# mainboard_split_IO_FPGA_8x2-1a.net
KiCad netlist of a schematic drawn in EAGLE
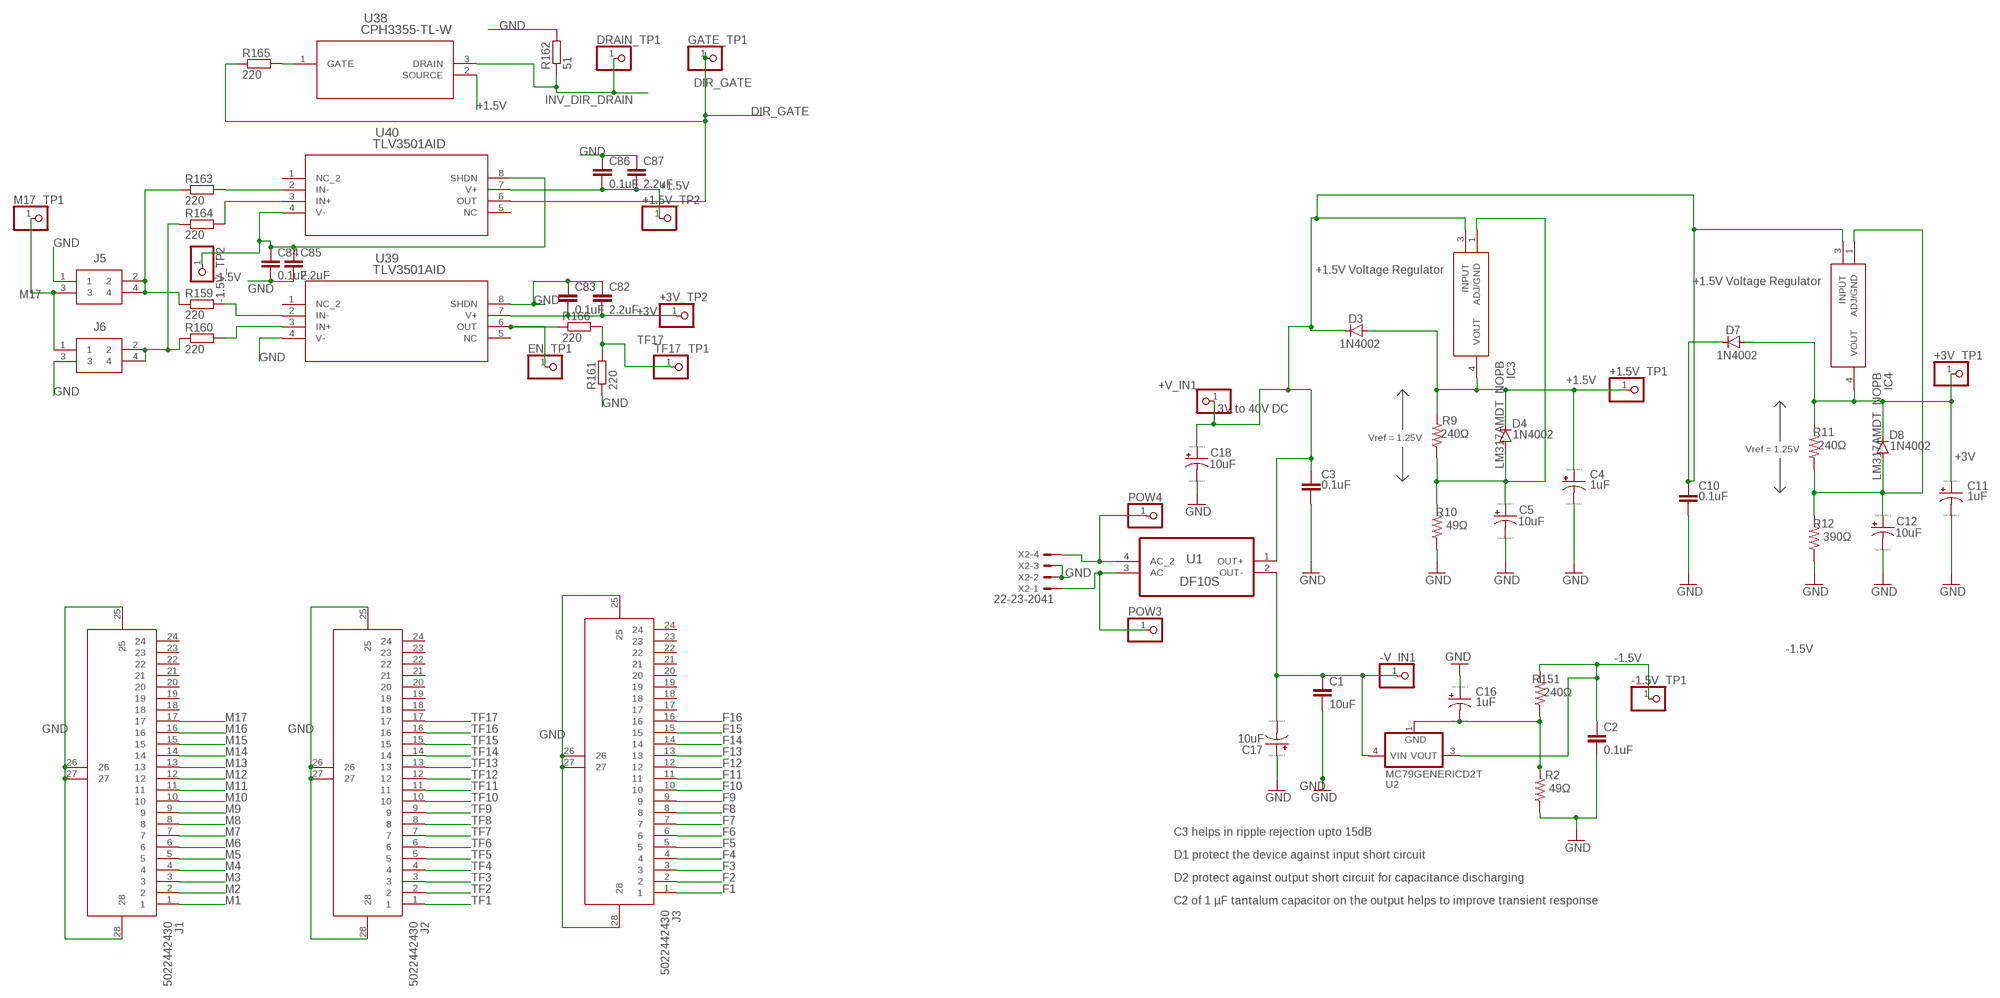
[diagram p0: schematic, sheet 1]
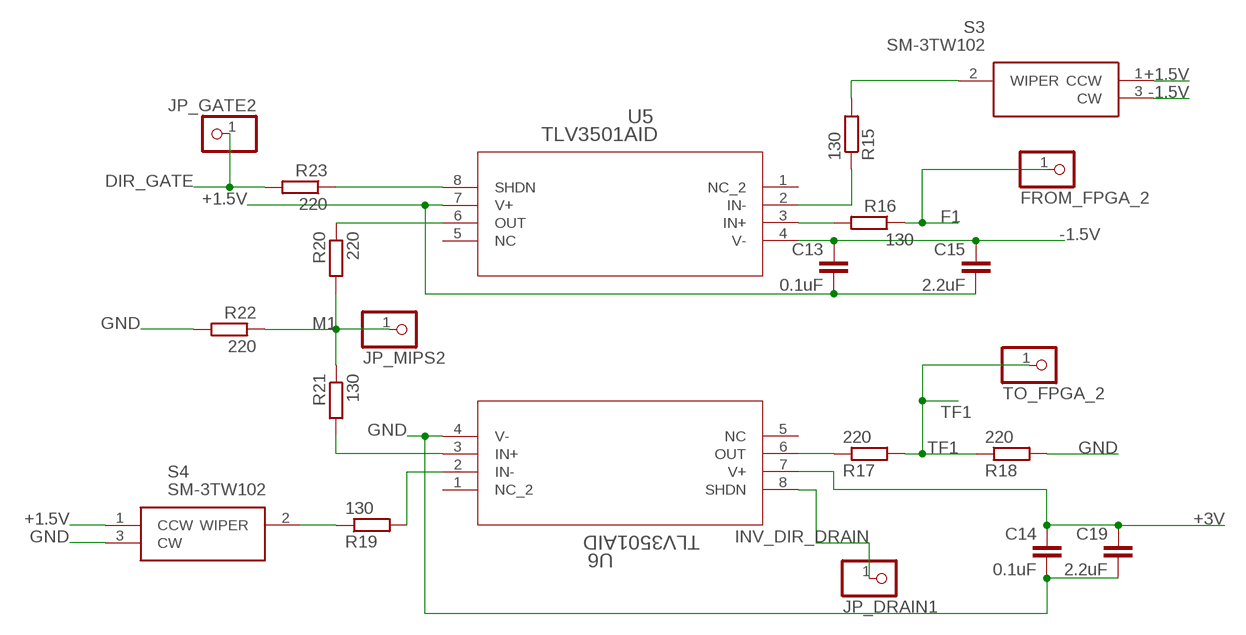
[diagram p1: schematic, sheet 2]
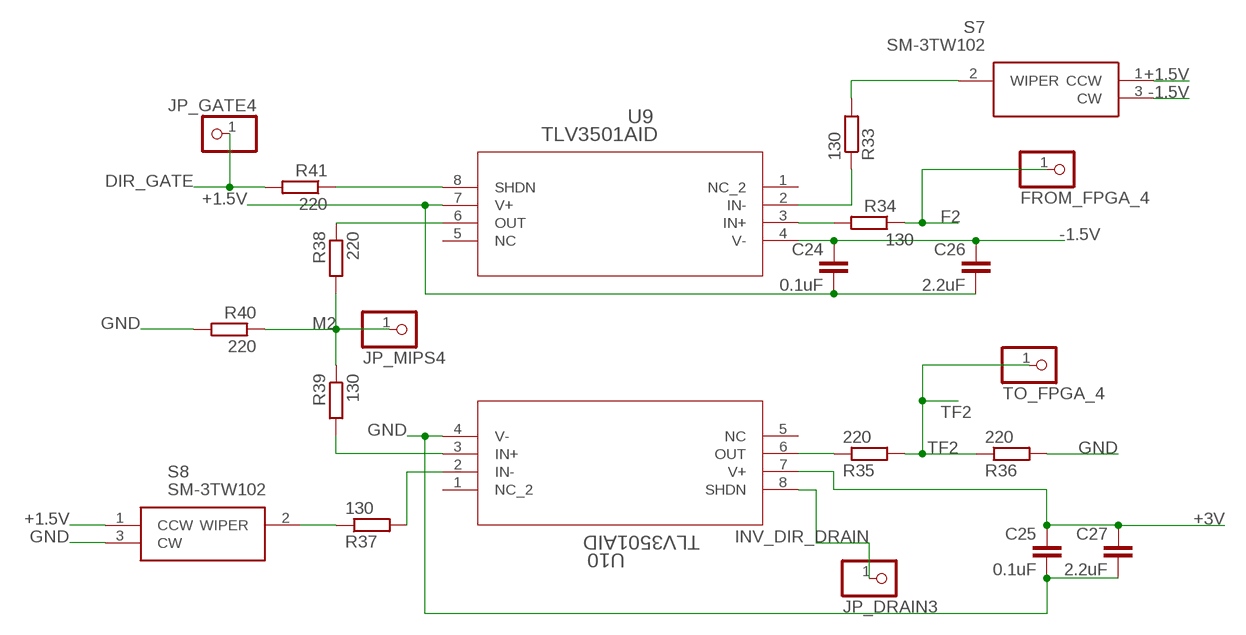
[diagram p2: schematic, sheet 3]
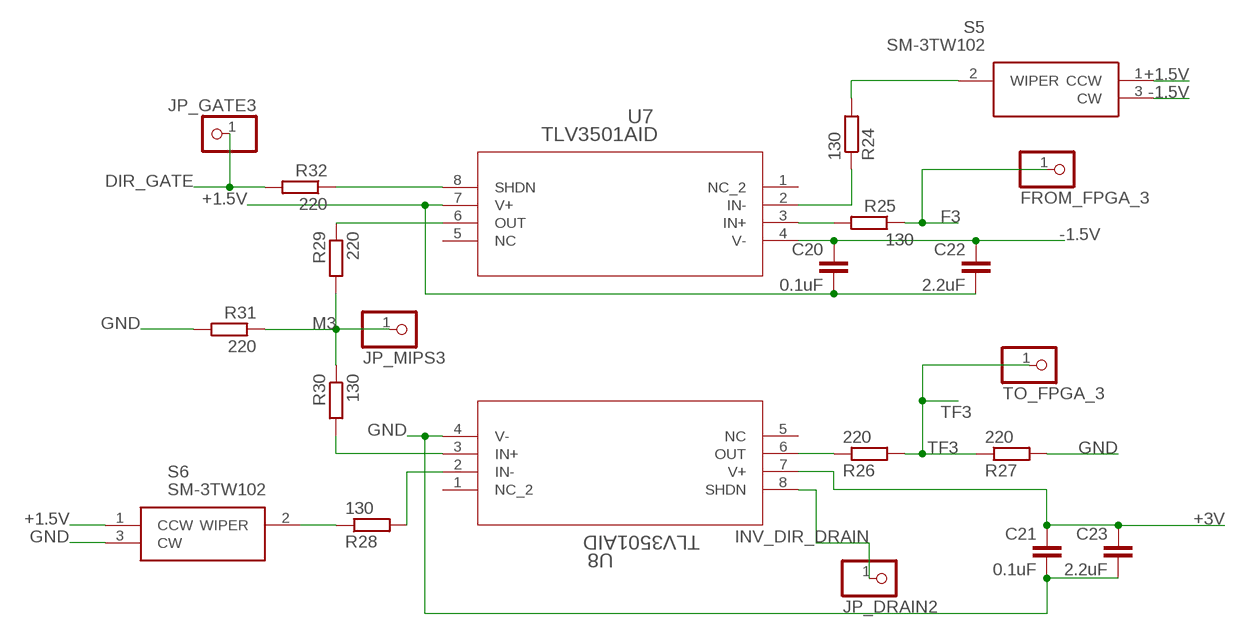
[diagram p3: schematic, sheet 4]
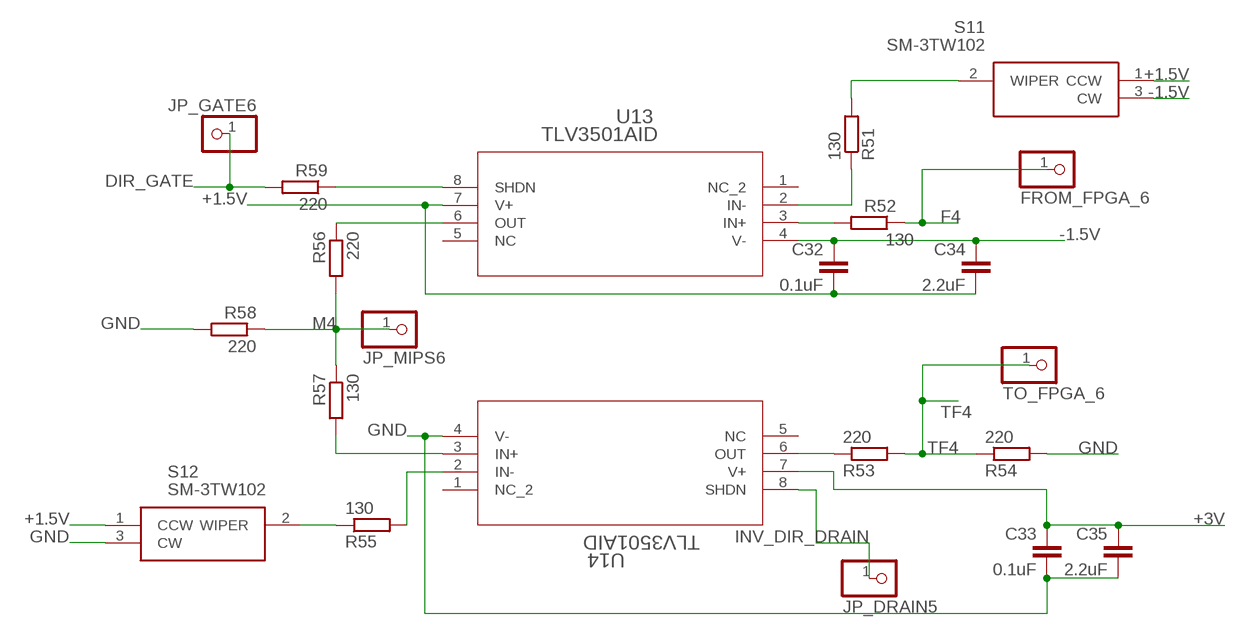
[diagram p4: schematic, sheet 5]
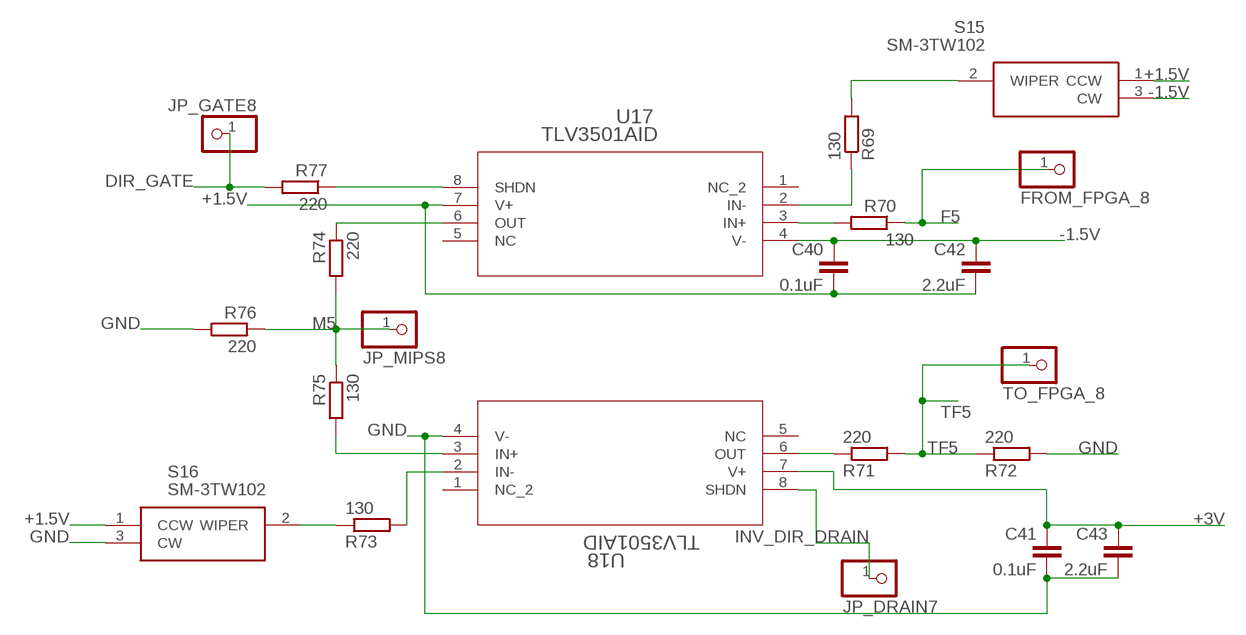
[diagram p5: schematic, sheet 6]
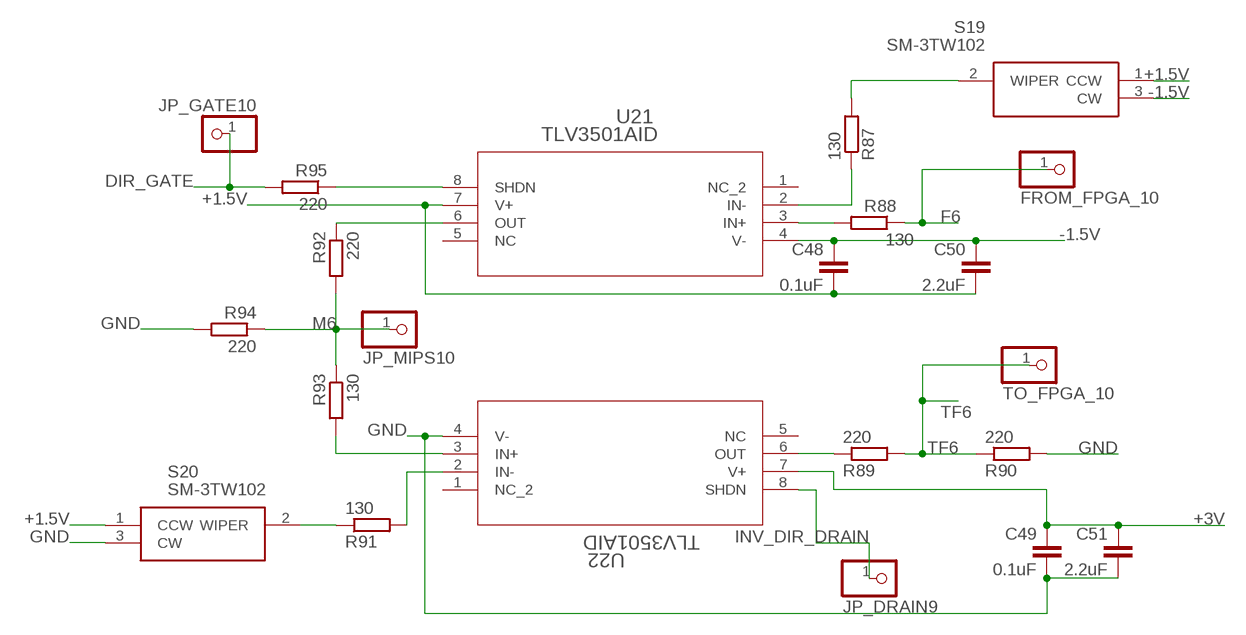
[diagram p6: schematic, sheet 7]
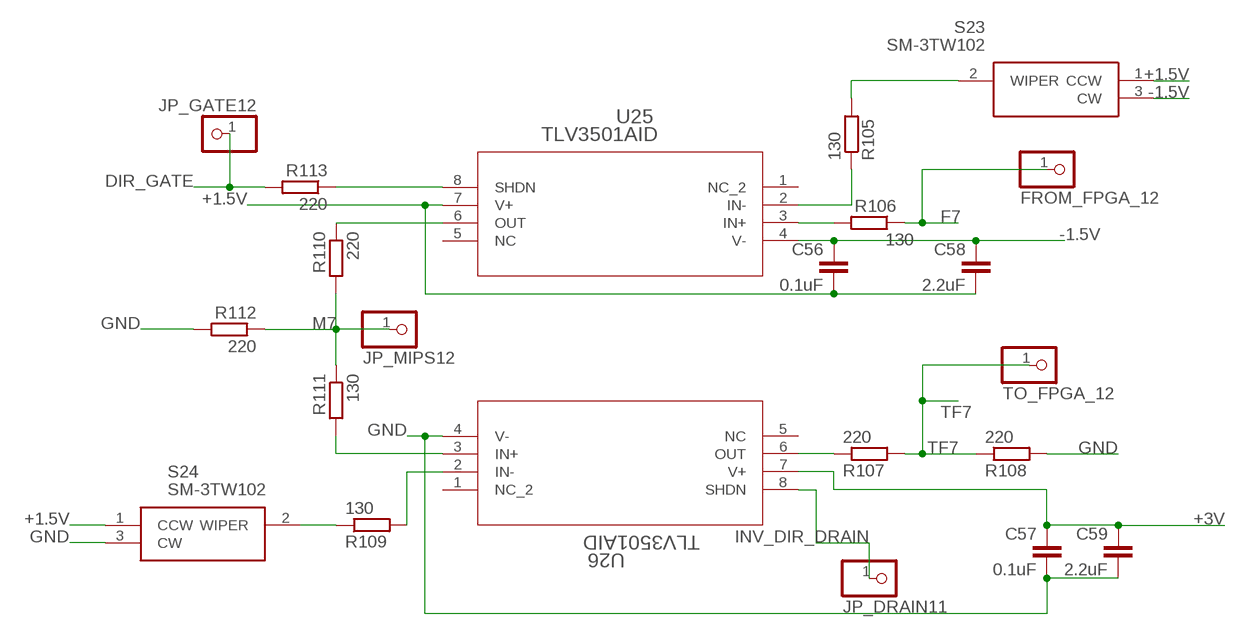
[diagram p7: schematic, sheet 8]
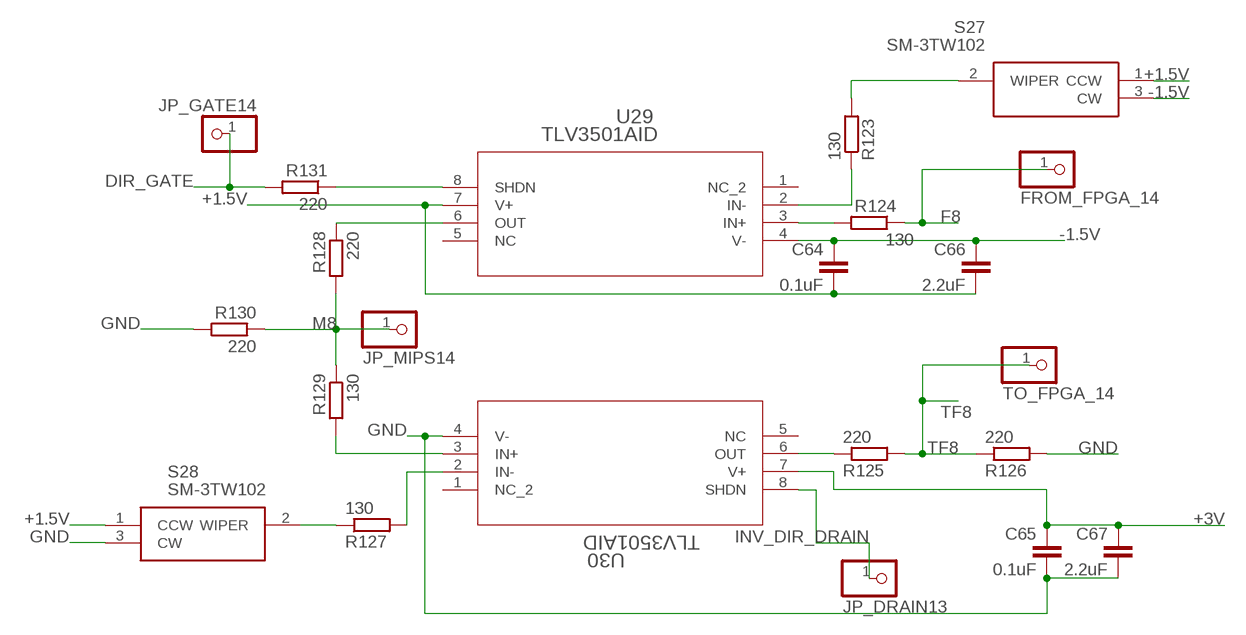
[diagram p8: schematic, sheet 9]
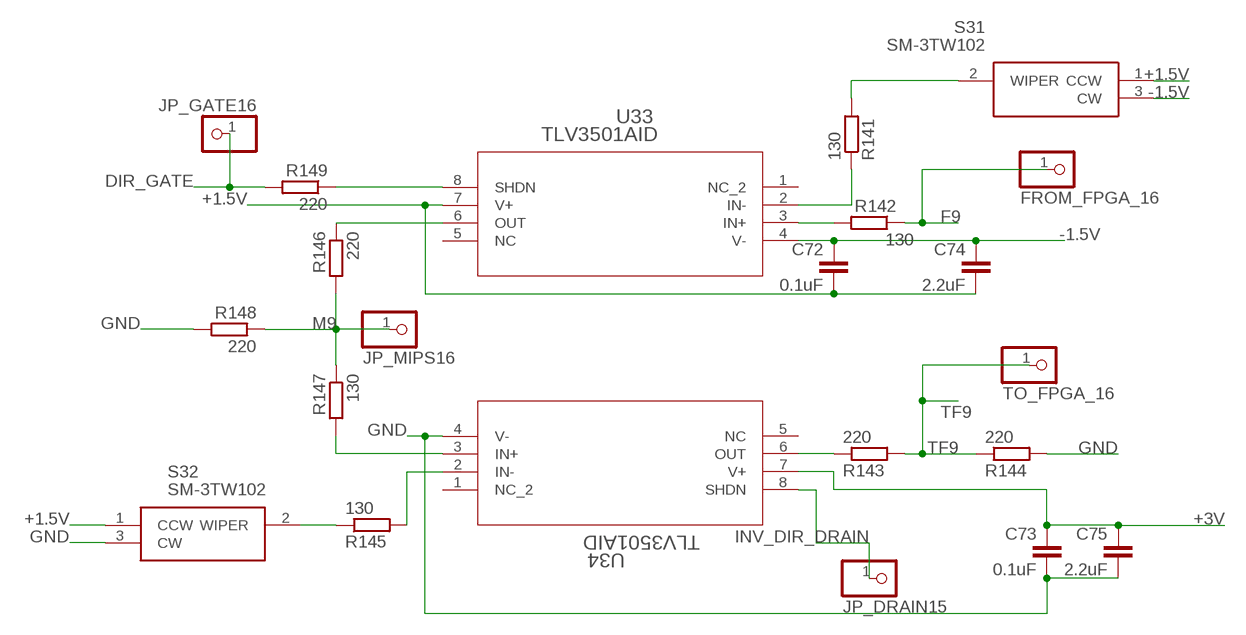
[diagram p9: schematic, sheet 10]
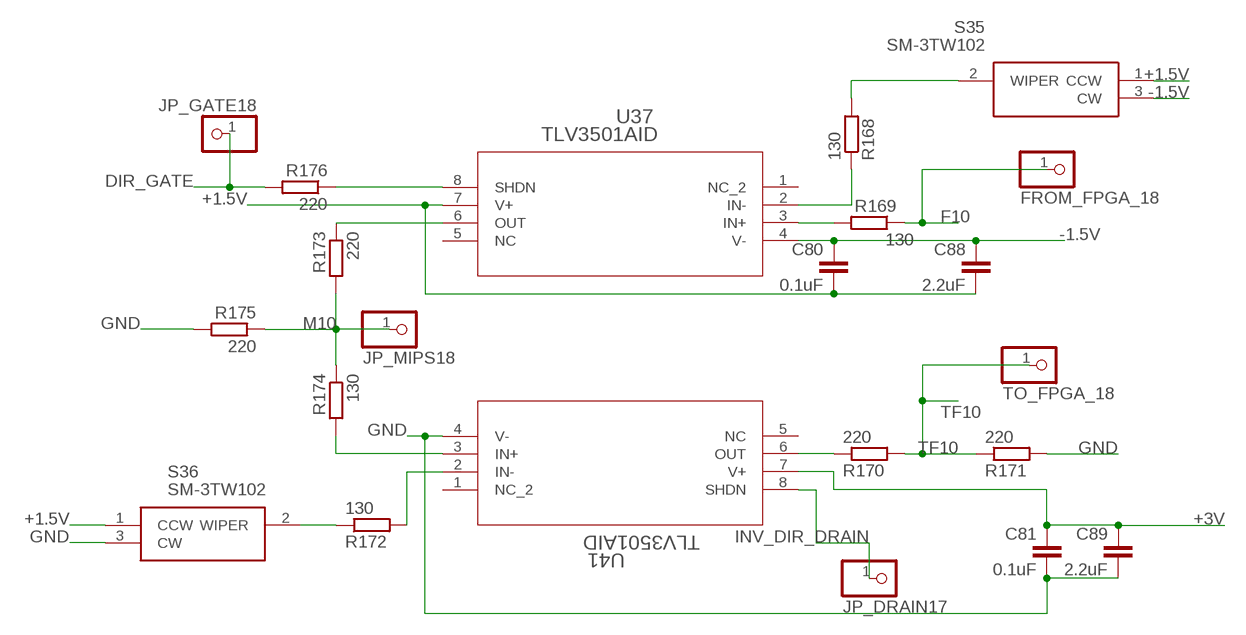
[diagram p10: schematic, sheet 11]
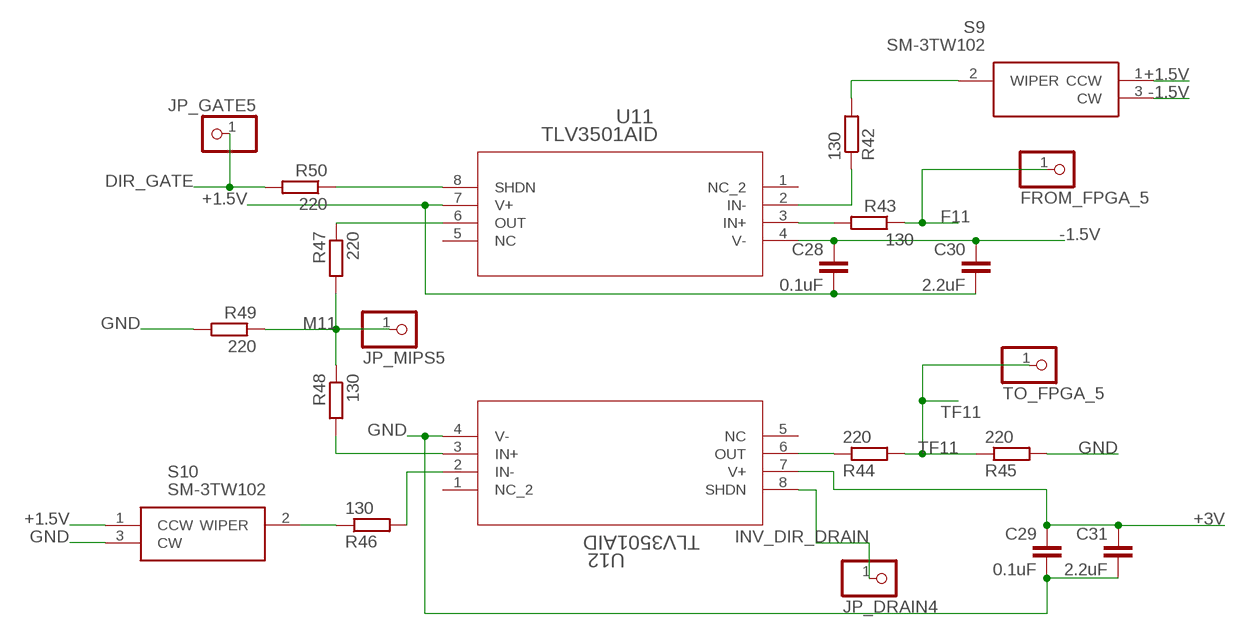
[diagram p11: schematic, sheet 12]
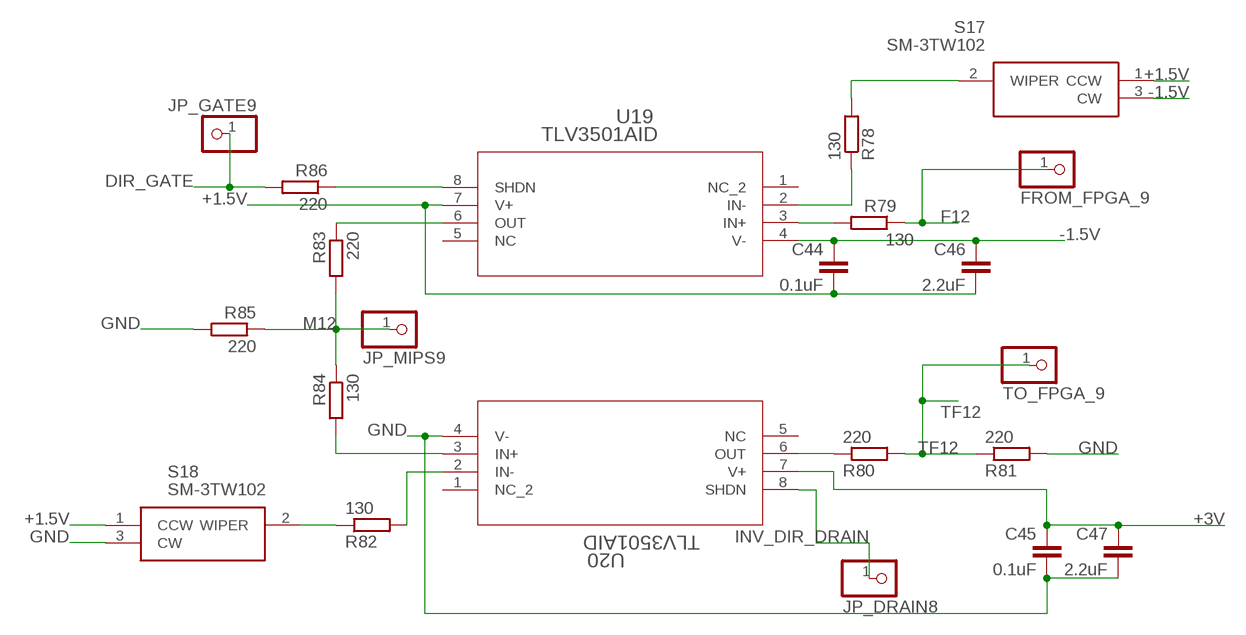
[diagram p12: schematic, sheet 13]
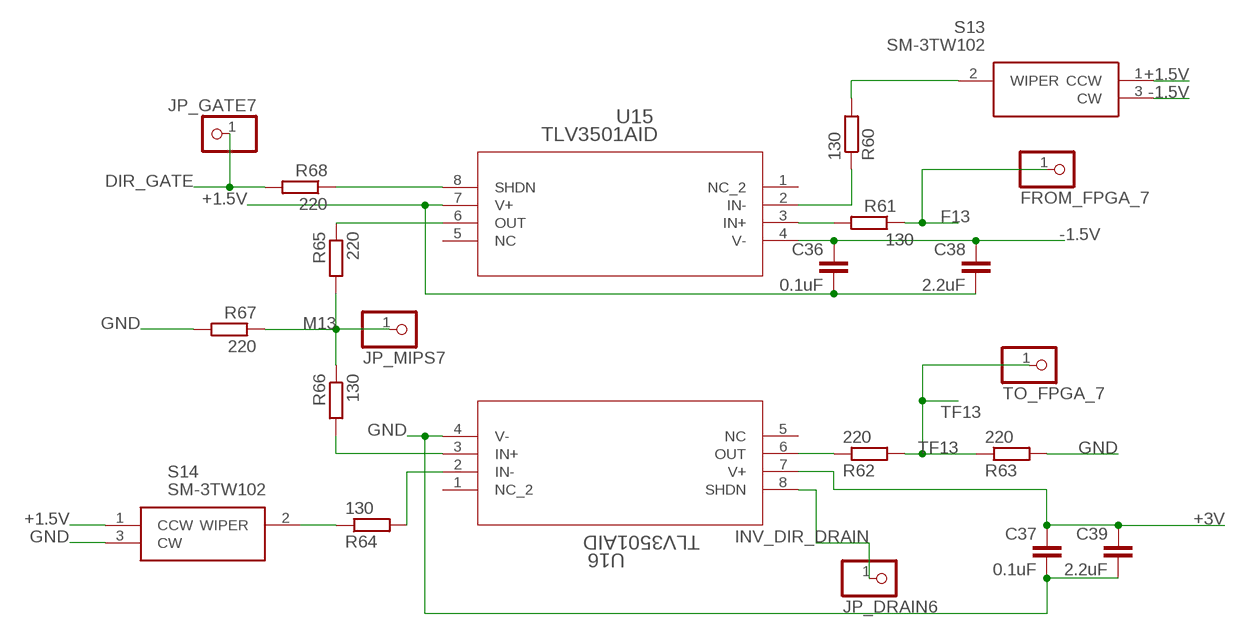
[diagram p13: schematic, sheet 14]
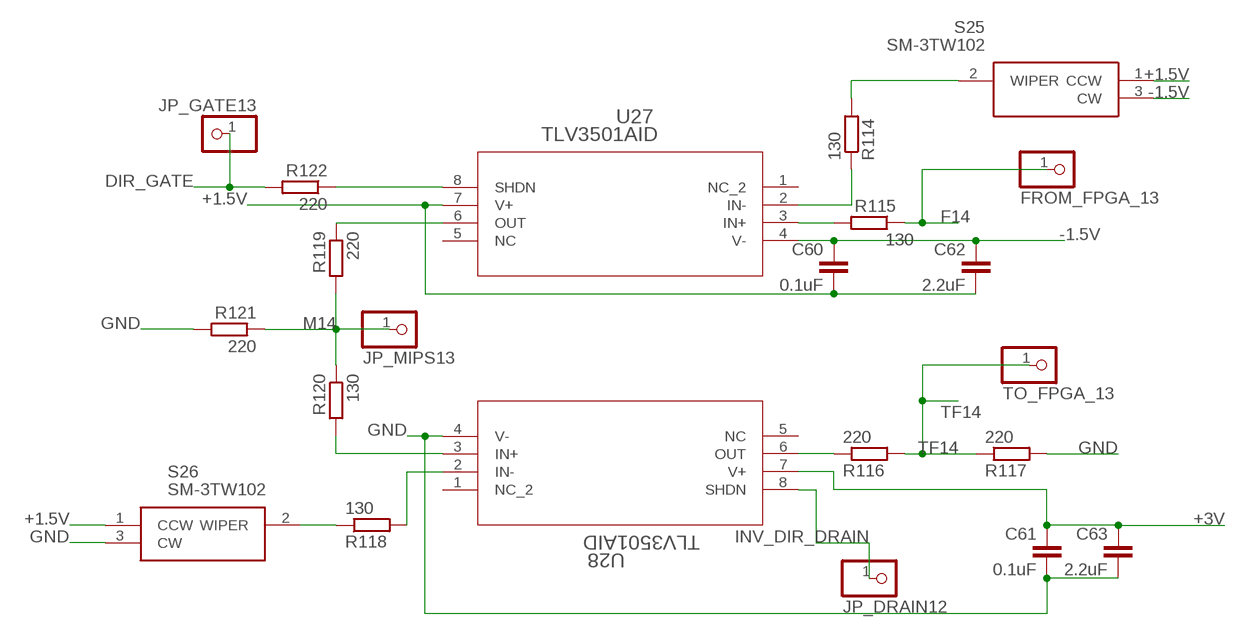
[diagram p14: schematic, sheet 15]
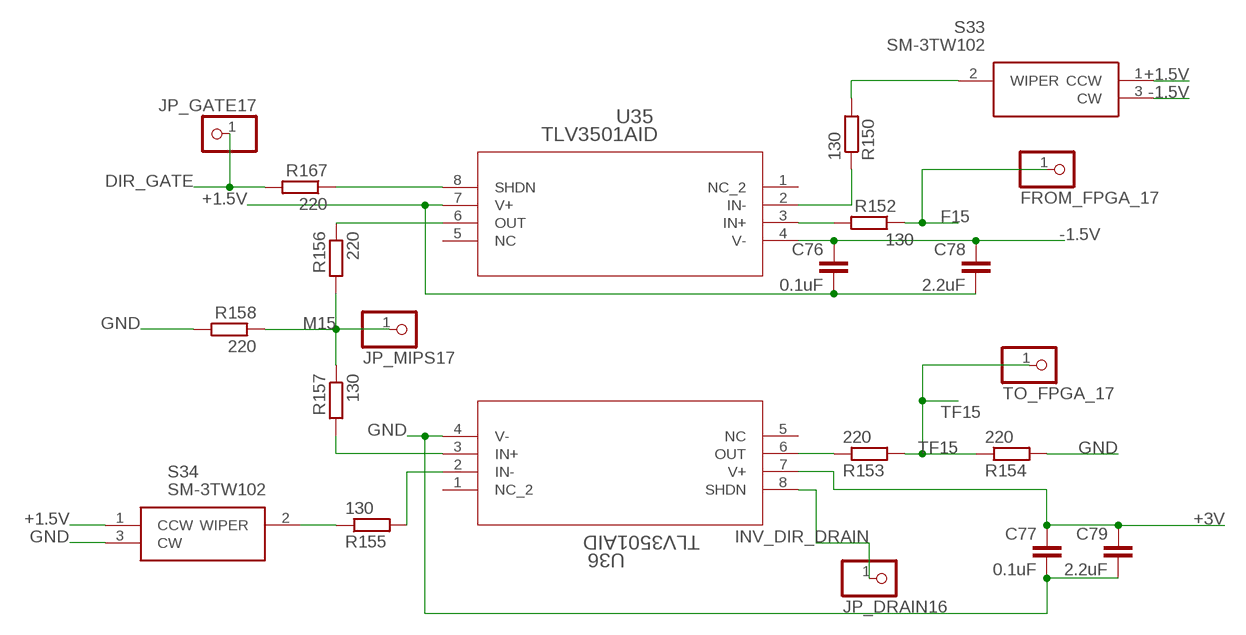
[diagram p15: schematic, sheet 16]
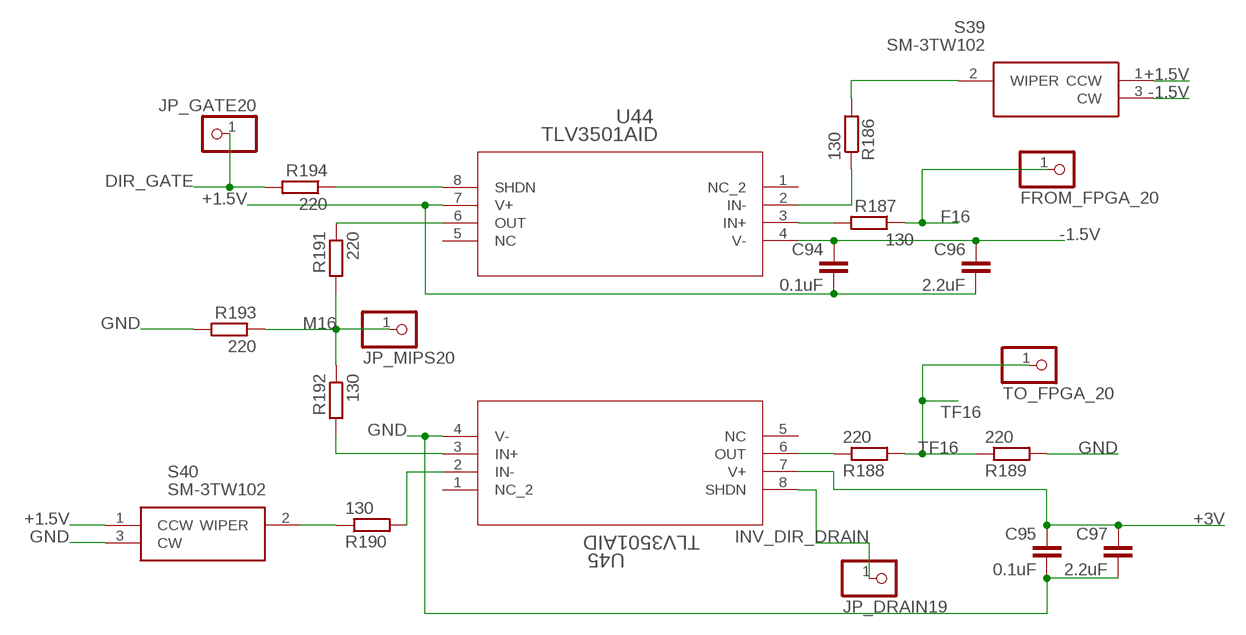
[diagram p16: schematic, sheet 17]

(export (version "E")
  (design (tool "Eeschema 10.0.6"))
  (components
    (comp (ref "C13")
      (value "0.1uF")
      (footprint "eagle-import:C0805")
      (libsource (lib "eagle-import") (part "C-EUC0805"))
    )
    (comp (ref "C14")
      (value "0.1uF")
      (footprint "eagle-import:C0805")
      (libsource (lib "eagle-import") (part "C-EUC0805"))
    )
    (comp (ref "C15")
      (value "2.2uF")
      (footprint "eagle-import:C0805")
      (libsource (lib "eagle-import") (part "C-EUC0805"))
    )
    (comp (ref "C19")
      (value "2.2uF")
      (footprint "eagle-import:C0805")
      (libsource (lib "eagle-import") (part "C-EUC0805"))
    )
    (comp (ref "FROM_FPGA_2")
      (value "PINHD-1X1")
      (footprint "eagle-import:1X01")
      (libsource (lib "eagle-import") (part "PINHD-1X1"))
    )
    (comp (ref "JP_DRAIN1")
      (value "PINHD-1X1")
      (footprint "eagle-import:1X01")
      (libsource (lib "eagle-import") (part "PINHD-1X1"))
    )
    (comp (ref "JP_GATE2")
      (value "PINHD-1X1")
      (footprint "eagle-import:1X01")
      (libsource (lib "eagle-import") (part "PINHD-1X1"))
    )
    (comp (ref "JP_MIPS2")
      (value "PINHD-1X1")
      (footprint "eagle-import:1X01")
      (libsource (lib "eagle-import") (part "PINHD-1X1"))
    )
    (comp (ref "R15")
      (value "130")
      (footprint "eagle-import:R0805")
      (libsource (lib "eagle-import") (part "R-EU_R0805"))
    )
    (comp (ref "R16")
      (value "130")
      (footprint "eagle-import:R0603")
      (libsource (lib "eagle-import") (part "R-EU_R0603"))
    )
    (comp (ref "R17")
      (value "220")
      (footprint "eagle-import:R0805")
      (libsource (lib "eagle-import") (part "R-EU_R0805"))
    )
    (comp (ref "R18")
      (value "220")
      (footprint "eagle-import:R0805")
      (libsource (lib "eagle-import") (part "R-EU_R0805"))
    )
    (comp (ref "R19")
      (value "130")
      (footprint "eagle-import:R0805")
      (libsource (lib "eagle-import") (part "R-EU_R0805"))
    )
    (comp (ref "R20")
      (value "220")
      (footprint "eagle-import:R0805")
      (libsource (lib "eagle-import") (part "R-EU_R0805"))
    )
    (comp (ref "R21")
      (value "130")
      (footprint "eagle-import:R0805")
      (libsource (lib "eagle-import") (part "R-EU_R0805"))
    )
    (comp (ref "R22")
      (value "220")
      (footprint "eagle-import:R0805")
      (libsource (lib "eagle-import") (part "R-EU_R0805"))
    )
    (comp (ref "R23")
      (value "220")
      (footprint "eagle-import:R0805")
      (libsource (lib "eagle-import") (part "R-EU_R0805"))
    )
    (comp (ref "S3")
      (value "SM-3TW102")
      (footprint "eagle-import:SM3TW102")
      (fields (field (name "MOUSER_PART_NUMBER") "229-SM-3TW102"))
      (libsource (lib "eagle-import") (part "SM-3TW102"))
    )
    (comp (ref "S4")
      (value "SM-3TW102")
      (footprint "eagle-import:SM3TW102")
      (fields (field (name "MOUSER_PART_NUMBER") "229-SM-3TW102"))
      (libsource (lib "eagle-import") (part "SM-3TW102"))
    )
    (comp (ref "TO_FPGA_2")
      (value "PINHD-1X1")
      (footprint "eagle-import:1X01")
      (libsource (lib "eagle-import") (part "PINHD-1X1"))
    )
    (comp (ref "U5")
      (value "TLV3501AID")
      (footprint "eagle-import:D8")
      (fields (field (name "COPYRIGHT") "Copyright (C) 2022 Ultra Librarian. All rights reserved."))
      (libsource (lib "eagle-import") (part "TLV3501AID"))
    )
    (comp (ref "U6")
      (value "TLV3501AID")
      (footprint "eagle-import:D8")
      (fields (field (name "COPYRIGHT") "Copyright (C) 2022 Ultra Librarian. All rights reserved."))
      (libsource (lib "eagle-import") (part "TLV3501AID"))
    )
    (comp (ref "C80")
      (value "0.1uF")
      (footprint "eagle-import:C0805")
      (libsource (lib "eagle-import") (part "C-EUC0805"))
    )
    (comp (ref "C81")
      (value "0.1uF")
      (footprint "eagle-import:C0805")
      (libsource (lib "eagle-import") (part "C-EUC0805"))
    )
    (comp (ref "C88")
      (value "2.2uF")
      (footprint "eagle-import:C0805")
      (libsource (lib "eagle-import") (part "C-EUC0805"))
    )
    (comp (ref "C89")
      (value "2.2uF")
      (footprint "eagle-import:C0805")
      (libsource (lib "eagle-import") (part "C-EUC0805"))
    )
    (comp (ref "FROM_FPGA_18")
      (value "PINHD-1X1")
      (footprint "eagle-import:1X01")
      (libsource (lib "eagle-import") (part "PINHD-1X1"))
    )
    (comp (ref "JP_DRAIN17")
      (value "PINHD-1X1")
      (footprint "eagle-import:1X01")
      (libsource (lib "eagle-import") (part "PINHD-1X1"))
    )
    (comp (ref "JP_GATE18")
      (value "PINHD-1X1")
      (footprint "eagle-import:1X01")
      (libsource (lib "eagle-import") (part "PINHD-1X1"))
    )
    (comp (ref "JP_MIPS18")
      (value "PINHD-1X1")
      (footprint "eagle-import:1X01")
      (libsource (lib "eagle-import") (part "PINHD-1X1"))
    )
    (comp (ref "R168")
      (value "130")
      (footprint "eagle-import:R0805")
      (libsource (lib "eagle-import") (part "R-EU_R0805"))
    )
    (comp (ref "R169")
      (value "130")
      (footprint "eagle-import:R0603")
      (libsource (lib "eagle-import") (part "R-EU_R0603"))
    )
    (comp (ref "R170")
      (value "220")
      (footprint "eagle-import:R0805")
      (libsource (lib "eagle-import") (part "R-EU_R0805"))
    )
    (comp (ref "R171")
      (value "220")
      (footprint "eagle-import:R0805")
      (libsource (lib "eagle-import") (part "R-EU_R0805"))
    )
    (comp (ref "R172")
      (value "130")
      (footprint "eagle-import:R0805")
      (libsource (lib "eagle-import") (part "R-EU_R0805"))
    )
    (comp (ref "R173")
      (value "220")
      (footprint "eagle-import:R0805")
      (libsource (lib "eagle-import") (part "R-EU_R0805"))
    )
    (comp (ref "R174")
      (value "130")
      (footprint "eagle-import:R0805")
      (libsource (lib "eagle-import") (part "R-EU_R0805"))
    )
    (comp (ref "R175")
      (value "220")
      (footprint "eagle-import:R0805")
      (libsource (lib "eagle-import") (part "R-EU_R0805"))
    )
    (comp (ref "R176")
      (value "220")
      (footprint "eagle-import:R0805")
      (libsource (lib "eagle-import") (part "R-EU_R0805"))
    )
    (comp (ref "S35")
      (value "SM-3TW102")
      (footprint "eagle-import:SM3TW102")
      (fields (field (name "MOUSER_PART_NUMBER") "229-SM-3TW102"))
      (libsource (lib "eagle-import") (part "SM-3TW102"))
    )
    (comp (ref "S36")
      (value "SM-3TW102")
      (footprint "eagle-import:SM3TW102")
      (fields (field (name "MOUSER_PART_NUMBER") "229-SM-3TW102"))
      (libsource (lib "eagle-import") (part "SM-3TW102"))
    )
    (comp (ref "TO_FPGA_18")
      (value "PINHD-1X1")
      (footprint "eagle-import:1X01")
      (libsource (lib "eagle-import") (part "PINHD-1X1"))
    )
    (comp (ref "U37")
      (value "TLV3501AID")
      (footprint "eagle-import:D8")
      (fields (field (name "COPYRIGHT") "Copyright (C) 2022 Ultra Librarian. All rights reserved."))
      (libsource (lib "eagle-import") (part "TLV3501AID"))
    )
    (comp (ref "U41")
      (value "TLV3501AID")
      (footprint "eagle-import:D8")
      (fields (field (name "COPYRIGHT") "Copyright (C) 2022 Ultra Librarian. All rights reserved."))
      (libsource (lib "eagle-import") (part "TLV3501AID"))
    )
    (comp (ref "C28")
      (value "0.1uF")
      (footprint "eagle-import:C0805")
      (libsource (lib "eagle-import") (part "C-EUC0805"))
    )
    (comp (ref "C29")
      (value "0.1uF")
      (footprint "eagle-import:C0805")
      (libsource (lib "eagle-import") (part "C-EUC0805"))
    )
    (comp (ref "C30")
      (value "2.2uF")
      (footprint "eagle-import:C0805")
      (libsource (lib "eagle-import") (part "C-EUC0805"))
    )
    (comp (ref "C31")
      (value "2.2uF")
      (footprint "eagle-import:C0805")
      (libsource (lib "eagle-import") (part "C-EUC0805"))
    )
    (comp (ref "FROM_FPGA_5")
      (value "PINHD-1X1")
      (footprint "eagle-import:1X01")
      (libsource (lib "eagle-import") (part "PINHD-1X1"))
    )
    (comp (ref "JP_DRAIN4")
      (value "PINHD-1X1")
      (footprint "eagle-import:1X01")
      (libsource (lib "eagle-import") (part "PINHD-1X1"))
    )
    (comp (ref "JP_GATE5")
      (value "PINHD-1X1")
      (footprint "eagle-import:1X01")
      (libsource (lib "eagle-import") (part "PINHD-1X1"))
    )
    (comp (ref "JP_MIPS5")
      (value "PINHD-1X1")
      (footprint "eagle-import:1X01")
      (libsource (lib "eagle-import") (part "PINHD-1X1"))
    )
    (comp (ref "R42")
      (value "130")
      (footprint "eagle-import:R0805")
      (libsource (lib "eagle-import") (part "R-EU_R0805"))
    )
    (comp (ref "R43")
      (value "130")
      (footprint "eagle-import:R0603")
      (libsource (lib "eagle-import") (part "R-EU_R0603"))
    )
    (comp (ref "R44")
      (value "220")
      (footprint "eagle-import:R0805")
      (libsource (lib "eagle-import") (part "R-EU_R0805"))
    )
    (comp (ref "R45")
      (value "220")
      (footprint "eagle-import:R0805")
      (libsource (lib "eagle-import") (part "R-EU_R0805"))
    )
    (comp (ref "R46")
      (value "130")
      (footprint "eagle-import:R0805")
      (libsource (lib "eagle-import") (part "R-EU_R0805"))
    )
    (comp (ref "R47")
      (value "220")
      (footprint "eagle-import:R0805")
      (libsource (lib "eagle-import") (part "R-EU_R0805"))
    )
    (comp (ref "R48")
      (value "130")
      (footprint "eagle-import:R0805")
      (libsource (lib "eagle-import") (part "R-EU_R0805"))
    )
    (comp (ref "R49")
      (value "220")
      (footprint "eagle-import:R0805")
      (libsource (lib "eagle-import") (part "R-EU_R0805"))
    )
    (comp (ref "R50")
      (value "220")
      (footprint "eagle-import:R0805")
      (libsource (lib "eagle-import") (part "R-EU_R0805"))
    )
    (comp (ref "S9")
      (value "SM-3TW102")
      (footprint "eagle-import:SM3TW102")
      (fields (field (name "MOUSER_PART_NUMBER") "229-SM-3TW102"))
      (libsource (lib "eagle-import") (part "SM-3TW102"))
    )
    (comp (ref "S10")
      (value "SM-3TW102")
      (footprint "eagle-import:SM3TW102")
      (fields (field (name "MOUSER_PART_NUMBER") "229-SM-3TW102"))
      (libsource (lib "eagle-import") (part "SM-3TW102"))
    )
    (comp (ref "TO_FPGA_5")
      (value "PINHD-1X1")
      (footprint "eagle-import:1X01")
      (libsource (lib "eagle-import") (part "PINHD-1X1"))
    )
    (comp (ref "U11")
      (value "TLV3501AID")
      (footprint "eagle-import:D8")
      (fields (field (name "COPYRIGHT") "Copyright (C) 2022 Ultra Librarian. All rights reserved."))
      (libsource (lib "eagle-import") (part "TLV3501AID"))
    )
    (comp (ref "U12")
      (value "TLV3501AID")
      (footprint "eagle-import:D8")
      (fields (field (name "COPYRIGHT") "Copyright (C) 2022 Ultra Librarian. All rights reserved."))
      (libsource (lib "eagle-import") (part "TLV3501AID"))
    )
    (comp (ref "C20")
      (value "0.1uF")
      (footprint "eagle-import:C0805")
      (libsource (lib "eagle-import") (part "C-EUC0805"))
    )
    (comp (ref "C21")
      (value "0.1uF")
      (footprint "eagle-import:C0805")
      (libsource (lib "eagle-import") (part "C-EUC0805"))
    )
    (comp (ref "C22")
      (value "2.2uF")
      (footprint "eagle-import:C0805")
      (libsource (lib "eagle-import") (part "C-EUC0805"))
    )
    (comp (ref "C23")
      (value "2.2uF")
      (footprint "eagle-import:C0805")
      (libsource (lib "eagle-import") (part "C-EUC0805"))
    )
    (comp (ref "FROM_FPGA_3")
      (value "PINHD-1X1")
      (footprint "eagle-import:1X01")
      (libsource (lib "eagle-import") (part "PINHD-1X1"))
    )
    (comp (ref "JP_DRAIN2")
      (value "PINHD-1X1")
      (footprint "eagle-import:1X01")
      (libsource (lib "eagle-import") (part "PINHD-1X1"))
    )
    (comp (ref "JP_GATE3")
      (value "PINHD-1X1")
      (footprint "eagle-import:1X01")
      (libsource (lib "eagle-import") (part "PINHD-1X1"))
    )
    (comp (ref "JP_MIPS3")
      (value "PINHD-1X1")
      (footprint "eagle-import:1X01")
      (libsource (lib "eagle-import") (part "PINHD-1X1"))
    )
    (comp (ref "R24")
      (value "130")
      (footprint "eagle-import:R0805")
      (libsource (lib "eagle-import") (part "R-EU_R0805"))
    )
    (comp (ref "R25")
      (value "130")
      (footprint "eagle-import:R0603")
      (libsource (lib "eagle-import") (part "R-EU_R0603"))
    )
    (comp (ref "R26")
      (value "220")
      (footprint "eagle-import:R0805")
      (libsource (lib "eagle-import") (part "R-EU_R0805"))
    )
    (comp (ref "R27")
      (value "220")
      (footprint "eagle-import:R0805")
      (libsource (lib "eagle-import") (part "R-EU_R0805"))
    )
    (comp (ref "R28")
      (value "130")
      (footprint "eagle-import:R0805")
      (libsource (lib "eagle-import") (part "R-EU_R0805"))
    )
    (comp (ref "R29")
      (value "220")
      (footprint "eagle-import:R0805")
      (libsource (lib "eagle-import") (part "R-EU_R0805"))
    )
    (comp (ref "R30")
      (value "130")
      (footprint "eagle-import:R0805")
      (libsource (lib "eagle-import") (part "R-EU_R0805"))
    )
    (comp (ref "R31")
      (value "220")
      (footprint "eagle-import:R0805")
      (libsource (lib "eagle-import") (part "R-EU_R0805"))
    )
    (comp (ref "R32")
      (value "220")
      (footprint "eagle-import:R0805")
      (libsource (lib "eagle-import") (part "R-EU_R0805"))
    )
    (comp (ref "S5")
      (value "SM-3TW102")
      (footprint "eagle-import:SM3TW102")
      (fields (field (name "MOUSER_PART_NUMBER") "229-SM-3TW102"))
      (libsource (lib "eagle-import") (part "SM-3TW102"))
    )
    (comp (ref "S6")
      (value "SM-3TW102")
      (footprint "eagle-import:SM3TW102")
      (fields (field (name "MOUSER_PART_NUMBER") "229-SM-3TW102"))
      (libsource (lib "eagle-import") (part "SM-3TW102"))
    )
    (comp (ref "TO_FPGA_3")
      (value "PINHD-1X1")
      (footprint "eagle-import:1X01")
      (libsource (lib "eagle-import") (part "PINHD-1X1"))
    )
    (comp (ref "U7")
      (value "TLV3501AID")
      (footprint "eagle-import:D8")
      (fields (field (name "COPYRIGHT") "Copyright (C) 2022 Ultra Librarian. All rights reserved."))
      (libsource (lib "eagle-import") (part "TLV3501AID"))
    )
    (comp (ref "U8")
      (value "TLV3501AID")
      (footprint "eagle-import:D8")
      (fields (field (name "COPYRIGHT") "Copyright (C) 2022 Ultra Librarian. All rights reserved."))
      (libsource (lib "eagle-import") (part "TLV3501AID"))
    )
    (comp (ref "+1.5V_TP1")
      (value "PINHD-1X1")
      (footprint "eagle-import:1X01")
      (libsource (lib "eagle-import") (part "PINHD-1X1"))
    )
    (comp (ref "+1.5V_TP2")
      (value "PINHD-1X1")
      (footprint "eagle-import:1X01")
      (libsource (lib "eagle-import") (part "PINHD-1X1"))
    )
    (comp (ref "+3V_TP1")
      (value "PINHD-1X1")
      (footprint "eagle-import:1X01")
      (libsource (lib "eagle-import") (part "PINHD-1X1"))
    )
    (comp (ref "+3V_TP2")
      (value "PINHD-1X1")
      (footprint "eagle-import:1X01")
      (libsource (lib "eagle-import") (part "PINHD-1X1"))
    )
    (comp (ref "+V_IN1")
      (value "PINHD-1X1")
      (footprint "eagle-import:1X01")
      (libsource (lib "eagle-import") (part "PINHD-1X1"))
    )
    (comp (ref "-1.5V_TP1")
      (value "PINHD-1X1")
      (footprint "eagle-import:1X01")
      (libsource (lib "eagle-import") (part "PINHD-1X1"))
    )
    (comp (ref "-1.5V_TP2")
      (value "PINHD-1X1")
      (footprint "eagle-import:1X01")
      (libsource (lib "eagle-import") (part "PINHD-1X1"))
    )
    (comp (ref "-V_IN1")
      (value "PINHD-1X1")
      (footprint "eagle-import:1X01")
      (libsource (lib "eagle-import") (part "PINHD-1X1"))
    )
    (comp (ref "C1")
      (value "10uF")
      (footprint "eagle-import:C0805")
      (libsource (lib "eagle-import") (part "C-EUC0805"))
    )
    (comp (ref "C2")
      (value "0.1uF")
      (footprint "eagle-import:C0805")
      (libsource (lib "eagle-import") (part "C-EUC0805"))
    )
    (comp (ref "C3")
      (value "0.1uF")
      (footprint "eagle-import:C075-052X106")
      (libsource (lib "eagle-import") (part "C-EU075-052X106"))
    )
    (comp (ref "C4")
      (value "1uF")
      (footprint "eagle-import:085CS_1AR")
      (libsource (lib "eagle-import") (part "CPOL-US085CS-1AR"))
    )
    (comp (ref "C5")
      (value "10uF")
      (footprint "eagle-import:085CS_1AR")
      (libsource (lib "eagle-import") (part "CPOL-US085CS-1AR"))
    )
    (comp (ref "C10")
      (value "0.1uF")
      (footprint "eagle-import:C075-052X106")
      (libsource (lib "eagle-import") (part "C-EU075-052X106"))
    )
    (comp (ref "C11")
      (value "1uF")
      (footprint "eagle-import:085CS_1AR")
      (libsource (lib "eagle-import") (part "CPOL-US085CS-1AR"))
    )
    (comp (ref "C12")
      (value "10uF")
      (footprint "eagle-import:085CS_1AR")
      (libsource (lib "eagle-import") (part "CPOL-US085CS-1AR"))
    )
    (comp (ref "C16")
      (value "1uF")
      (footprint "eagle-import:085CS_1AR")
      (libsource (lib "eagle-import") (part "CPOL-US085CS-1AR"))
    )
    (comp (ref "C17")
      (value "10uF")
      (footprint "eagle-import:085CS_1AR")
      (libsource (lib "eagle-import") (part "CPOL-US085CS-1AR"))
    )
    (comp (ref "C18")
      (value "10uF")
      (footprint "eagle-import:085CS_1AR")
      (libsource (lib "eagle-import") (part "CPOL-US085CS-1AR"))
    )
    (comp (ref "C82")
      (value "2.2uF")
      (footprint "eagle-import:C0805")
      (libsource (lib "eagle-import") (part "C-EUC0805"))
    )
    (comp (ref "C83")
      (value "0.1uF")
      (footprint "eagle-import:C0805")
      (libsource (lib "eagle-import") (part "C-EUC0805"))
    )
    (comp (ref "C84")
      (value "0.1uF")
      (footprint "eagle-import:C0805")
      (libsource (lib "eagle-import") (part "C-EUC0805"))
    )
    (comp (ref "C85")
      (value "2.2uF")
      (footprint "eagle-import:C0805")
      (libsource (lib "eagle-import") (part "C-EUC0805"))
    )
    (comp (ref "C86")
      (value "0.1uF")
      (footprint "eagle-import:C0805")
      (libsource (lib "eagle-import") (part "C-EUC0805"))
    )
    (comp (ref "C87")
      (value "2.2uF")
      (footprint "eagle-import:C0805")
      (libsource (lib "eagle-import") (part "C-EUC0805"))
    )
    (comp (ref "D3")
      (value "1N4002")
      (footprint "eagle-import:DO41-10")
      (libsource (lib "eagle-import") (part "1N4004"))
    )
    (comp (ref "D4")
      (value "1N4002")
      (footprint "eagle-import:DO41-10")
      (libsource (lib "eagle-import") (part "1N4004"))
    )
    (comp (ref "D7")
      (value "1N4002")
      (footprint "eagle-import:DO41-10")
      (libsource (lib "eagle-import") (part "1N4004"))
    )
    (comp (ref "D8")
      (value "1N4002")
      (footprint "eagle-import:DO41-10")
      (libsource (lib "eagle-import") (part "1N4004"))
    )
    (comp (ref "DRAIN_TP1")
      (value "PINHD-1X1")
      (footprint "eagle-import:1X01")
      (libsource (lib "eagle-import") (part "PINHD-1X1"))
    )
    (comp (ref "EN_TP1")
      (value "PINHD-1X1")
      (footprint "eagle-import:1X01")
      (libsource (lib "eagle-import") (part "PINHD-1X1"))
    )
    (comp (ref "GATE_TP1")
      (value "PINHD-1X1")
      (footprint "eagle-import:1X01")
      (libsource (lib "eagle-import") (part "PINHD-1X1"))
    )
    (comp (ref "IC3")
      (value "LM317AMDT_NOPB")
      (footprint "eagle-import:TO228P991X238-3N")
      (fields
        (field (name "MANUFACTURER_PART_NUMBER") "LM317AMDT/NOPB")
        (field (name "MOUSER_PART_NUMBER") "926-LM317AMDT/NOPB")
      )
      (libsource (lib "eagle-import") (part "LM317AMDT_NOPB"))
    )
    (comp (ref "IC4")
      (value "LM317AMDT_NOPB")
      (footprint "eagle-import:TO228P991X238-3N")
      (fields
        (field (name "MANUFACTURER_PART_NUMBER") "LM317AMDT/NOPB")
        (field (name "MOUSER_PART_NUMBER") "926-LM317AMDT/NOPB")
      )
      (libsource (lib "eagle-import") (part "LM317AMDT_NOPB"))
    )
    (comp (ref "J1")
      (value "5022442430")
      (footprint "eagle-import:5022442430")
      (libsource (lib "eagle-import") (part "5022442430"))
    )
    (comp (ref "J2")
      (value "5022442430")
      (footprint "eagle-import:5022442430")
      (libsource (lib "eagle-import") (part "5022442430"))
    )
    (comp (ref "J3")
      (value "5022442430")
      (footprint "eagle-import:5022442430")
      (libsource (lib "eagle-import") (part "5022442430"))
    )
    (comp (ref "J5")
      (value "70287-1098")
      (footprint "eagle-import:HDRV4W64P254_2X2_521X508X851P")
      (fields (field (name "MOUSER_PART_NUMBER") "538-70287-1098"))
      (libsource (lib "eagle-import") (part "70287-1098"))
    )
    (comp (ref "J6")
      (value "70287-1098")
      (footprint "eagle-import:HDRV4W64P254_2X2_521X508X851P")
      (fields (field (name "MOUSER_PART_NUMBER") "538-70287-1098"))
      (libsource (lib "eagle-import") (part "70287-1098"))
    )
    (comp (ref "M17_TP1")
      (value "PINHD-1X1")
      (footprint "eagle-import:1X01")
      (libsource (lib "eagle-import") (part "PINHD-1X1"))
    )
    (comp (ref "POW3")
      (value "PINHD-1X1")
      (footprint "eagle-import:1X01")
      (libsource (lib "eagle-import") (part "PINHD-1X1"))
    )
    (comp (ref "POW4")
      (value "PINHD-1X1")
      (footprint "eagle-import:1X01")
      (libsource (lib "eagle-import") (part "PINHD-1X1"))
    )
    (comp (ref "R2")
      (value "49Ω")
      (footprint "eagle-import:M0805")
      (libsource (lib "eagle-import") (part "R-US_M0805"))
    )
    (comp (ref "R9")
      (value "240Ω")
      (footprint "eagle-import:M0805")
      (libsource (lib "eagle-import") (part "R-US_M0805"))
    )
    (comp (ref "R10")
      (value "49Ω")
      (footprint "eagle-import:M0805")
      (libsource (lib "eagle-import") (part "R-US_M0805"))
    )
    (comp (ref "R11")
      (value "240Ω")
      (footprint "eagle-import:M0805")
      (libsource (lib "eagle-import") (part "R-US_M0805"))
    )
    (comp (ref "R12")
      (value "390Ω")
      (footprint "eagle-import:M0805")
      (libsource (lib "eagle-import") (part "R-US_M0805"))
    )
    (comp (ref "R151")
      (value "240Ω")
      (footprint "eagle-import:M0805")
      (libsource (lib "eagle-import") (part "R-US_M0805"))
    )
    (comp (ref "R159")
      (value "220")
      (footprint "eagle-import:R0603")
      (libsource (lib "eagle-import") (part "R-EU_R0603"))
    )
    (comp (ref "R160")
      (value "220")
      (footprint "eagle-import:R0603")
      (libsource (lib "eagle-import") (part "R-EU_R0603"))
    )
    (comp (ref "R161")
      (value "220")
      (footprint "eagle-import:R0603")
      (libsource (lib "eagle-import") (part "R-EU_R0603"))
    )
    (comp (ref "R162")
      (value "51")
      (footprint "eagle-import:R0805")
      (libsource (lib "eagle-import") (part "R-EU_R0805"))
    )
    (comp (ref "R163")
      (value "220")
      (footprint "eagle-import:R0603")
      (libsource (lib "eagle-import") (part "R-EU_R0603"))
    )
    (comp (ref "R164")
      (value "220")
      (footprint "eagle-import:R0603")
      (libsource (lib "eagle-import") (part "R-EU_R0603"))
    )
    (comp (ref "R165")
      (value "220")
      (footprint "eagle-import:R0603")
      (libsource (lib "eagle-import") (part "R-EU_R0603"))
    )
    (comp (ref "R166")
      (value "220")
      (footprint "eagle-import:R0603")
      (libsource (lib "eagle-import") (part "R-EU_R0603"))
    )
    (comp (ref "TF17_TP1")
      (value "PINHD-1X1")
      (footprint "eagle-import:1X01")
      (libsource (lib "eagle-import") (part "PINHD-1X1"))
    )
    (comp (ref "U1")
      (value "DF10S")
      (footprint "eagle-import:SOT508P985X260-4N")
      (fields (field (name "DIGI-KEY_PART_NUMBER") "DF10STR-ND") (field (name "MF") "ON"))
      (libsource (lib "eagle-import") (part "DF10S"))
    )
    (comp (ref "U2")
      (value "MC79GENERICD2T")
      (footprint "eagle-import:D2PAK-3")
      (libsource (lib "eagle-import") (part "MC79D2TGENERIC"))
    )
    (comp (ref "U38")
      (value "CPH3355-TL-W")
      (footprint "eagle-import:CPH3_2P9X1P6_ONS")
      (fields (field (name "COPYRIGHT") "Copyright (C) 2022 Ultra Librarian. All rights reserved."))
      (libsource (lib "eagle-import") (part "CPH3355-TL-W"))
    )
    (comp (ref "U39")
      (value "TLV3501AID")
      (footprint "eagle-import:D8")
      (fields (field (name "COPYRIGHT") "Copyright (C) 2022 Ultra Librarian. All rights reserved."))
      (libsource (lib "eagle-import") (part "TLV3501AID"))
    )
    (comp (ref "U40")
      (value "TLV3501AID")
      (footprint "eagle-import:D8")
      (fields (field (name "COPYRIGHT") "Copyright (C) 2022 Ultra Librarian. All rights reserved."))
      (libsource (lib "eagle-import") (part "TLV3501AID"))
    )
    (comp (ref "X2")
      (value "22-23-2041")
      (footprint "eagle-import:22-23-2041")
      (fields (field (name "MF") "MOLEX"))
      (libsource (lib "eagle-import") (part "22-23-2041"))
    )
    (comp (ref "C60")
      (value "0.1uF")
      (footprint "eagle-import:C0805")
      (libsource (lib "eagle-import") (part "C-EUC0805"))
    )
    (comp (ref "C61")
      (value "0.1uF")
      (footprint "eagle-import:C0805")
      (libsource (lib "eagle-import") (part "C-EUC0805"))
    )
    (comp (ref "C62")
      (value "2.2uF")
      (footprint "eagle-import:C0805")
      (libsource (lib "eagle-import") (part "C-EUC0805"))
    )
    (comp (ref "C63")
      (value "2.2uF")
      (footprint "eagle-import:C0805")
      (libsource (lib "eagle-import") (part "C-EUC0805"))
    )
    (comp (ref "FROM_FPGA_13")
      (value "PINHD-1X1")
      (footprint "eagle-import:1X01")
      (libsource (lib "eagle-import") (part "PINHD-1X1"))
    )
    (comp (ref "JP_DRAIN12")
      (value "PINHD-1X1")
      (footprint "eagle-import:1X01")
      (libsource (lib "eagle-import") (part "PINHD-1X1"))
    )
    (comp (ref "JP_GATE13")
      (value "PINHD-1X1")
      (footprint "eagle-import:1X01")
      (libsource (lib "eagle-import") (part "PINHD-1X1"))
    )
    (comp (ref "JP_MIPS13")
      (value "PINHD-1X1")
      (footprint "eagle-import:1X01")
      (libsource (lib "eagle-import") (part "PINHD-1X1"))
    )
    (comp (ref "R114")
      (value "130")
      (footprint "eagle-import:R0805")
      (libsource (lib "eagle-import") (part "R-EU_R0805"))
    )
    (comp (ref "R115")
      (value "130")
      (footprint "eagle-import:R0603")
      (libsource (lib "eagle-import") (part "R-EU_R0603"))
    )
    (comp (ref "R116")
      (value "220")
      (footprint "eagle-import:R0805")
      (libsource (lib "eagle-import") (part "R-EU_R0805"))
    )
    (comp (ref "R117")
      (value "220")
      (footprint "eagle-import:R0805")
      (libsource (lib "eagle-import") (part "R-EU_R0805"))
    )
    (comp (ref "R118")
      (value "130")
      (footprint "eagle-import:R0805")
      (libsource (lib "eagle-import") (part "R-EU_R0805"))
    )
    (comp (ref "R119")
      (value "220")
      (footprint "eagle-import:R0805")
      (libsource (lib "eagle-import") (part "R-EU_R0805"))
    )
    (comp (ref "R120")
      (value "130")
      (footprint "eagle-import:R0805")
      (libsource (lib "eagle-import") (part "R-EU_R0805"))
    )
    (comp (ref "R121")
      (value "220")
      (footprint "eagle-import:R0805")
      (libsource (lib "eagle-import") (part "R-EU_R0805"))
    )
    (comp (ref "R122")
      (value "220")
      (footprint "eagle-import:R0805")
      (libsource (lib "eagle-import") (part "R-EU_R0805"))
    )
    (comp (ref "S25")
      (value "SM-3TW102")
      (footprint "eagle-import:SM3TW102")
      (fields (field (name "MOUSER_PART_NUMBER") "229-SM-3TW102"))
      (libsource (lib "eagle-import") (part "SM-3TW102"))
    )
    (comp (ref "S26")
      (value "SM-3TW102")
      (footprint "eagle-import:SM3TW102")
      (fields (field (name "MOUSER_PART_NUMBER") "229-SM-3TW102"))
      (libsource (lib "eagle-import") (part "SM-3TW102"))
    )
    (comp (ref "TO_FPGA_13")
      (value "PINHD-1X1")
      (footprint "eagle-import:1X01")
      (libsource (lib "eagle-import") (part "PINHD-1X1"))
    )
    (comp (ref "U27")
      (value "TLV3501AID")
      (footprint "eagle-import:D8")
      (fields (field (name "COPYRIGHT") "Copyright (C) 2022 Ultra Librarian. All rights reserved."))
      (libsource (lib "eagle-import") (part "TLV3501AID"))
    )
    (comp (ref "U28")
      (value "TLV3501AID")
      (footprint "eagle-import:D8")
      (fields (field (name "COPYRIGHT") "Copyright (C) 2022 Ultra Librarian. All rights reserved."))
      (libsource (lib "eagle-import") (part "TLV3501AID"))
    )
    (comp (ref "C76")
      (value "0.1uF")
      (footprint "eagle-import:C0805")
      (libsource (lib "eagle-import") (part "C-EUC0805"))
    )
    (comp (ref "C77")
      (value "0.1uF")
      (footprint "eagle-import:C0805")
      (libsource (lib "eagle-import") (part "C-EUC0805"))
    )
    (comp (ref "C78")
      (value "2.2uF")
      (footprint "eagle-import:C0805")
      (libsource (lib "eagle-import") (part "C-EUC0805"))
    )
    (comp (ref "C79")
      (value "2.2uF")
      (footprint "eagle-import:C0805")
      (libsource (lib "eagle-import") (part "C-EUC0805"))
    )
    (comp (ref "FROM_FPGA_17")
      (value "PINHD-1X1")
      (footprint "eagle-import:1X01")
      (libsource (lib "eagle-import") (part "PINHD-1X1"))
    )
    (comp (ref "JP_DRAIN16")
      (value "PINHD-1X1")
      (footprint "eagle-import:1X01")
      (libsource (lib "eagle-import") (part "PINHD-1X1"))
    )
    (comp (ref "JP_GATE17")
      (value "PINHD-1X1")
      (footprint "eagle-import:1X01")
      (libsource (lib "eagle-import") (part "PINHD-1X1"))
    )
    (comp (ref "JP_MIPS17")
      (value "PINHD-1X1")
      (footprint "eagle-import:1X01")
      (libsource (lib "eagle-import") (part "PINHD-1X1"))
    )
    (comp (ref "R150")
      (value "130")
      (footprint "eagle-import:R0805")
      (libsource (lib "eagle-import") (part "R-EU_R0805"))
    )
    (comp (ref "R152")
      (value "130")
      (footprint "eagle-import:R0603")
      (libsource (lib "eagle-import") (part "R-EU_R0603"))
    )
    (comp (ref "R153")
      (value "220")
      (footprint "eagle-import:R0805")
      (libsource (lib "eagle-import") (part "R-EU_R0805"))
    )
    (comp (ref "R154")
      (value "220")
      (footprint "eagle-import:R0805")
      (libsource (lib "eagle-import") (part "R-EU_R0805"))
    )
    (comp (ref "R155")
      (value "130")
      (footprint "eagle-import:R0805")
      (libsource (lib "eagle-import") (part "R-EU_R0805"))
    )
    (comp (ref "R156")
      (value "220")
      (footprint "eagle-import:R0805")
      (libsource (lib "eagle-import") (part "R-EU_R0805"))
    )
    (comp (ref "R157")
      (value "130")
      (footprint "eagle-import:R0805")
      (libsource (lib "eagle-import") (part "R-EU_R0805"))
    )
    (comp (ref "R158")
      (value "220")
      (footprint "eagle-import:R0805")
      (libsource (lib "eagle-import") (part "R-EU_R0805"))
    )
    (comp (ref "R167")
      (value "220")
      (footprint "eagle-import:R0805")
      (libsource (lib "eagle-import") (part "R-EU_R0805"))
    )
    (comp (ref "S33")
      (value "SM-3TW102")
      (footprint "eagle-import:SM3TW102")
      (fields (field (name "MOUSER_PART_NUMBER") "229-SM-3TW102"))
      (libsource (lib "eagle-import") (part "SM-3TW102"))
    )
    (comp (ref "S34")
      (value "SM-3TW102")
      (footprint "eagle-import:SM3TW102")
      (fields (field (name "MOUSER_PART_NUMBER") "229-SM-3TW102"))
      (libsource (lib "eagle-import") (part "SM-3TW102"))
    )
    (comp (ref "TO_FPGA_17")
      (value "PINHD-1X1")
      (footprint "eagle-import:1X01")
      (libsource (lib "eagle-import") (part "PINHD-1X1"))
    )
    (comp (ref "U35")
      (value "TLV3501AID")
      (footprint "eagle-import:D8")
      (fields (field (name "COPYRIGHT") "Copyright (C) 2022 Ultra Librarian. All rights reserved."))
      (libsource (lib "eagle-import") (part "TLV3501AID"))
    )
    (comp (ref "U36")
      (value "TLV3501AID")
      (footprint "eagle-import:D8")
      (fields (field (name "COPYRIGHT") "Copyright (C) 2022 Ultra Librarian. All rights reserved."))
      (libsource (lib "eagle-import") (part "TLV3501AID"))
    )
    (comp (ref "C72")
      (value "0.1uF")
      (footprint "eagle-import:C0805")
      (libsource (lib "eagle-import") (part "C-EUC0805"))
    )
    (comp (ref "C73")
      (value "0.1uF")
      (footprint "eagle-import:C0805")
      (libsource (lib "eagle-import") (part "C-EUC0805"))
    )
    (comp (ref "C74")
      (value "2.2uF")
      (footprint "eagle-import:C0805")
      (libsource (lib "eagle-import") (part "C-EUC0805"))
    )
    (comp (ref "C75")
      (value "2.2uF")
      (footprint "eagle-import:C0805")
      (libsource (lib "eagle-import") (part "C-EUC0805"))
    )
    (comp (ref "FROM_FPGA_16")
      (value "PINHD-1X1")
      (footprint "eagle-import:1X01")
      (libsource (lib "eagle-import") (part "PINHD-1X1"))
    )
    (comp (ref "JP_DRAIN15")
      (value "PINHD-1X1")
      (footprint "eagle-import:1X01")
      (libsource (lib "eagle-import") (part "PINHD-1X1"))
    )
    (comp (ref "JP_GATE16")
      (value "PINHD-1X1")
      (footprint "eagle-import:1X01")
      (libsource (lib "eagle-import") (part "PINHD-1X1"))
    )
    (comp (ref "JP_MIPS16")
      (value "PINHD-1X1")
      (footprint "eagle-import:1X01")
      (libsource (lib "eagle-import") (part "PINHD-1X1"))
    )
    (comp (ref "R141")
      (value "130")
      (footprint "eagle-import:R0805")
      (libsource (lib "eagle-import") (part "R-EU_R0805"))
    )
    (comp (ref "R142")
      (value "130")
      (footprint "eagle-import:R0603")
      (libsource (lib "eagle-import") (part "R-EU_R0603"))
    )
    (comp (ref "R143")
      (value "220")
      (footprint "eagle-import:R0805")
      (libsource (lib "eagle-import") (part "R-EU_R0805"))
    )
    (comp (ref "R144")
      (value "220")
      (footprint "eagle-import:R0805")
      (libsource (lib "eagle-import") (part "R-EU_R0805"))
    )
    (comp (ref "R145")
      (value "130")
      (footprint "eagle-import:R0805")
      (libsource (lib "eagle-import") (part "R-EU_R0805"))
    )
    (comp (ref "R146")
      (value "220")
      (footprint "eagle-import:R0805")
      (libsource (lib "eagle-import") (part "R-EU_R0805"))
    )
    (comp (ref "R147")
      (value "130")
      (footprint "eagle-import:R0805")
      (libsource (lib "eagle-import") (part "R-EU_R0805"))
    )
    (comp (ref "R148")
      (value "220")
      (footprint "eagle-import:R0805")
      (libsource (lib "eagle-import") (part "R-EU_R0805"))
    )
    (comp (ref "R149")
      (value "220")
      (footprint "eagle-import:R0805")
      (libsource (lib "eagle-import") (part "R-EU_R0805"))
    )
    (comp (ref "S31")
      (value "SM-3TW102")
      (footprint "eagle-import:SM3TW102")
      (fields (field (name "MOUSER_PART_NUMBER") "229-SM-3TW102"))
      (libsource (lib "eagle-import") (part "SM-3TW102"))
    )
    (comp (ref "S32")
      (value "SM-3TW102")
      (footprint "eagle-import:SM3TW102")
      (fields (field (name "MOUSER_PART_NUMBER") "229-SM-3TW102"))
      (libsource (lib "eagle-import") (part "SM-3TW102"))
    )
    (comp (ref "TO_FPGA_16")
      (value "PINHD-1X1")
      (footprint "eagle-import:1X01")
      (libsource (lib "eagle-import") (part "PINHD-1X1"))
    )
    (comp (ref "U33")
      (value "TLV3501AID")
      (footprint "eagle-import:D8")
      (fields (field (name "COPYRIGHT") "Copyright (C) 2022 Ultra Librarian. All rights reserved."))
      (libsource (lib "eagle-import") (part "TLV3501AID"))
    )
    (comp (ref "U34")
      (value "TLV3501AID")
      (footprint "eagle-import:D8")
      (fields (field (name "COPYRIGHT") "Copyright (C) 2022 Ultra Librarian. All rights reserved."))
      (libsource (lib "eagle-import") (part "TLV3501AID"))
    )
    (comp (ref "C64")
      (value "0.1uF")
      (footprint "eagle-import:C0805")
      (libsource (lib "eagle-import") (part "C-EUC0805"))
    )
    (comp (ref "C65")
      (value "0.1uF")
      (footprint "eagle-import:C0805")
      (libsource (lib "eagle-import") (part "C-EUC0805"))
    )
    (comp (ref "C66")
      (value "2.2uF")
      (footprint "eagle-import:C0805")
      (libsource (lib "eagle-import") (part "C-EUC0805"))
    )
    (comp (ref "C67")
      (value "2.2uF")
      (footprint "eagle-import:C0805")
      (libsource (lib "eagle-import") (part "C-EUC0805"))
    )
    (comp (ref "FROM_FPGA_14")
      (value "PINHD-1X1")
      (footprint "eagle-import:1X01")
      (libsource (lib "eagle-import") (part "PINHD-1X1"))
    )
    (comp (ref "JP_DRAIN13")
      (value "PINHD-1X1")
      (footprint "eagle-import:1X01")
      (libsource (lib "eagle-import") (part "PINHD-1X1"))
    )
    (comp (ref "JP_GATE14")
      (value "PINHD-1X1")
      (footprint "eagle-import:1X01")
      (libsource (lib "eagle-import") (part "PINHD-1X1"))
    )
    (comp (ref "JP_MIPS14")
      (value "PINHD-1X1")
      (footprint "eagle-import:1X01")
      (libsource (lib "eagle-import") (part "PINHD-1X1"))
    )
    (comp (ref "R123")
      (value "130")
      (footprint "eagle-import:R0805")
      (libsource (lib "eagle-import") (part "R-EU_R0805"))
    )
    (comp (ref "R124")
      (value "130")
      (footprint "eagle-import:R0603")
      (libsource (lib "eagle-import") (part "R-EU_R0603"))
    )
    (comp (ref "R125")
      (value "220")
      (footprint "eagle-import:R0805")
      (libsource (lib "eagle-import") (part "R-EU_R0805"))
    )
    (comp (ref "R126")
      (value "220")
      (footprint "eagle-import:R0805")
      (libsource (lib "eagle-import") (part "R-EU_R0805"))
    )
    (comp (ref "R127")
      (value "130")
      (footprint "eagle-import:R0805")
      (libsource (lib "eagle-import") (part "R-EU_R0805"))
    )
    (comp (ref "R128")
      (value "220")
      (footprint "eagle-import:R0805")
      (libsource (lib "eagle-import") (part "R-EU_R0805"))
    )
    (comp (ref "R129")
      (value "130")
      (footprint "eagle-import:R0805")
      (libsource (lib "eagle-import") (part "R-EU_R0805"))
    )
    (comp (ref "R130")
      (value "220")
      (footprint "eagle-import:R0805")
      (libsource (lib "eagle-import") (part "R-EU_R0805"))
    )
    (comp (ref "R131")
      (value "220")
      (footprint "eagle-import:R0805")
      (libsource (lib "eagle-import") (part "R-EU_R0805"))
    )
    (comp (ref "S27")
      (value "SM-3TW102")
      (footprint "eagle-import:SM3TW102")
      (fields (field (name "MOUSER_PART_NUMBER") "229-SM-3TW102"))
      (libsource (lib "eagle-import") (part "SM-3TW102"))
    )
    (comp (ref "S28")
      (value "SM-3TW102")
      (footprint "eagle-import:SM3TW102")
      (fields (field (name "MOUSER_PART_NUMBER") "229-SM-3TW102"))
      (libsource (lib "eagle-import") (part "SM-3TW102"))
    )
    (comp (ref "TO_FPGA_14")
      (value "PINHD-1X1")
      (footprint "eagle-import:1X01")
      (libsource (lib "eagle-import") (part "PINHD-1X1"))
    )
    (comp (ref "U29")
      (value "TLV3501AID")
      (footprint "eagle-import:D8")
      (fields (field (name "COPYRIGHT") "Copyright (C) 2022 Ultra Librarian. All rights reserved."))
      (libsource (lib "eagle-import") (part "TLV3501AID"))
    )
    (comp (ref "U30")
      (value "TLV3501AID")
      (footprint "eagle-import:D8")
      (fields (field (name "COPYRIGHT") "Copyright (C) 2022 Ultra Librarian. All rights reserved."))
      (libsource (lib "eagle-import") (part "TLV3501AID"))
    )
    (comp (ref "C94")
      (value "0.1uF")
      (footprint "eagle-import:C0805")
      (libsource (lib "eagle-import") (part "C-EUC0805"))
    )
    (comp (ref "C95")
      (value "0.1uF")
      (footprint "eagle-import:C0805")
      (libsource (lib "eagle-import") (part "C-EUC0805"))
    )
    (comp (ref "C96")
      (value "2.2uF")
      (footprint "eagle-import:C0805")
      (libsource (lib "eagle-import") (part "C-EUC0805"))
    )
    (comp (ref "C97")
      (value "2.2uF")
      (footprint "eagle-import:C0805")
      (libsource (lib "eagle-import") (part "C-EUC0805"))
    )
    (comp (ref "FROM_FPGA_20")
      (value "PINHD-1X1")
      (footprint "eagle-import:1X01")
      (libsource (lib "eagle-import") (part "PINHD-1X1"))
    )
    (comp (ref "JP_DRAIN19")
      (value "PINHD-1X1")
      (footprint "eagle-import:1X01")
      (libsource (lib "eagle-import") (part "PINHD-1X1"))
    )
    (comp (ref "JP_GATE20")
      (value "PINHD-1X1")
      (footprint "eagle-import:1X01")
      (libsource (lib "eagle-import") (part "PINHD-1X1"))
    )
    (comp (ref "JP_MIPS20")
      (value "PINHD-1X1")
      (footprint "eagle-import:1X01")
      (libsource (lib "eagle-import") (part "PINHD-1X1"))
    )
    (comp (ref "R186")
      (value "130")
      (footprint "eagle-import:R0805")
      (libsource (lib "eagle-import") (part "R-EU_R0805"))
    )
    (comp (ref "R187")
      (value "130")
      (footprint "eagle-import:R0603")
      (libsource (lib "eagle-import") (part "R-EU_R0603"))
    )
    (comp (ref "R188")
      (value "220")
      (footprint "eagle-import:R0805")
      (libsource (lib "eagle-import") (part "R-EU_R0805"))
    )
    (comp (ref "R189")
      (value "220")
      (footprint "eagle-import:R0805")
      (libsource (lib "eagle-import") (part "R-EU_R0805"))
    )
    (comp (ref "R190")
      (value "130")
      (footprint "eagle-import:R0805")
      (libsource (lib "eagle-import") (part "R-EU_R0805"))
    )
    (comp (ref "R191")
      (value "220")
      (footprint "eagle-import:R0805")
      (libsource (lib "eagle-import") (part "R-EU_R0805"))
    )
    (comp (ref "R192")
      (value "130")
      (footprint "eagle-import:R0805")
      (libsource (lib "eagle-import") (part "R-EU_R0805"))
    )
    (comp (ref "R193")
      (value "220")
      (footprint "eagle-import:R0805")
      (libsource (lib "eagle-import") (part "R-EU_R0805"))
    )
    (comp (ref "R194")
      (value "220")
      (footprint "eagle-import:R0805")
      (libsource (lib "eagle-import") (part "R-EU_R0805"))
    )
    (comp (ref "S39")
      (value "SM-3TW102")
      (footprint "eagle-import:SM3TW102")
      (fields (field (name "MOUSER_PART_NUMBER") "229-SM-3TW102"))
      (libsource (lib "eagle-import") (part "SM-3TW102"))
    )
    (comp (ref "S40")
      (value "SM-3TW102")
      (footprint "eagle-import:SM3TW102")
      (fields (field (name "MOUSER_PART_NUMBER") "229-SM-3TW102"))
      (libsource (lib "eagle-import") (part "SM-3TW102"))
    )
    (comp (ref "TO_FPGA_20")
      (value "PINHD-1X1")
      (footprint "eagle-import:1X01")
      (libsource (lib "eagle-import") (part "PINHD-1X1"))
    )
    (comp (ref "U44")
      (value "TLV3501AID")
      (footprint "eagle-import:D8")
      (fields (field (name "COPYRIGHT") "Copyright (C) 2022 Ultra Librarian. All rights reserved."))
      (libsource (lib "eagle-import") (part "TLV3501AID"))
    )
    (comp (ref "U45")
      (value "TLV3501AID")
      (footprint "eagle-import:D8")
      (fields (field (name "COPYRIGHT") "Copyright (C) 2022 Ultra Librarian. All rights reserved."))
      (libsource (lib "eagle-import") (part "TLV3501AID"))
    )
    (comp (ref "C44")
      (value "0.1uF")
      (footprint "eagle-import:C0805")
      (libsource (lib "eagle-import") (part "C-EUC0805"))
    )
    (comp (ref "C45")
      (value "0.1uF")
      (footprint "eagle-import:C0805")
      (libsource (lib "eagle-import") (part "C-EUC0805"))
    )
    (comp (ref "C46")
      (value "2.2uF")
      (footprint "eagle-import:C0805")
      (libsource (lib "eagle-import") (part "C-EUC0805"))
    )
    (comp (ref "C47")
      (value "2.2uF")
      (footprint "eagle-import:C0805")
      (libsource (lib "eagle-import") (part "C-EUC0805"))
    )
    (comp (ref "FROM_FPGA_9")
      (value "PINHD-1X1")
      (footprint "eagle-import:1X01")
      (libsource (lib "eagle-import") (part "PINHD-1X1"))
    )
    (comp (ref "JP_DRAIN8")
      (value "PINHD-1X1")
      (footprint "eagle-import:1X01")
      (libsource (lib "eagle-import") (part "PINHD-1X1"))
    )
    (comp (ref "JP_GATE9")
      (value "PINHD-1X1")
      (footprint "eagle-import:1X01")
      (libsource (lib "eagle-import") (part "PINHD-1X1"))
    )
    (comp (ref "JP_MIPS9")
      (value "PINHD-1X1")
      (footprint "eagle-import:1X01")
      (libsource (lib "eagle-import") (part "PINHD-1X1"))
    )
    (comp (ref "R78")
      (value "130")
      (footprint "eagle-import:R0805")
      (libsource (lib "eagle-import") (part "R-EU_R0805"))
    )
    (comp (ref "R79")
      (value "130")
      (footprint "eagle-import:R0603")
      (libsource (lib "eagle-import") (part "R-EU_R0603"))
    )
    (comp (ref "R80")
      (value "220")
      (footprint "eagle-import:R0805")
      (libsource (lib "eagle-import") (part "R-EU_R0805"))
    )
    (comp (ref "R81")
      (value "220")
      (footprint "eagle-import:R0805")
      (libsource (lib "eagle-import") (part "R-EU_R0805"))
    )
    (comp (ref "R82")
      (value "130")
      (footprint "eagle-import:R0805")
      (libsource (lib "eagle-import") (part "R-EU_R0805"))
    )
    (comp (ref "R83")
      (value "220")
      (footprint "eagle-import:R0805")
      (libsource (lib "eagle-import") (part "R-EU_R0805"))
    )
    (comp (ref "R84")
      (value "130")
      (footprint "eagle-import:R0805")
      (libsource (lib "eagle-import") (part "R-EU_R0805"))
    )
    (comp (ref "R85")
      (value "220")
      (footprint "eagle-import:R0805")
      (libsource (lib "eagle-import") (part "R-EU_R0805"))
    )
    (comp (ref "R86")
      (value "220")
      (footprint "eagle-import:R0805")
      (libsource (lib "eagle-import") (part "R-EU_R0805"))
    )
    (comp (ref "S17")
      (value "SM-3TW102")
      (footprint "eagle-import:SM3TW102")
      (fields (field (name "MOUSER_PART_NUMBER") "229-SM-3TW102"))
      (libsource (lib "eagle-import") (part "SM-3TW102"))
    )
    (comp (ref "S18")
      (value "SM-3TW102")
      (footprint "eagle-import:SM3TW102")
      (fields (field (name "MOUSER_PART_NUMBER") "229-SM-3TW102"))
      (libsource (lib "eagle-import") (part "SM-3TW102"))
    )
    (comp (ref "TO_FPGA_9")
      (value "PINHD-1X1")
      (footprint "eagle-import:1X01")
      (libsource (lib "eagle-import") (part "PINHD-1X1"))
    )
    (comp (ref "U19")
      (value "TLV3501AID")
      (footprint "eagle-import:D8")
      (fields (field (name "COPYRIGHT") "Copyright (C) 2022 Ultra Librarian. All rights reserved."))
      (libsource (lib "eagle-import") (part "TLV3501AID"))
    )
    (comp (ref "U20")
      (value "TLV3501AID")
      (footprint "eagle-import:D8")
      (fields (field (name "COPYRIGHT") "Copyright (C) 2022 Ultra Librarian. All rights reserved."))
      (libsource (lib "eagle-import") (part "TLV3501AID"))
    )
    (comp (ref "C32")
      (value "0.1uF")
      (footprint "eagle-import:C0805")
      (libsource (lib "eagle-import") (part "C-EUC0805"))
    )
    (comp (ref "C33")
      (value "0.1uF")
      (footprint "eagle-import:C0805")
      (libsource (lib "eagle-import") (part "C-EUC0805"))
    )
    (comp (ref "C34")
      (value "2.2uF")
      (footprint "eagle-import:C0805")
      (libsource (lib "eagle-import") (part "C-EUC0805"))
    )
    (comp (ref "C35")
      (value "2.2uF")
      (footprint "eagle-import:C0805")
      (libsource (lib "eagle-import") (part "C-EUC0805"))
    )
    (comp (ref "FROM_FPGA_6")
      (value "PINHD-1X1")
      (footprint "eagle-import:1X01")
      (libsource (lib "eagle-import") (part "PINHD-1X1"))
    )
    (comp (ref "JP_DRAIN5")
      (value "PINHD-1X1")
      (footprint "eagle-import:1X01")
      (libsource (lib "eagle-import") (part "PINHD-1X1"))
    )
    (comp (ref "JP_GATE6")
      (value "PINHD-1X1")
      (footprint "eagle-import:1X01")
      (libsource (lib "eagle-import") (part "PINHD-1X1"))
    )
    (comp (ref "JP_MIPS6")
      (value "PINHD-1X1")
      (footprint "eagle-import:1X01")
      (libsource (lib "eagle-import") (part "PINHD-1X1"))
    )
    (comp (ref "R51")
      (value "130")
      (footprint "eagle-import:R0805")
      (libsource (lib "eagle-import") (part "R-EU_R0805"))
    )
    (comp (ref "R52")
      (value "130")
      (footprint "eagle-import:R0603")
      (libsource (lib "eagle-import") (part "R-EU_R0603"))
    )
    (comp (ref "R53")
      (value "220")
      (footprint "eagle-import:R0805")
      (libsource (lib "eagle-import") (part "R-EU_R0805"))
    )
    (comp (ref "R54")
      (value "220")
      (footprint "eagle-import:R0805")
      (libsource (lib "eagle-import") (part "R-EU_R0805"))
    )
    (comp (ref "R55")
      (value "130")
      (footprint "eagle-import:R0805")
      (libsource (lib "eagle-import") (part "R-EU_R0805"))
    )
    (comp (ref "R56")
      (value "220")
      (footprint "eagle-import:R0805")
      (libsource (lib "eagle-import") (part "R-EU_R0805"))
    )
    (comp (ref "R57")
      (value "130")
      (footprint "eagle-import:R0805")
      (libsource (lib "eagle-import") (part "R-EU_R0805"))
    )
    (comp (ref "R58")
      (value "220")
      (footprint "eagle-import:R0805")
      (libsource (lib "eagle-import") (part "R-EU_R0805"))
    )
    (comp (ref "R59")
      (value "220")
      (footprint "eagle-import:R0805")
      (libsource (lib "eagle-import") (part "R-EU_R0805"))
    )
    (comp (ref "S11")
      (value "SM-3TW102")
      (footprint "eagle-import:SM3TW102")
      (fields (field (name "MOUSER_PART_NUMBER") "229-SM-3TW102"))
      (libsource (lib "eagle-import") (part "SM-3TW102"))
    )
    (comp (ref "S12")
      (value "SM-3TW102")
      (footprint "eagle-import:SM3TW102")
      (fields (field (name "MOUSER_PART_NUMBER") "229-SM-3TW102"))
      (libsource (lib "eagle-import") (part "SM-3TW102"))
    )
    (comp (ref "TO_FPGA_6")
      (value "PINHD-1X1")
      (footprint "eagle-import:1X01")
      (libsource (lib "eagle-import") (part "PINHD-1X1"))
    )
    (comp (ref "U13")
      (value "TLV3501AID")
      (footprint "eagle-import:D8")
      (fields (field (name "COPYRIGHT") "Copyright (C) 2022 Ultra Librarian. All rights reserved."))
      (libsource (lib "eagle-import") (part "TLV3501AID"))
    )
    (comp (ref "U14")
      (value "TLV3501AID")
      (footprint "eagle-import:D8")
      (fields (field (name "COPYRIGHT") "Copyright (C) 2022 Ultra Librarian. All rights reserved."))
      (libsource (lib "eagle-import") (part "TLV3501AID"))
    )
    (comp (ref "C24")
      (value "0.1uF")
      (footprint "eagle-import:C0805")
      (libsource (lib "eagle-import") (part "C-EUC0805"))
    )
    (comp (ref "C25")
      (value "0.1uF")
      (footprint "eagle-import:C0805")
      (libsource (lib "eagle-import") (part "C-EUC0805"))
    )
    (comp (ref "C26")
      (value "2.2uF")
      (footprint "eagle-import:C0805")
      (libsource (lib "eagle-import") (part "C-EUC0805"))
    )
    (comp (ref "C27")
      (value "2.2uF")
      (footprint "eagle-import:C0805")
      (libsource (lib "eagle-import") (part "C-EUC0805"))
    )
    (comp (ref "FROM_FPGA_4")
      (value "PINHD-1X1")
      (footprint "eagle-import:1X01")
      (libsource (lib "eagle-import") (part "PINHD-1X1"))
    )
    (comp (ref "JP_DRAIN3")
      (value "PINHD-1X1")
      (footprint "eagle-import:1X01")
      (libsource (lib "eagle-import") (part "PINHD-1X1"))
    )
    (comp (ref "JP_GATE4")
      (value "PINHD-1X1")
      (footprint "eagle-import:1X01")
      (libsource (lib "eagle-import") (part "PINHD-1X1"))
    )
    (comp (ref "JP_MIPS4")
      (value "PINHD-1X1")
      (footprint "eagle-import:1X01")
      (libsource (lib "eagle-import") (part "PINHD-1X1"))
    )
    (comp (ref "R33")
      (value "130")
      (footprint "eagle-import:R0805")
      (libsource (lib "eagle-import") (part "R-EU_R0805"))
    )
    (comp (ref "R34")
      (value "130")
      (footprint "eagle-import:R0603")
      (libsource (lib "eagle-import") (part "R-EU_R0603"))
    )
    (comp (ref "R35")
      (value "220")
      (footprint "eagle-import:R0805")
      (libsource (lib "eagle-import") (part "R-EU_R0805"))
    )
    (comp (ref "R36")
      (value "220")
      (footprint "eagle-import:R0805")
      (libsource (lib "eagle-import") (part "R-EU_R0805"))
    )
    (comp (ref "R37")
      (value "130")
      (footprint "eagle-import:R0805")
      (libsource (lib "eagle-import") (part "R-EU_R0805"))
    )
    (comp (ref "R38")
      (value "220")
      (footprint "eagle-import:R0805")
      (libsource (lib "eagle-import") (part "R-EU_R0805"))
    )
    (comp (ref "R39")
      (value "130")
      (footprint "eagle-import:R0805")
      (libsource (lib "eagle-import") (part "R-EU_R0805"))
    )
    (comp (ref "R40")
      (value "220")
      (footprint "eagle-import:R0805")
      (libsource (lib "eagle-import") (part "R-EU_R0805"))
    )
    (comp (ref "R41")
      (value "220")
      (footprint "eagle-import:R0805")
      (libsource (lib "eagle-import") (part "R-EU_R0805"))
    )
    (comp (ref "S7")
      (value "SM-3TW102")
      (footprint "eagle-import:SM3TW102")
      (fields (field (name "MOUSER_PART_NUMBER") "229-SM-3TW102"))
      (libsource (lib "eagle-import") (part "SM-3TW102"))
    )
    (comp (ref "S8")
      (value "SM-3TW102")
      (footprint "eagle-import:SM3TW102")
      (fields (field (name "MOUSER_PART_NUMBER") "229-SM-3TW102"))
      (libsource (lib "eagle-import") (part "SM-3TW102"))
    )
    (comp (ref "TO_FPGA_4")
      (value "PINHD-1X1")
      (footprint "eagle-import:1X01")
      (libsource (lib "eagle-import") (part "PINHD-1X1"))
    )
    (comp (ref "U9")
      (value "TLV3501AID")
      (footprint "eagle-import:D8")
      (fields (field (name "COPYRIGHT") "Copyright (C) 2022 Ultra Librarian. All rights reserved."))
      (libsource (lib "eagle-import") (part "TLV3501AID"))
    )
    (comp (ref "U10")
      (value "TLV3501AID")
      (footprint "eagle-import:D8")
      (fields (field (name "COPYRIGHT") "Copyright (C) 2022 Ultra Librarian. All rights reserved."))
      (libsource (lib "eagle-import") (part "TLV3501AID"))
    )
    (comp (ref "C56")
      (value "0.1uF")
      (footprint "eagle-import:C0805")
      (libsource (lib "eagle-import") (part "C-EUC0805"))
    )
    (comp (ref "C57")
      (value "0.1uF")
      (footprint "eagle-import:C0805")
      (libsource (lib "eagle-import") (part "C-EUC0805"))
    )
    (comp (ref "C58")
      (value "2.2uF")
      (footprint "eagle-import:C0805")
      (libsource (lib "eagle-import") (part "C-EUC0805"))
    )
    (comp (ref "C59")
      (value "2.2uF")
      (footprint "eagle-import:C0805")
      (libsource (lib "eagle-import") (part "C-EUC0805"))
    )
    (comp (ref "FROM_FPGA_12")
      (value "PINHD-1X1")
      (footprint "eagle-import:1X01")
      (libsource (lib "eagle-import") (part "PINHD-1X1"))
    )
    (comp (ref "JP_DRAIN11")
      (value "PINHD-1X1")
      (footprint "eagle-import:1X01")
      (libsource (lib "eagle-import") (part "PINHD-1X1"))
    )
    (comp (ref "JP_GATE12")
      (value "PINHD-1X1")
      (footprint "eagle-import:1X01")
      (libsource (lib "eagle-import") (part "PINHD-1X1"))
    )
    (comp (ref "JP_MIPS12")
      (value "PINHD-1X1")
      (footprint "eagle-import:1X01")
      (libsource (lib "eagle-import") (part "PINHD-1X1"))
    )
    (comp (ref "R105")
      (value "130")
      (footprint "eagle-import:R0805")
      (libsource (lib "eagle-import") (part "R-EU_R0805"))
    )
    (comp (ref "R106")
      (value "130")
      (footprint "eagle-import:R0603")
      (libsource (lib "eagle-import") (part "R-EU_R0603"))
    )
    (comp (ref "R107")
      (value "220")
      (footprint "eagle-import:R0805")
      (libsource (lib "eagle-import") (part "R-EU_R0805"))
    )
    (comp (ref "R108")
      (value "220")
      (footprint "eagle-import:R0805")
      (libsource (lib "eagle-import") (part "R-EU_R0805"))
    )
    (comp (ref "R109")
      (value "130")
      (footprint "eagle-import:R0805")
      (libsource (lib "eagle-import") (part "R-EU_R0805"))
    )
    (comp (ref "R110")
      (value "220")
      (footprint "eagle-import:R0805")
      (libsource (lib "eagle-import") (part "R-EU_R0805"))
    )
    (comp (ref "R111")
      (value "130")
      (footprint "eagle-import:R0805")
      (libsource (lib "eagle-import") (part "R-EU_R0805"))
    )
    (comp (ref "R112")
      (value "220")
      (footprint "eagle-import:R0805")
      (libsource (lib "eagle-import") (part "R-EU_R0805"))
    )
    (comp (ref "R113")
      (value "220")
      (footprint "eagle-import:R0805")
      (libsource (lib "eagle-import") (part "R-EU_R0805"))
    )
    (comp (ref "S23")
      (value "SM-3TW102")
      (footprint "eagle-import:SM3TW102")
      (fields (field (name "MOUSER_PART_NUMBER") "229-SM-3TW102"))
      (libsource (lib "eagle-import") (part "SM-3TW102"))
    )
    (comp (ref "S24")
      (value "SM-3TW102")
      (footprint "eagle-import:SM3TW102")
      (fields (field (name "MOUSER_PART_NUMBER") "229-SM-3TW102"))
      (libsource (lib "eagle-import") (part "SM-3TW102"))
    )
    (comp (ref "TO_FPGA_12")
      (value "PINHD-1X1")
      (footprint "eagle-import:1X01")
      (libsource (lib "eagle-import") (part "PINHD-1X1"))
    )
    (comp (ref "U25")
      (value "TLV3501AID")
      (footprint "eagle-import:D8")
      (fields (field (name "COPYRIGHT") "Copyright (C) 2022 Ultra Librarian. All rights reserved."))
      (libsource (lib "eagle-import") (part "TLV3501AID"))
    )
    (comp (ref "U26")
      (value "TLV3501AID")
      (footprint "eagle-import:D8")
      (fields (field (name "COPYRIGHT") "Copyright (C) 2022 Ultra Librarian. All rights reserved."))
      (libsource (lib "eagle-import") (part "TLV3501AID"))
    )
    (comp (ref "C48")
      (value "0.1uF")
      (footprint "eagle-import:C0805")
      (libsource (lib "eagle-import") (part "C-EUC0805"))
    )
    (comp (ref "C49")
      (value "0.1uF")
      (footprint "eagle-import:C0805")
      (libsource (lib "eagle-import") (part "C-EUC0805"))
    )
    (comp (ref "C50")
      (value "2.2uF")
      (footprint "eagle-import:C0805")
      (libsource (lib "eagle-import") (part "C-EUC0805"))
    )
    (comp (ref "C51")
      (value "2.2uF")
      (footprint "eagle-import:C0805")
      (libsource (lib "eagle-import") (part "C-EUC0805"))
    )
    (comp (ref "FROM_FPGA_10")
      (value "PINHD-1X1")
      (footprint "eagle-import:1X01")
      (libsource (lib "eagle-import") (part "PINHD-1X1"))
    )
    (comp (ref "JP_DRAIN9")
      (value "PINHD-1X1")
      (footprint "eagle-import:1X01")
      (libsource (lib "eagle-import") (part "PINHD-1X1"))
    )
    (comp (ref "JP_GATE10")
      (value "PINHD-1X1")
      (footprint "eagle-import:1X01")
      (libsource (lib "eagle-import") (part "PINHD-1X1"))
    )
    (comp (ref "JP_MIPS10")
      (value "PINHD-1X1")
      (footprint "eagle-import:1X01")
      (libsource (lib "eagle-import") (part "PINHD-1X1"))
    )
    (comp (ref "R87")
      (value "130")
      (footprint "eagle-import:R0805")
      (libsource (lib "eagle-import") (part "R-EU_R0805"))
    )
    (comp (ref "R88")
      (value "130")
      (footprint "eagle-import:R0603")
      (libsource (lib "eagle-import") (part "R-EU_R0603"))
    )
    (comp (ref "R89")
      (value "220")
      (footprint "eagle-import:R0805")
      (libsource (lib "eagle-import") (part "R-EU_R0805"))
    )
    (comp (ref "R90")
      (value "220")
      (footprint "eagle-import:R0805")
      (libsource (lib "eagle-import") (part "R-EU_R0805"))
    )
    (comp (ref "R91")
      (value "130")
      (footprint "eagle-import:R0805")
      (libsource (lib "eagle-import") (part "R-EU_R0805"))
    )
    (comp (ref "R92")
      (value "220")
      (footprint "eagle-import:R0805")
      (libsource (lib "eagle-import") (part "R-EU_R0805"))
    )
    (comp (ref "R93")
      (value "130")
      (footprint "eagle-import:R0805")
      (libsource (lib "eagle-import") (part "R-EU_R0805"))
    )
    (comp (ref "R94")
      (value "220")
      (footprint "eagle-import:R0805")
      (libsource (lib "eagle-import") (part "R-EU_R0805"))
    )
    (comp (ref "R95")
      (value "220")
      (footprint "eagle-import:R0805")
      (libsource (lib "eagle-import") (part "R-EU_R0805"))
    )
    (comp (ref "S19")
      (value "SM-3TW102")
      (footprint "eagle-import:SM3TW102")
      (fields (field (name "MOUSER_PART_NUMBER") "229-SM-3TW102"))
      (libsource (lib "eagle-import") (part "SM-3TW102"))
    )
    (comp (ref "S20")
      (value "SM-3TW102")
      (footprint "eagle-import:SM3TW102")
      (fields (field (name "MOUSER_PART_NUMBER") "229-SM-3TW102"))
      (libsource (lib "eagle-import") (part "SM-3TW102"))
    )
    (comp (ref "TO_FPGA_10")
      (value "PINHD-1X1")
      (footprint "eagle-import:1X01")
      (libsource (lib "eagle-import") (part "PINHD-1X1"))
    )
    (comp (ref "U21")
      (value "TLV3501AID")
      (footprint "eagle-import:D8")
      (fields (field (name "COPYRIGHT") "Copyright (C) 2022 Ultra Librarian. All rights reserved."))
      (libsource (lib "eagle-import") (part "TLV3501AID"))
    )
    (comp (ref "U22")
      (value "TLV3501AID")
      (footprint "eagle-import:D8")
      (fields (field (name "COPYRIGHT") "Copyright (C) 2022 Ultra Librarian. All rights reserved."))
      (libsource (lib "eagle-import") (part "TLV3501AID"))
    )
    (comp (ref "C36")
      (value "0.1uF")
      (footprint "eagle-import:C0805")
      (libsource (lib "eagle-import") (part "C-EUC0805"))
    )
    (comp (ref "C37")
      (value "0.1uF")
      (footprint "eagle-import:C0805")
      (libsource (lib "eagle-import") (part "C-EUC0805"))
    )
    (comp (ref "C38")
      (value "2.2uF")
      (footprint "eagle-import:C0805")
      (libsource (lib "eagle-import") (part "C-EUC0805"))
    )
    (comp (ref "C39")
      (value "2.2uF")
      (footprint "eagle-import:C0805")
      (libsource (lib "eagle-import") (part "C-EUC0805"))
    )
    (comp (ref "FROM_FPGA_7")
      (value "PINHD-1X1")
      (footprint "eagle-import:1X01")
      (libsource (lib "eagle-import") (part "PINHD-1X1"))
    )
    (comp (ref "JP_DRAIN6")
      (value "PINHD-1X1")
      (footprint "eagle-import:1X01")
      (libsource (lib "eagle-import") (part "PINHD-1X1"))
    )
    (comp (ref "JP_GATE7")
      (value "PINHD-1X1")
      (footprint "eagle-import:1X01")
      (libsource (lib "eagle-import") (part "PINHD-1X1"))
    )
    (comp (ref "JP_MIPS7")
      (value "PINHD-1X1")
      (footprint "eagle-import:1X01")
      (libsource (lib "eagle-import") (part "PINHD-1X1"))
    )
    (comp (ref "R60")
      (value "130")
      (footprint "eagle-import:R0805")
      (libsource (lib "eagle-import") (part "R-EU_R0805"))
    )
    (comp (ref "R61")
      (value "130")
      (footprint "eagle-import:R0603")
      (libsource (lib "eagle-import") (part "R-EU_R0603"))
    )
    (comp (ref "R62")
      (value "220")
      (footprint "eagle-import:R0805")
      (libsource (lib "eagle-import") (part "R-EU_R0805"))
    )
    (comp (ref "R63")
      (value "220")
      (footprint "eagle-import:R0805")
      (libsource (lib "eagle-import") (part "R-EU_R0805"))
    )
    (comp (ref "R64")
      (value "130")
      (footprint "eagle-import:R0805")
      (libsource (lib "eagle-import") (part "R-EU_R0805"))
    )
    (comp (ref "R65")
      (value "220")
      (footprint "eagle-import:R0805")
      (libsource (lib "eagle-import") (part "R-EU_R0805"))
    )
    (comp (ref "R66")
      (value "130")
      (footprint "eagle-import:R0805")
      (libsource (lib "eagle-import") (part "R-EU_R0805"))
    )
    (comp (ref "R67")
      (value "220")
      (footprint "eagle-import:R0805")
      (libsource (lib "eagle-import") (part "R-EU_R0805"))
    )
    (comp (ref "R68")
      (value "220")
      (footprint "eagle-import:R0805")
      (libsource (lib "eagle-import") (part "R-EU_R0805"))
    )
    (comp (ref "S13")
      (value "SM-3TW102")
      (footprint "eagle-import:SM3TW102")
      (fields (field (name "MOUSER_PART_NUMBER") "229-SM-3TW102"))
      (libsource (lib "eagle-import") (part "SM-3TW102"))
    )
    (comp (ref "S14")
      (value "SM-3TW102")
      (footprint "eagle-import:SM3TW102")
      (fields (field (name "MOUSER_PART_NUMBER") "229-SM-3TW102"))
      (libsource (lib "eagle-import") (part "SM-3TW102"))
    )
    (comp (ref "TO_FPGA_7")
      (value "PINHD-1X1")
      (footprint "eagle-import:1X01")
      (libsource (lib "eagle-import") (part "PINHD-1X1"))
    )
    (comp (ref "U15")
      (value "TLV3501AID")
      (footprint "eagle-import:D8")
      (fields (field (name "COPYRIGHT") "Copyright (C) 2022 Ultra Librarian. All rights reserved."))
      (libsource (lib "eagle-import") (part "TLV3501AID"))
    )
    (comp (ref "U16")
      (value "TLV3501AID")
      (footprint "eagle-import:D8")
      (fields (field (name "COPYRIGHT") "Copyright (C) 2022 Ultra Librarian. All rights reserved."))
      (libsource (lib "eagle-import") (part "TLV3501AID"))
    )
    (comp (ref "C40")
      (value "0.1uF")
      (footprint "eagle-import:C0805")
      (libsource (lib "eagle-import") (part "C-EUC0805"))
    )
    (comp (ref "C41")
      (value "0.1uF")
      (footprint "eagle-import:C0805")
      (libsource (lib "eagle-import") (part "C-EUC0805"))
    )
    (comp (ref "C42")
      (value "2.2uF")
      (footprint "eagle-import:C0805")
      (libsource (lib "eagle-import") (part "C-EUC0805"))
    )
    (comp (ref "C43")
      (value "2.2uF")
      (footprint "eagle-import:C0805")
      (libsource (lib "eagle-import") (part "C-EUC0805"))
    )
    (comp (ref "FROM_FPGA_8")
      (value "PINHD-1X1")
      (footprint "eagle-import:1X01")
      (libsource (lib "eagle-import") (part "PINHD-1X1"))
    )
    (comp (ref "JP_DRAIN7")
      (value "PINHD-1X1")
      (footprint "eagle-import:1X01")
      (libsource (lib "eagle-import") (part "PINHD-1X1"))
    )
    (comp (ref "JP_GATE8")
      (value "PINHD-1X1")
      (footprint "eagle-import:1X01")
      (libsource (lib "eagle-import") (part "PINHD-1X1"))
    )
    (comp (ref "JP_MIPS8")
      (value "PINHD-1X1")
      (footprint "eagle-import:1X01")
      (libsource (lib "eagle-import") (part "PINHD-1X1"))
    )
    (comp (ref "R69")
      (value "130")
      (footprint "eagle-import:R0805")
      (libsource (lib "eagle-import") (part "R-EU_R0805"))
    )
    (comp (ref "R70")
      (value "130")
      (footprint "eagle-import:R0603")
      (libsource (lib "eagle-import") (part "R-EU_R0603"))
    )
    (comp (ref "R71")
      (value "220")
      (footprint "eagle-import:R0805")
      (libsource (lib "eagle-import") (part "R-EU_R0805"))
    )
    (comp (ref "R72")
      (value "220")
      (footprint "eagle-import:R0805")
      (libsource (lib "eagle-import") (part "R-EU_R0805"))
    )
    (comp (ref "R73")
      (value "130")
      (footprint "eagle-import:R0805")
      (libsource (lib "eagle-import") (part "R-EU_R0805"))
    )
    (comp (ref "R74")
      (value "220")
      (footprint "eagle-import:R0805")
      (libsource (lib "eagle-import") (part "R-EU_R0805"))
    )
    (comp (ref "R75")
      (value "130")
      (footprint "eagle-import:R0805")
      (libsource (lib "eagle-import") (part "R-EU_R0805"))
    )
    (comp (ref "R76")
      (value "220")
      (footprint "eagle-import:R0805")
      (libsource (lib "eagle-import") (part "R-EU_R0805"))
    )
    (comp (ref "R77")
      (value "220")
      (footprint "eagle-import:R0805")
      (libsource (lib "eagle-import") (part "R-EU_R0805"))
    )
    (comp (ref "S15")
      (value "SM-3TW102")
      (footprint "eagle-import:SM3TW102")
      (fields (field (name "MOUSER_PART_NUMBER") "229-SM-3TW102"))
      (libsource (lib "eagle-import") (part "SM-3TW102"))
    )
    (comp (ref "S16")
      (value "SM-3TW102")
      (footprint "eagle-import:SM3TW102")
      (fields (field (name "MOUSER_PART_NUMBER") "229-SM-3TW102"))
      (libsource (lib "eagle-import") (part "SM-3TW102"))
    )
    (comp (ref "TO_FPGA_8")
      (value "PINHD-1X1")
      (footprint "eagle-import:1X01")
      (libsource (lib "eagle-import") (part "PINHD-1X1"))
    )
    (comp (ref "U17")
      (value "TLV3501AID")
      (footprint "eagle-import:D8")
      (fields (field (name "COPYRIGHT") "Copyright (C) 2022 Ultra Librarian. All rights reserved."))
      (libsource (lib "eagle-import") (part "TLV3501AID"))
    )
    (comp (ref "U18")
      (value "TLV3501AID")
      (footprint "eagle-import:D8")
      (fields (field (name "COPYRIGHT") "Copyright (C) 2022 Ultra Librarian. All rights reserved."))
      (libsource (lib "eagle-import") (part "TLV3501AID"))
    )
  )
  (nets
    (net (code "1") (name "+1.5V") (class "Default")
      (node (ref "+1.5V_TP1") (pin "1") (pinfunction "1_1") (pintype "passive"))
      (node (ref "+1.5V_TP2") (pin "1") (pinfunction "1_1") (pintype "passive"))
      (node (ref "C13") (pin "2") (pinfunction "2_2") (pintype "passive"))
      (node (ref "C15") (pin "2") (pinfunction "2_2") (pintype "passive"))
      (node (ref "C20") (pin "2") (pinfunction "2_2") (pintype "passive"))
      (node (ref "C22") (pin "2") (pinfunction "2_2") (pintype "passive"))
      (node (ref "C24") (pin "2") (pinfunction "2_2") (pintype "passive"))
      (node (ref "C26") (pin "2") (pinfunction "2_2") (pintype "passive"))
      (node (ref "C28") (pin "2") (pinfunction "2_2") (pintype "passive"))
      (node (ref "C30") (pin "2") (pinfunction "2_2") (pintype "passive"))
      (node (ref "C32") (pin "2") (pinfunction "2_2") (pintype "passive"))
      (node (ref "C34") (pin "2") (pinfunction "2_2") (pintype "passive"))
      (node (ref "C36") (pin "2") (pinfunction "2_2") (pintype "passive"))
      (node (ref "C38") (pin "2") (pinfunction "2_2") (pintype "passive"))
      (node (ref "C4") (pin "+") (pinfunction "+_+") (pintype "passive"))
      (node (ref "C40") (pin "2") (pinfunction "2_2") (pintype "passive"))
      (node (ref "C42") (pin "2") (pinfunction "2_2") (pintype "passive"))
      (node (ref "C44") (pin "2") (pinfunction "2_2") (pintype "passive"))
      (node (ref "C46") (pin "2") (pinfunction "2_2") (pintype "passive"))
      (node (ref "C48") (pin "2") (pinfunction "2_2") (pintype "passive"))
      (node (ref "C50") (pin "2") (pinfunction "2_2") (pintype "passive"))
      (node (ref "C56") (pin "2") (pinfunction "2_2") (pintype "passive"))
      (node (ref "C58") (pin "2") (pinfunction "2_2") (pintype "passive"))
      (node (ref "C60") (pin "2") (pinfunction "2_2") (pintype "passive"))
      (node (ref "C62") (pin "2") (pinfunction "2_2") (pintype "passive"))
      (node (ref "C64") (pin "2") (pinfunction "2_2") (pintype "passive"))
      (node (ref "C66") (pin "2") (pinfunction "2_2") (pintype "passive"))
      (node (ref "C72") (pin "2") (pinfunction "2_2") (pintype "passive"))
      (node (ref "C74") (pin "2") (pinfunction "2_2") (pintype "passive"))
      (node (ref "C76") (pin "2") (pinfunction "2_2") (pintype "passive"))
      (node (ref "C78") (pin "2") (pinfunction "2_2") (pintype "passive"))
      (node (ref "C80") (pin "2") (pinfunction "2_2") (pintype "passive"))
      (node (ref "C86") (pin "2") (pinfunction "2_2") (pintype "passive"))
      (node (ref "C87") (pin "2") (pinfunction "2_2") (pintype "passive"))
      (node (ref "C88") (pin "2") (pinfunction "2_2") (pintype "passive"))
      (node (ref "C94") (pin "2") (pinfunction "2_2") (pintype "passive"))
      (node (ref "C96") (pin "2") (pinfunction "2_2") (pintype "passive"))
      (node (ref "D3") (pin "A") (pinfunction "A_A") (pintype "passive"))
      (node (ref "D4") (pin "C") (pinfunction "C_C") (pintype "passive"))
      (node (ref "IC3") (pin "4") (pinfunction "VOUT_4") (pintype "output"))
      (node (ref "R9") (pin "2") (pinfunction "2_2") (pintype "passive"))
      (node (ref "S10") (pin "1") (pinfunction "CCW_1") (pintype "bidirectional"))
      (node (ref "S11") (pin "1") (pinfunction "CCW_1") (pintype "bidirectional"))
      (node (ref "S12") (pin "1") (pinfunction "CCW_1") (pintype "bidirectional"))
      (node (ref "S13") (pin "1") (pinfunction "CCW_1") (pintype "bidirectional"))
      (node (ref "S14") (pin "1") (pinfunction "CCW_1") (pintype "bidirectional"))
      (node (ref "S15") (pin "1") (pinfunction "CCW_1") (pintype "bidirectional"))
      (node (ref "S16") (pin "1") (pinfunction "CCW_1") (pintype "bidirectional"))
      (node (ref "S17") (pin "1") (pinfunction "CCW_1") (pintype "bidirectional"))
      (node (ref "S18") (pin "1") (pinfunction "CCW_1") (pintype "bidirectional"))
      (node (ref "S19") (pin "1") (pinfunction "CCW_1") (pintype "bidirectional"))
      (node (ref "S20") (pin "1") (pinfunction "CCW_1") (pintype "bidirectional"))
      (node (ref "S23") (pin "1") (pinfunction "CCW_1") (pintype "bidirectional"))
      (node (ref "S24") (pin "1") (pinfunction "CCW_1") (pintype "bidirectional"))
      (node (ref "S25") (pin "1") (pinfunction "CCW_1") (pintype "bidirectional"))
      (node (ref "S26") (pin "1") (pinfunction "CCW_1") (pintype "bidirectional"))
      (node (ref "S27") (pin "1") (pinfunction "CCW_1") (pintype "bidirectional"))
      (node (ref "S28") (pin "1") (pinfunction "CCW_1") (pintype "bidirectional"))
      (node (ref "S3") (pin "1") (pinfunction "CCW_1") (pintype "bidirectional"))
      (node (ref "S31") (pin "1") (pinfunction "CCW_1") (pintype "bidirectional"))
      (node (ref "S32") (pin "1") (pinfunction "CCW_1") (pintype "bidirectional"))
      (node (ref "S33") (pin "1") (pinfunction "CCW_1") (pintype "bidirectional"))
      (node (ref "S34") (pin "1") (pinfunction "CCW_1") (pintype "bidirectional"))
      (node (ref "S35") (pin "1") (pinfunction "CCW_1") (pintype "bidirectional"))
      (node (ref "S36") (pin "1") (pinfunction "CCW_1") (pintype "bidirectional"))
      (node (ref "S39") (pin "1") (pinfunction "CCW_1") (pintype "bidirectional"))
      (node (ref "S4") (pin "1") (pinfunction "CCW_1") (pintype "bidirectional"))
      (node (ref "S40") (pin "1") (pinfunction "CCW_1") (pintype "bidirectional"))
      (node (ref "S5") (pin "1") (pinfunction "CCW_1") (pintype "bidirectional"))
      (node (ref "S6") (pin "1") (pinfunction "CCW_1") (pintype "bidirectional"))
      (node (ref "S7") (pin "1") (pinfunction "CCW_1") (pintype "bidirectional"))
      (node (ref "S8") (pin "1") (pinfunction "CCW_1") (pintype "bidirectional"))
      (node (ref "S9") (pin "1") (pinfunction "CCW_1") (pintype "bidirectional"))
      (node (ref "U11") (pin "7") (pinfunction "V+_7") (pintype "power_in"))
      (node (ref "U13") (pin "7") (pinfunction "V+_7") (pintype "power_in"))
      (node (ref "U15") (pin "7") (pinfunction "V+_7") (pintype "power_in"))
      (node (ref "U17") (pin "7") (pinfunction "V+_7") (pintype "power_in"))
      (node (ref "U19") (pin "7") (pinfunction "V+_7") (pintype "power_in"))
      (node (ref "U21") (pin "7") (pinfunction "V+_7") (pintype "power_in"))
      (node (ref "U25") (pin "7") (pinfunction "V+_7") (pintype "power_in"))
      (node (ref "U27") (pin "7") (pinfunction "V+_7") (pintype "power_in"))
      (node (ref "U29") (pin "7") (pinfunction "V+_7") (pintype "power_in"))
      (node (ref "U33") (pin "7") (pinfunction "V+_7") (pintype "power_in"))
      (node (ref "U35") (pin "7") (pinfunction "V+_7") (pintype "power_in"))
      (node (ref "U37") (pin "7") (pinfunction "V+_7") (pintype "power_in"))
      (node (ref "U38") (pin "2") (pinfunction "SOURCE_2") (pintype "passive"))
      (node (ref "U40") (pin "7") (pinfunction "V+_7") (pintype "power_in"))
      (node (ref "U44") (pin "7") (pinfunction "V+_7") (pintype "power_in"))
      (node (ref "U5") (pin "7") (pinfunction "V+_7") (pintype "power_in"))
      (node (ref "U7") (pin "7") (pinfunction "V+_7") (pintype "power_in"))
      (node (ref "U9") (pin "7") (pinfunction "V+_7") (pintype "power_in"))
    )
    (net (code "2") (name "+3V") (class "Default")
      (node (ref "+3V_TP1") (pin "1") (pinfunction "1_1") (pintype "passive"))
      (node (ref "+3V_TP2") (pin "1") (pinfunction "1_1") (pintype "passive"))
      (node (ref "C11") (pin "+") (pinfunction "+_+") (pintype "passive"))
      (node (ref "C14") (pin "1") (pinfunction "1_1") (pintype "passive"))
      (node (ref "C19") (pin "1") (pinfunction "1_1") (pintype "passive"))
      (node (ref "C21") (pin "1") (pinfunction "1_1") (pintype "passive"))
      (node (ref "C23") (pin "1") (pinfunction "1_1") (pintype "passive"))
      (node (ref "C25") (pin "1") (pinfunction "1_1") (pintype "passive"))
      (node (ref "C27") (pin "1") (pinfunction "1_1") (pintype "passive"))
      (node (ref "C29") (pin "1") (pinfunction "1_1") (pintype "passive"))
      (node (ref "C31") (pin "1") (pinfunction "1_1") (pintype "passive"))
      (node (ref "C33") (pin "1") (pinfunction "1_1") (pintype "passive"))
      (node (ref "C35") (pin "1") (pinfunction "1_1") (pintype "passive"))
      (node (ref "C37") (pin "1") (pinfunction "1_1") (pintype "passive"))
      (node (ref "C39") (pin "1") (pinfunction "1_1") (pintype "passive"))
      (node (ref "C41") (pin "1") (pinfunction "1_1") (pintype "passive"))
      (node (ref "C43") (pin "1") (pinfunction "1_1") (pintype "passive"))
      (node (ref "C45") (pin "1") (pinfunction "1_1") (pintype "passive"))
      (node (ref "C47") (pin "1") (pinfunction "1_1") (pintype "passive"))
      (node (ref "C49") (pin "1") (pinfunction "1_1") (pintype "passive"))
      (node (ref "C51") (pin "1") (pinfunction "1_1") (pintype "passive"))
      (node (ref "C57") (pin "1") (pinfunction "1_1") (pintype "passive"))
      (node (ref "C59") (pin "1") (pinfunction "1_1") (pintype "passive"))
      (node (ref "C61") (pin "1") (pinfunction "1_1") (pintype "passive"))
      (node (ref "C63") (pin "1") (pinfunction "1_1") (pintype "passive"))
      (node (ref "C65") (pin "1") (pinfunction "1_1") (pintype "passive"))
      (node (ref "C67") (pin "1") (pinfunction "1_1") (pintype "passive"))
      (node (ref "C73") (pin "1") (pinfunction "1_1") (pintype "passive"))
      (node (ref "C75") (pin "1") (pinfunction "1_1") (pintype "passive"))
      (node (ref "C77") (pin "1") (pinfunction "1_1") (pintype "passive"))
      (node (ref "C79") (pin "1") (pinfunction "1_1") (pintype "passive"))
      (node (ref "C81") (pin "1") (pinfunction "1_1") (pintype "passive"))
      (node (ref "C82") (pin "2") (pinfunction "2_2") (pintype "passive"))
      (node (ref "C83") (pin "2") (pinfunction "2_2") (pintype "passive"))
      (node (ref "C89") (pin "1") (pinfunction "1_1") (pintype "passive"))
      (node (ref "C95") (pin "1") (pinfunction "1_1") (pintype "passive"))
      (node (ref "C97") (pin "1") (pinfunction "1_1") (pintype "passive"))
      (node (ref "D7") (pin "A") (pinfunction "A_A") (pintype "passive"))
      (node (ref "D8") (pin "C") (pinfunction "C_C") (pintype "passive"))
      (node (ref "IC4") (pin "4") (pinfunction "VOUT_4") (pintype "output"))
      (node (ref "R11") (pin "2") (pinfunction "2_2") (pintype "passive"))
      (node (ref "U10") (pin "7") (pinfunction "V+_7") (pintype "power_in"))
      (node (ref "U12") (pin "7") (pinfunction "V+_7") (pintype "power_in"))
      (node (ref "U14") (pin "7") (pinfunction "V+_7") (pintype "power_in"))
      (node (ref "U16") (pin "7") (pinfunction "V+_7") (pintype "power_in"))
      (node (ref "U18") (pin "7") (pinfunction "V+_7") (pintype "power_in"))
      (node (ref "U20") (pin "7") (pinfunction "V+_7") (pintype "power_in"))
      (node (ref "U22") (pin "7") (pinfunction "V+_7") (pintype "power_in"))
      (node (ref "U26") (pin "7") (pinfunction "V+_7") (pintype "power_in"))
      (node (ref "U28") (pin "7") (pinfunction "V+_7") (pintype "power_in"))
      (node (ref "U30") (pin "7") (pinfunction "V+_7") (pintype "power_in"))
      (node (ref "U34") (pin "7") (pinfunction "V+_7") (pintype "power_in"))
      (node (ref "U36") (pin "7") (pinfunction "V+_7") (pintype "power_in"))
      (node (ref "U39") (pin "7") (pinfunction "V+_7") (pintype "power_in"))
      (node (ref "U41") (pin "7") (pinfunction "V+_7") (pintype "power_in"))
      (node (ref "U45") (pin "7") (pinfunction "V+_7") (pintype "power_in"))
      (node (ref "U6") (pin "7") (pinfunction "V+_7") (pintype "power_in"))
      (node (ref "U8") (pin "7") (pinfunction "V+_7") (pintype "power_in"))
    )
    (net (code "3") (name "-1.5V") (class "Default")
      (node (ref "-1.5V_TP1") (pin "1") (pinfunction "1_1") (pintype "passive"))
      (node (ref "-1.5V_TP2") (pin "1") (pinfunction "1_1") (pintype "passive"))
      (node (ref "C13") (pin "1") (pinfunction "1_1") (pintype "passive"))
      (node (ref "C15") (pin "1") (pinfunction "1_1") (pintype "passive"))
      (node (ref "C2") (pin "1") (pinfunction "1_1") (pintype "passive"))
      (node (ref "C20") (pin "1") (pinfunction "1_1") (pintype "passive"))
      (node (ref "C22") (pin "1") (pinfunction "1_1") (pintype "passive"))
      (node (ref "C24") (pin "1") (pinfunction "1_1") (pintype "passive"))
      (node (ref "C26") (pin "1") (pinfunction "1_1") (pintype "passive"))
      (node (ref "C28") (pin "1") (pinfunction "1_1") (pintype "passive"))
      (node (ref "C30") (pin "1") (pinfunction "1_1") (pintype "passive"))
      (node (ref "C32") (pin "1") (pinfunction "1_1") (pintype "passive"))
      (node (ref "C34") (pin "1") (pinfunction "1_1") (pintype "passive"))
      (node (ref "C36") (pin "1") (pinfunction "1_1") (pintype "passive"))
      (node (ref "C38") (pin "1") (pinfunction "1_1") (pintype "passive"))
      (node (ref "C40") (pin "1") (pinfunction "1_1") (pintype "passive"))
      (node (ref "C42") (pin "1") (pinfunction "1_1") (pintype "passive"))
      (node (ref "C44") (pin "1") (pinfunction "1_1") (pintype "passive"))
      (node (ref "C46") (pin "1") (pinfunction "1_1") (pintype "passive"))
      (node (ref "C48") (pin "1") (pinfunction "1_1") (pintype "passive"))
      (node (ref "C50") (pin "1") (pinfunction "1_1") (pintype "passive"))
      (node (ref "C56") (pin "1") (pinfunction "1_1") (pintype "passive"))
      (node (ref "C58") (pin "1") (pinfunction "1_1") (pintype "passive"))
      (node (ref "C60") (pin "1") (pinfunction "1_1") (pintype "passive"))
      (node (ref "C62") (pin "1") (pinfunction "1_1") (pintype "passive"))
      (node (ref "C64") (pin "1") (pinfunction "1_1") (pintype "passive"))
      (node (ref "C66") (pin "1") (pinfunction "1_1") (pintype "passive"))
      (node (ref "C72") (pin "1") (pinfunction "1_1") (pintype "passive"))
      (node (ref "C74") (pin "1") (pinfunction "1_1") (pintype "passive"))
      (node (ref "C76") (pin "1") (pinfunction "1_1") (pintype "passive"))
      (node (ref "C78") (pin "1") (pinfunction "1_1") (pintype "passive"))
      (node (ref "C80") (pin "1") (pinfunction "1_1") (pintype "passive"))
      (node (ref "C84") (pin "1") (pinfunction "1_1") (pintype "passive"))
      (node (ref "C85") (pin "1") (pinfunction "1_1") (pintype "passive"))
      (node (ref "C88") (pin "1") (pinfunction "1_1") (pintype "passive"))
      (node (ref "C94") (pin "1") (pinfunction "1_1") (pintype "passive"))
      (node (ref "C96") (pin "1") (pinfunction "1_1") (pintype "passive"))
      (node (ref "R151") (pin "2") (pinfunction "2_2") (pintype "passive"))
      (node (ref "S11") (pin "3") (pinfunction "CW_3") (pintype "bidirectional"))
      (node (ref "S13") (pin "3") (pinfunction "CW_3") (pintype "bidirectional"))
      (node (ref "S15") (pin "3") (pinfunction "CW_3") (pintype "bidirectional"))
      (node (ref "S17") (pin "3") (pinfunction "CW_3") (pintype "bidirectional"))
      (node (ref "S19") (pin "3") (pinfunction "CW_3") (pintype "bidirectional"))
      (node (ref "S23") (pin "3") (pinfunction "CW_3") (pintype "bidirectional"))
      (node (ref "S25") (pin "3") (pinfunction "CW_3") (pintype "bidirectional"))
      (node (ref "S27") (pin "3") (pinfunction "CW_3") (pintype "bidirectional"))
      (node (ref "S3") (pin "3") (pinfunction "CW_3") (pintype "bidirectional"))
      (node (ref "S31") (pin "3") (pinfunction "CW_3") (pintype "bidirectional"))
      (node (ref "S33") (pin "3") (pinfunction "CW_3") (pintype "bidirectional"))
      (node (ref "S35") (pin "3") (pinfunction "CW_3") (pintype "bidirectional"))
      (node (ref "S39") (pin "3") (pinfunction "CW_3") (pintype "bidirectional"))
      (node (ref "S5") (pin "3") (pinfunction "CW_3") (pintype "bidirectional"))
      (node (ref "S7") (pin "3") (pinfunction "CW_3") (pintype "bidirectional"))
      (node (ref "S9") (pin "3") (pinfunction "CW_3") (pintype "bidirectional"))
      (node (ref "U11") (pin "4") (pinfunction "V-_4") (pintype "power_in"))
      (node (ref "U13") (pin "4") (pinfunction "V-_4") (pintype "power_in"))
      (node (ref "U15") (pin "4") (pinfunction "V-_4") (pintype "power_in"))
      (node (ref "U17") (pin "4") (pinfunction "V-_4") (pintype "power_in"))
      (node (ref "U19") (pin "4") (pinfunction "V-_4") (pintype "power_in"))
      (node (ref "U2") (pin "3") (pinfunction "VOUT_3") (pintype "power_in"))
      (node (ref "U21") (pin "4") (pinfunction "V-_4") (pintype "power_in"))
      (node (ref "U25") (pin "4") (pinfunction "V-_4") (pintype "power_in"))
      (node (ref "U27") (pin "4") (pinfunction "V-_4") (pintype "power_in"))
      (node (ref "U29") (pin "4") (pinfunction "V-_4") (pintype "power_in"))
      (node (ref "U33") (pin "4") (pinfunction "V-_4") (pintype "power_in"))
      (node (ref "U35") (pin "4") (pinfunction "V-_4") (pintype "power_in"))
      (node (ref "U37") (pin "4") (pinfunction "V-_4") (pintype "power_in"))
      (node (ref "U40") (pin "4") (pinfunction "V-_4") (pintype "power_in"))
      (node (ref "U40") (pin "8") (pinfunction "SHDN_8") (pintype "passive"))
      (node (ref "U44") (pin "4") (pinfunction "V-_4") (pintype "power_in"))
      (node (ref "U5") (pin "4") (pinfunction "V-_4") (pintype "power_in"))
      (node (ref "U7") (pin "4") (pinfunction "V-_4") (pintype "power_in"))
      (node (ref "U9") (pin "4") (pinfunction "V-_4") (pintype "power_in"))
    )
    (net (code "4") (name "DIR_GATE") (class "Default")
      (node (ref "GATE_TP1") (pin "1") (pinfunction "1_1") (pintype "passive"))
      (node (ref "JP_GATE10") (pin "1") (pinfunction "1_1") (pintype "passive"))
      (node (ref "JP_GATE12") (pin "1") (pinfunction "1_1") (pintype "passive"))
      (node (ref "JP_GATE13") (pin "1") (pinfunction "1_1") (pintype "passive"))
      (node (ref "JP_GATE14") (pin "1") (pinfunction "1_1") (pintype "passive"))
      (node (ref "JP_GATE16") (pin "1") (pinfunction "1_1") (pintype "passive"))
      (node (ref "JP_GATE17") (pin "1") (pinfunction "1_1") (pintype "passive"))
      (node (ref "JP_GATE18") (pin "1") (pinfunction "1_1") (pintype "passive"))
      (node (ref "JP_GATE2") (pin "1") (pinfunction "1_1") (pintype "passive"))
      (node (ref "JP_GATE20") (pin "1") (pinfunction "1_1") (pintype "passive"))
      (node (ref "JP_GATE3") (pin "1") (pinfunction "1_1") (pintype "passive"))
      (node (ref "JP_GATE4") (pin "1") (pinfunction "1_1") (pintype "passive"))
      (node (ref "JP_GATE5") (pin "1") (pinfunction "1_1") (pintype "passive"))
      (node (ref "JP_GATE6") (pin "1") (pinfunction "1_1") (pintype "passive"))
      (node (ref "JP_GATE7") (pin "1") (pinfunction "1_1") (pintype "passive"))
      (node (ref "JP_GATE8") (pin "1") (pinfunction "1_1") (pintype "passive"))
      (node (ref "JP_GATE9") (pin "1") (pinfunction "1_1") (pintype "passive"))
      (node (ref "R113") (pin "2") (pinfunction "2_2") (pintype "passive"))
      (node (ref "R122") (pin "2") (pinfunction "2_2") (pintype "passive"))
      (node (ref "R131") (pin "2") (pinfunction "2_2") (pintype "passive"))
      (node (ref "R149") (pin "2") (pinfunction "2_2") (pintype "passive"))
      (node (ref "R165") (pin "1") (pinfunction "1_1") (pintype "passive"))
      (node (ref "R167") (pin "2") (pinfunction "2_2") (pintype "passive"))
      (node (ref "R176") (pin "2") (pinfunction "2_2") (pintype "passive"))
      (node (ref "R194") (pin "2") (pinfunction "2_2") (pintype "passive"))
      (node (ref "R23") (pin "2") (pinfunction "2_2") (pintype "passive"))
      (node (ref "R32") (pin "2") (pinfunction "2_2") (pintype "passive"))
      (node (ref "R41") (pin "2") (pinfunction "2_2") (pintype "passive"))
      (node (ref "R50") (pin "2") (pinfunction "2_2") (pintype "passive"))
      (node (ref "R59") (pin "2") (pinfunction "2_2") (pintype "passive"))
      (node (ref "R68") (pin "2") (pinfunction "2_2") (pintype "passive"))
      (node (ref "R77") (pin "2") (pinfunction "2_2") (pintype "passive"))
      (node (ref "R86") (pin "2") (pinfunction "2_2") (pintype "passive"))
      (node (ref "R95") (pin "2") (pinfunction "2_2") (pintype "passive"))
      (node (ref "U40") (pin "6") (pinfunction "OUT_6") (pintype "output"))
    )
    (net (code "5") (name "F1") (class "Default")
      (node (ref "FROM_FPGA_2") (pin "1") (pinfunction "1_1") (pintype "passive"))
      (node (ref "J3") (pin "1") (pinfunction "1_1") (pintype "bidirectional"))
      (node (ref "R16") (pin "1") (pinfunction "1_1") (pintype "passive"))
    )
    (net (code "6") (name "F2") (class "Default")
      (node (ref "FROM_FPGA_4") (pin "1") (pinfunction "1_1") (pintype "passive"))
      (node (ref "J3") (pin "2") (pinfunction "2_2") (pintype "bidirectional"))
      (node (ref "R34") (pin "1") (pinfunction "1_1") (pintype "passive"))
    )
    (net (code "7") (name "F3") (class "Default")
      (node (ref "FROM_FPGA_3") (pin "1") (pinfunction "1_1") (pintype "passive"))
      (node (ref "J3") (pin "3") (pinfunction "3_3") (pintype "bidirectional"))
      (node (ref "R25") (pin "1") (pinfunction "1_1") (pintype "passive"))
    )
    (net (code "8") (name "F4") (class "Default")
      (node (ref "FROM_FPGA_6") (pin "1") (pinfunction "1_1") (pintype "passive"))
      (node (ref "J3") (pin "4") (pinfunction "4_4") (pintype "bidirectional"))
      (node (ref "R52") (pin "1") (pinfunction "1_1") (pintype "passive"))
    )
    (net (code "9") (name "F5") (class "Default")
      (node (ref "FROM_FPGA_8") (pin "1") (pinfunction "1_1") (pintype "passive"))
      (node (ref "J3") (pin "5") (pinfunction "5_5") (pintype "bidirectional"))
      (node (ref "R70") (pin "1") (pinfunction "1_1") (pintype "passive"))
    )
    (net (code "10") (name "F6") (class "Default")
      (node (ref "FROM_FPGA_10") (pin "1") (pinfunction "1_1") (pintype "passive"))
      (node (ref "J3") (pin "6") (pinfunction "6_6") (pintype "bidirectional"))
      (node (ref "R88") (pin "1") (pinfunction "1_1") (pintype "passive"))
    )
    (net (code "11") (name "F7") (class "Default")
      (node (ref "FROM_FPGA_12") (pin "1") (pinfunction "1_1") (pintype "passive"))
      (node (ref "J3") (pin "7") (pinfunction "7_7") (pintype "bidirectional"))
      (node (ref "R106") (pin "1") (pinfunction "1_1") (pintype "passive"))
    )
    (net (code "12") (name "F8") (class "Default")
      (node (ref "FROM_FPGA_14") (pin "1") (pinfunction "1_1") (pintype "passive"))
      (node (ref "J3") (pin "8") (pinfunction "8_8") (pintype "bidirectional"))
      (node (ref "R124") (pin "1") (pinfunction "1_1") (pintype "passive"))
    )
    (net (code "13") (name "F9") (class "Default")
      (node (ref "FROM_FPGA_16") (pin "1") (pinfunction "1_1") (pintype "passive"))
      (node (ref "J3") (pin "9") (pinfunction "9_9") (pintype "bidirectional"))
      (node (ref "R142") (pin "1") (pinfunction "1_1") (pintype "passive"))
    )
    (net (code "14") (name "F10") (class "Default")
      (node (ref "FROM_FPGA_18") (pin "1") (pinfunction "1_1") (pintype "passive"))
      (node (ref "J3") (pin "10") (pinfunction "10_10") (pintype "bidirectional"))
      (node (ref "R169") (pin "1") (pinfunction "1_1") (pintype "passive"))
    )
    (net (code "15") (name "F11") (class "Default")
      (node (ref "FROM_FPGA_5") (pin "1") (pinfunction "1_1") (pintype "passive"))
      (node (ref "J3") (pin "11") (pinfunction "11_11") (pintype "bidirectional"))
      (node (ref "R43") (pin "1") (pinfunction "1_1") (pintype "passive"))
    )
    (net (code "16") (name "F12") (class "Default")
      (node (ref "FROM_FPGA_9") (pin "1") (pinfunction "1_1") (pintype "passive"))
      (node (ref "J3") (pin "12") (pinfunction "12_12") (pintype "bidirectional"))
      (node (ref "R79") (pin "1") (pinfunction "1_1") (pintype "passive"))
    )
    (net (code "17") (name "F13") (class "Default")
      (node (ref "FROM_FPGA_7") (pin "1") (pinfunction "1_1") (pintype "passive"))
      (node (ref "J3") (pin "13") (pinfunction "13_13") (pintype "bidirectional"))
      (node (ref "R61") (pin "1") (pinfunction "1_1") (pintype "passive"))
    )
    (net (code "18") (name "F14") (class "Default")
      (node (ref "FROM_FPGA_13") (pin "1") (pinfunction "1_1") (pintype "passive"))
      (node (ref "J3") (pin "14") (pinfunction "14_14") (pintype "bidirectional"))
      (node (ref "R115") (pin "1") (pinfunction "1_1") (pintype "passive"))
    )
    (net (code "19") (name "F15") (class "Default")
      (node (ref "FROM_FPGA_17") (pin "1") (pinfunction "1_1") (pintype "passive"))
      (node (ref "J3") (pin "15") (pinfunction "15_15") (pintype "bidirectional"))
      (node (ref "R152") (pin "1") (pinfunction "1_1") (pintype "passive"))
    )
    (net (code "20") (name "F16") (class "Default")
      (node (ref "FROM_FPGA_20") (pin "1") (pinfunction "1_1") (pintype "passive"))
      (node (ref "J3") (pin "16") (pinfunction "16_16") (pintype "bidirectional"))
      (node (ref "R187") (pin "1") (pinfunction "1_1") (pintype "passive"))
    )
    (net (code "21") (name "GND") (class "Default")
      (node (ref "C1") (pin "2") (pinfunction "2_2") (pintype "passive"))
      (node (ref "C10") (pin "2") (pinfunction "2_2") (pintype "passive"))
      (node (ref "C11") (pin "-") (pinfunction "-_-") (pintype "passive"))
      (node (ref "C12") (pin "-") (pinfunction "-_-") (pintype "passive"))
      (node (ref "C14") (pin "2") (pinfunction "2_2") (pintype "passive"))
      (node (ref "C16") (pin "+") (pinfunction "+_+") (pintype "passive"))
      (node (ref "C17") (pin "+") (pinfunction "+_+") (pintype "passive"))
      (node (ref "C18") (pin "-") (pinfunction "-_-") (pintype "passive"))
      (node (ref "C19") (pin "2") (pinfunction "2_2") (pintype "passive"))
      (node (ref "C2") (pin "2") (pinfunction "2_2") (pintype "passive"))
      (node (ref "C21") (pin "2") (pinfunction "2_2") (pintype "passive"))
      (node (ref "C23") (pin "2") (pinfunction "2_2") (pintype "passive"))
      (node (ref "C25") (pin "2") (pinfunction "2_2") (pintype "passive"))
      (node (ref "C27") (pin "2") (pinfunction "2_2") (pintype "passive"))
      (node (ref "C29") (pin "2") (pinfunction "2_2") (pintype "passive"))
      (node (ref "C3") (pin "2") (pinfunction "2_2") (pintype "passive"))
      (node (ref "C31") (pin "2") (pinfunction "2_2") (pintype "passive"))
      (node (ref "C33") (pin "2") (pinfunction "2_2") (pintype "passive"))
      (node (ref "C35") (pin "2") (pinfunction "2_2") (pintype "passive"))
      (node (ref "C37") (pin "2") (pinfunction "2_2") (pintype "passive"))
      (node (ref "C39") (pin "2") (pinfunction "2_2") (pintype "passive"))
      (node (ref "C4") (pin "-") (pinfunction "-_-") (pintype "passive"))
      (node (ref "C41") (pin "2") (pinfunction "2_2") (pintype "passive"))
      (node (ref "C43") (pin "2") (pinfunction "2_2") (pintype "passive"))
      (node (ref "C45") (pin "2") (pinfunction "2_2") (pintype "passive"))
      (node (ref "C47") (pin "2") (pinfunction "2_2") (pintype "passive"))
      (node (ref "C49") (pin "2") (pinfunction "2_2") (pintype "passive"))
      (node (ref "C5") (pin "-") (pinfunction "-_-") (pintype "passive"))
      (node (ref "C51") (pin "2") (pinfunction "2_2") (pintype "passive"))
      (node (ref "C57") (pin "2") (pinfunction "2_2") (pintype "passive"))
      (node (ref "C59") (pin "2") (pinfunction "2_2") (pintype "passive"))
      (node (ref "C61") (pin "2") (pinfunction "2_2") (pintype "passive"))
      (node (ref "C63") (pin "2") (pinfunction "2_2") (pintype "passive"))
      (node (ref "C65") (pin "2") (pinfunction "2_2") (pintype "passive"))
      (node (ref "C67") (pin "2") (pinfunction "2_2") (pintype "passive"))
      (node (ref "C73") (pin "2") (pinfunction "2_2") (pintype "passive"))
      (node (ref "C75") (pin "2") (pinfunction "2_2") (pintype "passive"))
      (node (ref "C77") (pin "2") (pinfunction "2_2") (pintype "passive"))
      (node (ref "C79") (pin "2") (pinfunction "2_2") (pintype "passive"))
      (node (ref "C81") (pin "2") (pinfunction "2_2") (pintype "passive"))
      (node (ref "C82") (pin "1") (pinfunction "1_1") (pintype "passive"))
      (node (ref "C83") (pin "1") (pinfunction "1_1") (pintype "passive"))
      (node (ref "C84") (pin "2") (pinfunction "2_2") (pintype "passive"))
      (node (ref "C85") (pin "2") (pinfunction "2_2") (pintype "passive"))
      (node (ref "C86") (pin "1") (pinfunction "1_1") (pintype "passive"))
      (node (ref "C87") (pin "1") (pinfunction "1_1") (pintype "passive"))
      (node (ref "C89") (pin "2") (pinfunction "2_2") (pintype "passive"))
      (node (ref "C95") (pin "2") (pinfunction "2_2") (pintype "passive"))
      (node (ref "C97") (pin "2") (pinfunction "2_2") (pintype "passive"))
      (node (ref "J1") (pin "25") (pinfunction "25_25") (pintype "bidirectional"))
      (node (ref "J1") (pin "26") (pinfunction "26_26") (pintype "bidirectional"))
      (node (ref "J1") (pin "27") (pinfunction "27_27") (pintype "bidirectional"))
      (node (ref "J1") (pin "28") (pinfunction "28_28") (pintype "bidirectional"))
      (node (ref "J2") (pin "25") (pinfunction "25_25") (pintype "bidirectional"))
      (node (ref "J2") (pin "26") (pinfunction "26_26") (pintype "bidirectional"))
      (node (ref "J2") (pin "27") (pinfunction "27_27") (pintype "bidirectional"))
      (node (ref "J2") (pin "28") (pinfunction "28_28") (pintype "bidirectional"))
      (node (ref "J3") (pin "25") (pinfunction "25_25") (pintype "bidirectional"))
      (node (ref "J3") (pin "26") (pinfunction "26_26") (pintype "bidirectional"))
      (node (ref "J3") (pin "27") (pinfunction "27_27") (pintype "bidirectional"))
      (node (ref "J3") (pin "28") (pinfunction "28_28") (pintype "bidirectional"))
      (node (ref "J5") (pin "1") (pinfunction "1_1") (pintype "bidirectional"))
      (node (ref "J6") (pin "3") (pinfunction "3_3") (pintype "bidirectional"))
      (node (ref "R10") (pin "1") (pinfunction "1_1") (pintype "passive"))
      (node (ref "R108") (pin "2") (pinfunction "2_2") (pintype "passive"))
      (node (ref "R112") (pin "2") (pinfunction "2_2") (pintype "passive"))
      (node (ref "R117") (pin "2") (pinfunction "2_2") (pintype "passive"))
      (node (ref "R12") (pin "1") (pinfunction "1_1") (pintype "passive"))
      (node (ref "R121") (pin "2") (pinfunction "2_2") (pintype "passive"))
      (node (ref "R126") (pin "2") (pinfunction "2_2") (pintype "passive"))
      (node (ref "R130") (pin "2") (pinfunction "2_2") (pintype "passive"))
      (node (ref "R144") (pin "2") (pinfunction "2_2") (pintype "passive"))
      (node (ref "R148") (pin "2") (pinfunction "2_2") (pintype "passive"))
      (node (ref "R154") (pin "2") (pinfunction "2_2") (pintype "passive"))
      (node (ref "R158") (pin "2") (pinfunction "2_2") (pintype "passive"))
      (node (ref "R161") (pin "1") (pinfunction "1_1") (pintype "passive"))
      (node (ref "R162") (pin "2") (pinfunction "2_2") (pintype "passive"))
      (node (ref "R171") (pin "2") (pinfunction "2_2") (pintype "passive"))
      (node (ref "R175") (pin "2") (pinfunction "2_2") (pintype "passive"))
      (node (ref "R18") (pin "2") (pinfunction "2_2") (pintype "passive"))
      (node (ref "R189") (pin "2") (pinfunction "2_2") (pintype "passive"))
      (node (ref "R193") (pin "2") (pinfunction "2_2") (pintype "passive"))
      (node (ref "R2") (pin "1") (pinfunction "1_1") (pintype "passive"))
      (node (ref "R22") (pin "2") (pinfunction "2_2") (pintype "passive"))
      (node (ref "R27") (pin "2") (pinfunction "2_2") (pintype "passive"))
      (node (ref "R31") (pin "2") (pinfunction "2_2") (pintype "passive"))
      (node (ref "R36") (pin "2") (pinfunction "2_2") (pintype "passive"))
      (node (ref "R40") (pin "2") (pinfunction "2_2") (pintype "passive"))
      (node (ref "R45") (pin "2") (pinfunction "2_2") (pintype "passive"))
      (node (ref "R49") (pin "2") (pinfunction "2_2") (pintype "passive"))
      (node (ref "R54") (pin "2") (pinfunction "2_2") (pintype "passive"))
      (node (ref "R58") (pin "2") (pinfunction "2_2") (pintype "passive"))
      (node (ref "R63") (pin "2") (pinfunction "2_2") (pintype "passive"))
      (node (ref "R67") (pin "2") (pinfunction "2_2") (pintype "passive"))
      (node (ref "R72") (pin "2") (pinfunction "2_2") (pintype "passive"))
      (node (ref "R76") (pin "2") (pinfunction "2_2") (pintype "passive"))
      (node (ref "R81") (pin "2") (pinfunction "2_2") (pintype "passive"))
      (node (ref "R85") (pin "2") (pinfunction "2_2") (pintype "passive"))
      (node (ref "R90") (pin "2") (pinfunction "2_2") (pintype "passive"))
      (node (ref "R94") (pin "2") (pinfunction "2_2") (pintype "passive"))
      (node (ref "S10") (pin "3") (pinfunction "CW_3") (pintype "bidirectional"))
      (node (ref "S12") (pin "3") (pinfunction "CW_3") (pintype "bidirectional"))
      (node (ref "S14") (pin "3") (pinfunction "CW_3") (pintype "bidirectional"))
      (node (ref "S16") (pin "3") (pinfunction "CW_3") (pintype "bidirectional"))
      (node (ref "S18") (pin "3") (pinfunction "CW_3") (pintype "bidirectional"))
      (node (ref "S20") (pin "3") (pinfunction "CW_3") (pintype "bidirectional"))
      (node (ref "S24") (pin "3") (pinfunction "CW_3") (pintype "bidirectional"))
      (node (ref "S26") (pin "3") (pinfunction "CW_3") (pintype "bidirectional"))
      (node (ref "S28") (pin "3") (pinfunction "CW_3") (pintype "bidirectional"))
      (node (ref "S32") (pin "3") (pinfunction "CW_3") (pintype "bidirectional"))
      (node (ref "S34") (pin "3") (pinfunction "CW_3") (pintype "bidirectional"))
      (node (ref "S36") (pin "3") (pinfunction "CW_3") (pintype "bidirectional"))
      (node (ref "S4") (pin "3") (pinfunction "CW_3") (pintype "bidirectional"))
      (node (ref "S40") (pin "3") (pinfunction "CW_3") (pintype "bidirectional"))
      (node (ref "S6") (pin "3") (pinfunction "CW_3") (pintype "bidirectional"))
      (node (ref "S8") (pin "3") (pinfunction "CW_3") (pintype "bidirectional"))
      (node (ref "U10") (pin "4") (pinfunction "V-_4") (pintype "power_in"))
      (node (ref "U12") (pin "4") (pinfunction "V-_4") (pintype "power_in"))
      (node (ref "U14") (pin "4") (pinfunction "V-_4") (pintype "power_in"))
      (node (ref "U16") (pin "4") (pinfunction "V-_4") (pintype "power_in"))
      (node (ref "U18") (pin "4") (pinfunction "V-_4") (pintype "power_in"))
      (node (ref "U20") (pin "4") (pinfunction "V-_4") (pintype "power_in"))
      (node (ref "U22") (pin "4") (pinfunction "V-_4") (pintype "power_in"))
      (node (ref "U26") (pin "4") (pinfunction "V-_4") (pintype "power_in"))
      (node (ref "U28") (pin "4") (pinfunction "V-_4") (pintype "power_in"))
      (node (ref "U30") (pin "4") (pinfunction "V-_4") (pintype "power_in"))
      (node (ref "U34") (pin "4") (pinfunction "V-_4") (pintype "power_in"))
      (node (ref "U36") (pin "4") (pinfunction "V-_4") (pintype "power_in"))
      (node (ref "U39") (pin "4") (pinfunction "V-_4") (pintype "power_in"))
      (node (ref "U39") (pin "8") (pinfunction "SHDN_8") (pintype "passive"))
      (node (ref "U41") (pin "4") (pinfunction "V-_4") (pintype "power_in"))
      (node (ref "U45") (pin "4") (pinfunction "V-_4") (pintype "power_in"))
      (node (ref "U6") (pin "4") (pinfunction "V-_4") (pintype "power_in"))
      (node (ref "U8") (pin "4") (pinfunction "V-_4") (pintype "power_in"))
      (node (ref "X2") (pin "2") (pinfunction "S_2") (pintype "passive"))
      (node (ref "X2") (pin "3") (pinfunction "S_3") (pintype "passive"))
    )
    (net (code "22") (name "INV_DIR_DRAIN") (class "Default")
      (node (ref "DRAIN_TP1") (pin "1") (pinfunction "1_1") (pintype "passive"))
      (node (ref "JP_DRAIN1") (pin "1") (pinfunction "1_1") (pintype "passive"))
      (node (ref "JP_DRAIN11") (pin "1") (pinfunction "1_1") (pintype "passive"))
      (node (ref "JP_DRAIN12") (pin "1") (pinfunction "1_1") (pintype "passive"))
      (node (ref "JP_DRAIN13") (pin "1") (pinfunction "1_1") (pintype "passive"))
      (node (ref "JP_DRAIN15") (pin "1") (pinfunction "1_1") (pintype "passive"))
      (node (ref "JP_DRAIN16") (pin "1") (pinfunction "1_1") (pintype "passive"))
      (node (ref "JP_DRAIN17") (pin "1") (pinfunction "1_1") (pintype "passive"))
      (node (ref "JP_DRAIN19") (pin "1") (pinfunction "1_1") (pintype "passive"))
      (node (ref "JP_DRAIN2") (pin "1") (pinfunction "1_1") (pintype "passive"))
      (node (ref "JP_DRAIN3") (pin "1") (pinfunction "1_1") (pintype "passive"))
      (node (ref "JP_DRAIN4") (pin "1") (pinfunction "1_1") (pintype "passive"))
      (node (ref "JP_DRAIN5") (pin "1") (pinfunction "1_1") (pintype "passive"))
      (node (ref "JP_DRAIN6") (pin "1") (pinfunction "1_1") (pintype "passive"))
      (node (ref "JP_DRAIN7") (pin "1") (pinfunction "1_1") (pintype "passive"))
      (node (ref "JP_DRAIN8") (pin "1") (pinfunction "1_1") (pintype "passive"))
      (node (ref "JP_DRAIN9") (pin "1") (pinfunction "1_1") (pintype "passive"))
      (node (ref "R162") (pin "1") (pinfunction "1_1") (pintype "passive"))
      (node (ref "U10") (pin "8") (pinfunction "SHDN_8") (pintype "passive"))
      (node (ref "U12") (pin "8") (pinfunction "SHDN_8") (pintype "passive"))
      (node (ref "U14") (pin "8") (pinfunction "SHDN_8") (pintype "passive"))
      (node (ref "U16") (pin "8") (pinfunction "SHDN_8") (pintype "passive"))
      (node (ref "U18") (pin "8") (pinfunction "SHDN_8") (pintype "passive"))
      (node (ref "U20") (pin "8") (pinfunction "SHDN_8") (pintype "passive"))
      (node (ref "U22") (pin "8") (pinfunction "SHDN_8") (pintype "passive"))
      (node (ref "U26") (pin "8") (pinfunction "SHDN_8") (pintype "passive"))
      (node (ref "U28") (pin "8") (pinfunction "SHDN_8") (pintype "passive"))
      (node (ref "U30") (pin "8") (pinfunction "SHDN_8") (pintype "passive"))
      (node (ref "U34") (pin "8") (pinfunction "SHDN_8") (pintype "passive"))
      (node (ref "U36") (pin "8") (pinfunction "SHDN_8") (pintype "passive"))
      (node (ref "U38") (pin "3") (pinfunction "DRAIN_3") (pintype "passive"))
      (node (ref "U41") (pin "8") (pinfunction "SHDN_8") (pintype "passive"))
      (node (ref "U45") (pin "8") (pinfunction "SHDN_8") (pintype "passive"))
      (node (ref "U6") (pin "8") (pinfunction "SHDN_8") (pintype "passive"))
      (node (ref "U8") (pin "8") (pinfunction "SHDN_8") (pintype "passive"))
    )
    (net (code "23") (name "M1") (class "Default")
      (node (ref "J1") (pin "1") (pinfunction "1_1") (pintype "bidirectional"))
      (node (ref "JP_MIPS2") (pin "1") (pinfunction "1_1") (pintype "passive"))
      (node (ref "R20") (pin "2") (pinfunction "2_2") (pintype "passive"))
      (node (ref "R21") (pin "1") (pinfunction "1_1") (pintype "passive"))
      (node (ref "R22") (pin "1") (pinfunction "1_1") (pintype "passive"))
    )
    (net (code "24") (name "M2") (class "Default")
      (node (ref "J1") (pin "2") (pinfunction "2_2") (pintype "bidirectional"))
      (node (ref "JP_MIPS4") (pin "1") (pinfunction "1_1") (pintype "passive"))
      (node (ref "R38") (pin "2") (pinfunction "2_2") (pintype "passive"))
      (node (ref "R39") (pin "1") (pinfunction "1_1") (pintype "passive"))
      (node (ref "R40") (pin "1") (pinfunction "1_1") (pintype "passive"))
    )
    (net (code "25") (name "M3") (class "Default")
      (node (ref "J1") (pin "3") (pinfunction "3_3") (pintype "bidirectional"))
      (node (ref "JP_MIPS3") (pin "1") (pinfunction "1_1") (pintype "passive"))
      (node (ref "R29") (pin "2") (pinfunction "2_2") (pintype "passive"))
      (node (ref "R30") (pin "1") (pinfunction "1_1") (pintype "passive"))
      (node (ref "R31") (pin "1") (pinfunction "1_1") (pintype "passive"))
    )
    (net (code "26") (name "M4") (class "Default")
      (node (ref "J1") (pin "4") (pinfunction "4_4") (pintype "bidirectional"))
      (node (ref "JP_MIPS6") (pin "1") (pinfunction "1_1") (pintype "passive"))
      (node (ref "R56") (pin "2") (pinfunction "2_2") (pintype "passive"))
      (node (ref "R57") (pin "1") (pinfunction "1_1") (pintype "passive"))
      (node (ref "R58") (pin "1") (pinfunction "1_1") (pintype "passive"))
    )
    (net (code "27") (name "M5") (class "Default")
      (node (ref "J1") (pin "5") (pinfunction "5_5") (pintype "bidirectional"))
      (node (ref "JP_MIPS8") (pin "1") (pinfunction "1_1") (pintype "passive"))
      (node (ref "R74") (pin "2") (pinfunction "2_2") (pintype "passive"))
      (node (ref "R75") (pin "1") (pinfunction "1_1") (pintype "passive"))
      (node (ref "R76") (pin "1") (pinfunction "1_1") (pintype "passive"))
    )
    (net (code "28") (name "M6") (class "Default")
      (node (ref "J1") (pin "6") (pinfunction "6_6") (pintype "bidirectional"))
      (node (ref "JP_MIPS10") (pin "1") (pinfunction "1_1") (pintype "passive"))
      (node (ref "R92") (pin "2") (pinfunction "2_2") (pintype "passive"))
      (node (ref "R93") (pin "1") (pinfunction "1_1") (pintype "passive"))
      (node (ref "R94") (pin "1") (pinfunction "1_1") (pintype "passive"))
    )
    (net (code "29") (name "M7") (class "Default")
      (node (ref "J1") (pin "7") (pinfunction "7_7") (pintype "bidirectional"))
      (node (ref "JP_MIPS12") (pin "1") (pinfunction "1_1") (pintype "passive"))
      (node (ref "R110") (pin "2") (pinfunction "2_2") (pintype "passive"))
      (node (ref "R111") (pin "1") (pinfunction "1_1") (pintype "passive"))
      (node (ref "R112") (pin "1") (pinfunction "1_1") (pintype "passive"))
    )
    (net (code "30") (name "M8") (class "Default")
      (node (ref "J1") (pin "8") (pinfunction "8_8") (pintype "bidirectional"))
      (node (ref "JP_MIPS14") (pin "1") (pinfunction "1_1") (pintype "passive"))
      (node (ref "R128") (pin "2") (pinfunction "2_2") (pintype "passive"))
      (node (ref "R129") (pin "1") (pinfunction "1_1") (pintype "passive"))
      (node (ref "R130") (pin "1") (pinfunction "1_1") (pintype "passive"))
    )
    (net (code "31") (name "M9") (class "Default")
      (node (ref "J1") (pin "9") (pinfunction "9_9") (pintype "bidirectional"))
      (node (ref "JP_MIPS16") (pin "1") (pinfunction "1_1") (pintype "passive"))
      (node (ref "R146") (pin "2") (pinfunction "2_2") (pintype "passive"))
      (node (ref "R147") (pin "1") (pinfunction "1_1") (pintype "passive"))
      (node (ref "R148") (pin "1") (pinfunction "1_1") (pintype "passive"))
    )
    (net (code "32") (name "M10") (class "Default")
      (node (ref "J1") (pin "10") (pinfunction "10_10") (pintype "bidirectional"))
      (node (ref "JP_MIPS18") (pin "1") (pinfunction "1_1") (pintype "passive"))
      (node (ref "R173") (pin "2") (pinfunction "2_2") (pintype "passive"))
      (node (ref "R174") (pin "1") (pinfunction "1_1") (pintype "passive"))
      (node (ref "R175") (pin "1") (pinfunction "1_1") (pintype "passive"))
    )
    (net (code "33") (name "M11") (class "Default")
      (node (ref "J1") (pin "11") (pinfunction "11_11") (pintype "bidirectional"))
      (node (ref "JP_MIPS5") (pin "1") (pinfunction "1_1") (pintype "passive"))
      (node (ref "R47") (pin "2") (pinfunction "2_2") (pintype "passive"))
      (node (ref "R48") (pin "1") (pinfunction "1_1") (pintype "passive"))
      (node (ref "R49") (pin "1") (pinfunction "1_1") (pintype "passive"))
    )
    (net (code "34") (name "M12") (class "Default")
      (node (ref "J1") (pin "12") (pinfunction "12_12") (pintype "bidirectional"))
      (node (ref "JP_MIPS9") (pin "1") (pinfunction "1_1") (pintype "passive"))
      (node (ref "R83") (pin "2") (pinfunction "2_2") (pintype "passive"))
      (node (ref "R84") (pin "1") (pinfunction "1_1") (pintype "passive"))
      (node (ref "R85") (pin "1") (pinfunction "1_1") (pintype "passive"))
    )
    (net (code "35") (name "M13") (class "Default")
      (node (ref "J1") (pin "13") (pinfunction "13_13") (pintype "bidirectional"))
      (node (ref "JP_MIPS7") (pin "1") (pinfunction "1_1") (pintype "passive"))
      (node (ref "R65") (pin "2") (pinfunction "2_2") (pintype "passive"))
      (node (ref "R66") (pin "1") (pinfunction "1_1") (pintype "passive"))
      (node (ref "R67") (pin "1") (pinfunction "1_1") (pintype "passive"))
    )
    (net (code "36") (name "M14") (class "Default")
      (node (ref "J1") (pin "14") (pinfunction "14_14") (pintype "bidirectional"))
      (node (ref "JP_MIPS13") (pin "1") (pinfunction "1_1") (pintype "passive"))
      (node (ref "R119") (pin "2") (pinfunction "2_2") (pintype "passive"))
      (node (ref "R120") (pin "1") (pinfunction "1_1") (pintype "passive"))
      (node (ref "R121") (pin "1") (pinfunction "1_1") (pintype "passive"))
    )
    (net (code "37") (name "M15") (class "Default")
      (node (ref "J1") (pin "15") (pinfunction "15_15") (pintype "bidirectional"))
      (node (ref "JP_MIPS17") (pin "1") (pinfunction "1_1") (pintype "passive"))
      (node (ref "R156") (pin "2") (pinfunction "2_2") (pintype "passive"))
      (node (ref "R157") (pin "1") (pinfunction "1_1") (pintype "passive"))
      (node (ref "R158") (pin "1") (pinfunction "1_1") (pintype "passive"))
    )
    (net (code "38") (name "M16") (class "Default")
      (node (ref "J1") (pin "16") (pinfunction "16_16") (pintype "bidirectional"))
      (node (ref "JP_MIPS20") (pin "1") (pinfunction "1_1") (pintype "passive"))
      (node (ref "R191") (pin "2") (pinfunction "2_2") (pintype "passive"))
      (node (ref "R192") (pin "1") (pinfunction "1_1") (pintype "passive"))
      (node (ref "R193") (pin "1") (pinfunction "1_1") (pintype "passive"))
    )
    (net (code "39") (name "M17") (class "Default")
      (node (ref "J1") (pin "17") (pinfunction "17_17") (pintype "bidirectional"))
      (node (ref "J5") (pin "3") (pinfunction "3_3") (pintype "bidirectional"))
      (node (ref "J6") (pin "1") (pinfunction "1_1") (pintype "bidirectional"))
      (node (ref "M17_TP1") (pin "1") (pinfunction "1_1") (pintype "passive"))
    )
    (net (code "40") (name "Net-(IC3-ADJ{slash}GND)") (class "Default")
      (node (ref "C5") (pin "+") (pinfunction "+_+") (pintype "passive"))
      (node (ref "D4") (pin "A") (pinfunction "A_A") (pintype "passive"))
      (node (ref "IC3") (pin "1") (pinfunction "ADJ/GND_1") (pintype "power_in"))
      (node (ref "R10") (pin "2") (pinfunction "2_2") (pintype "passive"))
      (node (ref "R9") (pin "1") (pinfunction "1_1") (pintype "passive"))
    )
    (net (code "41") (name "Net-(IC3-INPUT)") (class "Default")
      (node (ref "+V_IN1") (pin "1") (pinfunction "1_1") (pintype "passive"))
      (node (ref "C10") (pin "1") (pinfunction "1_1") (pintype "passive"))
      (node (ref "C18") (pin "+") (pinfunction "+_+") (pintype "passive"))
      (node (ref "C3") (pin "1") (pinfunction "1_1") (pintype "passive"))
      (node (ref "D3") (pin "C") (pinfunction "C_C") (pintype "passive"))
      (node (ref "D7") (pin "C") (pinfunction "C_C") (pintype "passive"))
      (node (ref "IC3") (pin "3") (pinfunction "INPUT_3") (pintype "input"))
      (node (ref "IC4") (pin "3") (pinfunction "INPUT_3") (pintype "input"))
      (node (ref "U1") (pin "1") (pinfunction "OUT+_1") (pintype "output"))
    )
    (net (code "42") (name "Net-(IC4-ADJ{slash}GND)") (class "Default")
      (node (ref "C12") (pin "+") (pinfunction "+_+") (pintype "passive"))
      (node (ref "D8") (pin "A") (pinfunction "A_A") (pintype "passive"))
      (node (ref "IC4") (pin "1") (pinfunction "ADJ/GND_1") (pintype "power_in"))
      (node (ref "R11") (pin "1") (pinfunction "1_1") (pintype "passive"))
      (node (ref "R12") (pin "2") (pinfunction "2_2") (pintype "passive"))
    )
    (net (code "43") (name "Net-(J5-Pad2)") (class "Default")
      (node (ref "J5") (pin "2") (pinfunction "2_2") (pintype "bidirectional"))
      (node (ref "J5") (pin "4") (pinfunction "4_4") (pintype "bidirectional"))
      (node (ref "R159") (pin "1") (pinfunction "1_1") (pintype "passive"))
      (node (ref "R163") (pin "1") (pinfunction "1_1") (pintype "passive"))
    )
    (net (code "44") (name "Net-(J6-Pad2)") (class "Default")
      (node (ref "J6") (pin "2") (pinfunction "2_2") (pintype "bidirectional"))
      (node (ref "J6") (pin "4") (pinfunction "4_4") (pintype "bidirectional"))
      (node (ref "R160") (pin "1") (pinfunction "1_1") (pintype "passive"))
      (node (ref "R164") (pin "1") (pinfunction "1_1") (pintype "passive"))
    )
    (net (code "45") (name "Net-(S3-WIPER)") (class "Default")
      (node (ref "R15") (pin "2") (pinfunction "2_2") (pintype "passive"))
      (node (ref "S3") (pin "2") (pinfunction "WIPER_2") (pintype "bidirectional"))
    )
    (net (code "46") (name "Net-(S4-WIPER)") (class "Default")
      (node (ref "R19") (pin "1") (pinfunction "1_1") (pintype "passive"))
      (node (ref "S4") (pin "2") (pinfunction "WIPER_2") (pintype "bidirectional"))
    )
    (net (code "47") (name "Net-(S5-WIPER)") (class "Default")
      (node (ref "R24") (pin "2") (pinfunction "2_2") (pintype "passive"))
      (node (ref "S5") (pin "2") (pinfunction "WIPER_2") (pintype "bidirectional"))
    )
    (net (code "48") (name "Net-(S6-WIPER)") (class "Default")
      (node (ref "R28") (pin "1") (pinfunction "1_1") (pintype "passive"))
      (node (ref "S6") (pin "2") (pinfunction "WIPER_2") (pintype "bidirectional"))
    )
    (net (code "49") (name "Net-(S7-WIPER)") (class "Default")
      (node (ref "R33") (pin "2") (pinfunction "2_2") (pintype "passive"))
      (node (ref "S7") (pin "2") (pinfunction "WIPER_2") (pintype "bidirectional"))
    )
    (net (code "50") (name "Net-(S8-WIPER)") (class "Default")
      (node (ref "R37") (pin "1") (pinfunction "1_1") (pintype "passive"))
      (node (ref "S8") (pin "2") (pinfunction "WIPER_2") (pintype "bidirectional"))
    )
    (net (code "51") (name "Net-(S9-WIPER)") (class "Default")
      (node (ref "R42") (pin "2") (pinfunction "2_2") (pintype "passive"))
      (node (ref "S9") (pin "2") (pinfunction "WIPER_2") (pintype "bidirectional"))
    )
    (net (code "52") (name "Net-(S10-WIPER)") (class "Default")
      (node (ref "R46") (pin "1") (pinfunction "1_1") (pintype "passive"))
      (node (ref "S10") (pin "2") (pinfunction "WIPER_2") (pintype "bidirectional"))
    )
    (net (code "53") (name "Net-(S11-WIPER)") (class "Default")
      (node (ref "R51") (pin "2") (pinfunction "2_2") (pintype "passive"))
      (node (ref "S11") (pin "2") (pinfunction "WIPER_2") (pintype "bidirectional"))
    )
    (net (code "54") (name "Net-(S12-WIPER)") (class "Default")
      (node (ref "R55") (pin "1") (pinfunction "1_1") (pintype "passive"))
      (node (ref "S12") (pin "2") (pinfunction "WIPER_2") (pintype "bidirectional"))
    )
    (net (code "55") (name "Net-(S13-WIPER)") (class "Default")
      (node (ref "R60") (pin "2") (pinfunction "2_2") (pintype "passive"))
      (node (ref "S13") (pin "2") (pinfunction "WIPER_2") (pintype "bidirectional"))
    )
    (net (code "56") (name "Net-(S14-WIPER)") (class "Default")
      (node (ref "R64") (pin "1") (pinfunction "1_1") (pintype "passive"))
      (node (ref "S14") (pin "2") (pinfunction "WIPER_2") (pintype "bidirectional"))
    )
    (net (code "57") (name "Net-(S15-WIPER)") (class "Default")
      (node (ref "R69") (pin "2") (pinfunction "2_2") (pintype "passive"))
      (node (ref "S15") (pin "2") (pinfunction "WIPER_2") (pintype "bidirectional"))
    )
    (net (code "58") (name "Net-(S16-WIPER)") (class "Default")
      (node (ref "R73") (pin "1") (pinfunction "1_1") (pintype "passive"))
      (node (ref "S16") (pin "2") (pinfunction "WIPER_2") (pintype "bidirectional"))
    )
    (net (code "59") (name "Net-(S17-WIPER)") (class "Default")
      (node (ref "R78") (pin "2") (pinfunction "2_2") (pintype "passive"))
      (node (ref "S17") (pin "2") (pinfunction "WIPER_2") (pintype "bidirectional"))
    )
    (net (code "60") (name "Net-(S18-WIPER)") (class "Default")
      (node (ref "R82") (pin "1") (pinfunction "1_1") (pintype "passive"))
      (node (ref "S18") (pin "2") (pinfunction "WIPER_2") (pintype "bidirectional"))
    )
    (net (code "61") (name "Net-(S19-WIPER)") (class "Default")
      (node (ref "R87") (pin "2") (pinfunction "2_2") (pintype "passive"))
      (node (ref "S19") (pin "2") (pinfunction "WIPER_2") (pintype "bidirectional"))
    )
    (net (code "62") (name "Net-(S20-WIPER)") (class "Default")
      (node (ref "R91") (pin "1") (pinfunction "1_1") (pintype "passive"))
      (node (ref "S20") (pin "2") (pinfunction "WIPER_2") (pintype "bidirectional"))
    )
    (net (code "63") (name "Net-(S23-WIPER)") (class "Default")
      (node (ref "R105") (pin "2") (pinfunction "2_2") (pintype "passive"))
      (node (ref "S23") (pin "2") (pinfunction "WIPER_2") (pintype "bidirectional"))
    )
    (net (code "64") (name "Net-(S24-WIPER)") (class "Default")
      (node (ref "R109") (pin "1") (pinfunction "1_1") (pintype "passive"))
      (node (ref "S24") (pin "2") (pinfunction "WIPER_2") (pintype "bidirectional"))
    )
    (net (code "65") (name "Net-(S25-WIPER)") (class "Default")
      (node (ref "R114") (pin "2") (pinfunction "2_2") (pintype "passive"))
      (node (ref "S25") (pin "2") (pinfunction "WIPER_2") (pintype "bidirectional"))
    )
    (net (code "66") (name "Net-(S26-WIPER)") (class "Default")
      (node (ref "R118") (pin "1") (pinfunction "1_1") (pintype "passive"))
      (node (ref "S26") (pin "2") (pinfunction "WIPER_2") (pintype "bidirectional"))
    )
    (net (code "67") (name "Net-(S27-WIPER)") (class "Default")
      (node (ref "R123") (pin "2") (pinfunction "2_2") (pintype "passive"))
      (node (ref "S27") (pin "2") (pinfunction "WIPER_2") (pintype "bidirectional"))
    )
    (net (code "68") (name "Net-(S28-WIPER)") (class "Default")
      (node (ref "R127") (pin "1") (pinfunction "1_1") (pintype "passive"))
      (node (ref "S28") (pin "2") (pinfunction "WIPER_2") (pintype "bidirectional"))
    )
    (net (code "69") (name "Net-(S31-WIPER)") (class "Default")
      (node (ref "R141") (pin "2") (pinfunction "2_2") (pintype "passive"))
      (node (ref "S31") (pin "2") (pinfunction "WIPER_2") (pintype "bidirectional"))
    )
    (net (code "70") (name "Net-(S32-WIPER)") (class "Default")
      (node (ref "R145") (pin "1") (pinfunction "1_1") (pintype "passive"))
      (node (ref "S32") (pin "2") (pinfunction "WIPER_2") (pintype "bidirectional"))
    )
    (net (code "71") (name "Net-(S33-WIPER)") (class "Default")
      (node (ref "R150") (pin "2") (pinfunction "2_2") (pintype "passive"))
      (node (ref "S33") (pin "2") (pinfunction "WIPER_2") (pintype "bidirectional"))
    )
    (net (code "72") (name "Net-(S34-WIPER)") (class "Default")
      (node (ref "R155") (pin "1") (pinfunction "1_1") (pintype "passive"))
      (node (ref "S34") (pin "2") (pinfunction "WIPER_2") (pintype "bidirectional"))
    )
    (net (code "73") (name "Net-(S35-WIPER)") (class "Default")
      (node (ref "R168") (pin "2") (pinfunction "2_2") (pintype "passive"))
      (node (ref "S35") (pin "2") (pinfunction "WIPER_2") (pintype "bidirectional"))
    )
    (net (code "74") (name "Net-(S36-WIPER)") (class "Default")
      (node (ref "R172") (pin "1") (pinfunction "1_1") (pintype "passive"))
      (node (ref "S36") (pin "2") (pinfunction "WIPER_2") (pintype "bidirectional"))
    )
    (net (code "75") (name "Net-(S39-WIPER)") (class "Default")
      (node (ref "R186") (pin "2") (pinfunction "2_2") (pintype "passive"))
      (node (ref "S39") (pin "2") (pinfunction "WIPER_2") (pintype "bidirectional"))
    )
    (net (code "76") (name "Net-(S40-WIPER)") (class "Default")
      (node (ref "R190") (pin "1") (pinfunction "1_1") (pintype "passive"))
      (node (ref "S40") (pin "2") (pinfunction "WIPER_2") (pintype "bidirectional"))
    )
    (net (code "77") (name "Net-(U1-AC)") (class "Default")
      (node (ref "POW3") (pin "1") (pinfunction "1_1") (pintype "passive"))
      (node (ref "U1") (pin "3") (pinfunction "AC_3") (pintype "input"))
      (node (ref "X2") (pin "1") (pinfunction "S_1") (pintype "passive"))
    )
    (net (code "78") (name "Net-(U1-AC_2)") (class "Default")
      (node (ref "POW4") (pin "1") (pinfunction "1_1") (pintype "passive"))
      (node (ref "U1") (pin "4") (pinfunction "AC_2_4") (pintype "input"))
      (node (ref "X2") (pin "4") (pinfunction "S_4") (pintype "passive"))
    )
    (net (code "79") (name "Net-(U1-OUT-)") (class "Default")
      (node (ref "-V_IN1") (pin "1") (pinfunction "1_1") (pintype "passive"))
      (node (ref "C1") (pin "1") (pinfunction "1_1") (pintype "passive"))
      (node (ref "C17") (pin "-") (pinfunction "-_-") (pintype "passive"))
      (node (ref "U1") (pin "2") (pinfunction "OUT-_2") (pintype "output"))
      (node (ref "U2") (pin "4") (pinfunction "VIN_4") (pintype "power_in"))
    )
    (net (code "80") (name "Net-(U2-GND)") (class "Default")
      (node (ref "C16") (pin "-") (pinfunction "-_-") (pintype "passive"))
      (node (ref "R151") (pin "1") (pinfunction "1_1") (pintype "passive"))
      (node (ref "R2") (pin "2") (pinfunction "2_2") (pintype "passive"))
      (node (ref "U2") (pin "1") (pinfunction "GND_1") (pintype "power_in"))
    )
    (net (code "81") (name "Net-(U5-IN+)") (class "Default")
      (node (ref "R16") (pin "2") (pinfunction "2_2") (pintype "passive"))
      (node (ref "U5") (pin "3") (pinfunction "IN+_3") (pintype "input"))
    )
    (net (code "82") (name "Net-(U5-IN-)") (class "Default")
      (node (ref "R15") (pin "1") (pinfunction "1_1") (pintype "passive"))
      (node (ref "U5") (pin "2") (pinfunction "IN-_2") (pintype "input"))
    )
    (net (code "83") (name "Net-(U5-OUT)") (class "Default")
      (node (ref "R20") (pin "1") (pinfunction "1_1") (pintype "passive"))
      (node (ref "U5") (pin "6") (pinfunction "OUT_6") (pintype "output"))
    )
    (net (code "84") (name "Net-(U5-SHDN)") (class "Default")
      (node (ref "R23") (pin "1") (pinfunction "1_1") (pintype "passive"))
      (node (ref "U5") (pin "8") (pinfunction "SHDN_8") (pintype "passive"))
    )
    (net (code "85") (name "Net-(U6-IN+)") (class "Default")
      (node (ref "R21") (pin "2") (pinfunction "2_2") (pintype "passive"))
      (node (ref "U6") (pin "3") (pinfunction "IN+_3") (pintype "input"))
    )
    (net (code "86") (name "Net-(U6-IN-)") (class "Default")
      (node (ref "R19") (pin "2") (pinfunction "2_2") (pintype "passive"))
      (node (ref "U6") (pin "2") (pinfunction "IN-_2") (pintype "input"))
    )
    (net (code "87") (name "Net-(U6-OUT)") (class "Default")
      (node (ref "R17") (pin "1") (pinfunction "1_1") (pintype "passive"))
      (node (ref "U6") (pin "6") (pinfunction "OUT_6") (pintype "output"))
    )
    (net (code "88") (name "Net-(U7-IN+)") (class "Default")
      (node (ref "R25") (pin "2") (pinfunction "2_2") (pintype "passive"))
      (node (ref "U7") (pin "3") (pinfunction "IN+_3") (pintype "input"))
    )
    (net (code "89") (name "Net-(U7-IN-)") (class "Default")
      (node (ref "R24") (pin "1") (pinfunction "1_1") (pintype "passive"))
      (node (ref "U7") (pin "2") (pinfunction "IN-_2") (pintype "input"))
    )
    (net (code "90") (name "Net-(U7-OUT)") (class "Default")
      (node (ref "R29") (pin "1") (pinfunction "1_1") (pintype "passive"))
      (node (ref "U7") (pin "6") (pinfunction "OUT_6") (pintype "output"))
    )
    (net (code "91") (name "Net-(U7-SHDN)") (class "Default")
      (node (ref "R32") (pin "1") (pinfunction "1_1") (pintype "passive"))
      (node (ref "U7") (pin "8") (pinfunction "SHDN_8") (pintype "passive"))
    )
    (net (code "92") (name "Net-(U8-IN+)") (class "Default")
      (node (ref "R30") (pin "2") (pinfunction "2_2") (pintype "passive"))
      (node (ref "U8") (pin "3") (pinfunction "IN+_3") (pintype "input"))
    )
    (net (code "93") (name "Net-(U8-IN-)") (class "Default")
      (node (ref "R28") (pin "2") (pinfunction "2_2") (pintype "passive"))
      (node (ref "U8") (pin "2") (pinfunction "IN-_2") (pintype "input"))
    )
    (net (code "94") (name "Net-(U8-OUT)") (class "Default")
      (node (ref "R26") (pin "1") (pinfunction "1_1") (pintype "passive"))
      (node (ref "U8") (pin "6") (pinfunction "OUT_6") (pintype "output"))
    )
    (net (code "95") (name "Net-(U9-IN+)") (class "Default")
      (node (ref "R34") (pin "2") (pinfunction "2_2") (pintype "passive"))
      (node (ref "U9") (pin "3") (pinfunction "IN+_3") (pintype "input"))
    )
    (net (code "96") (name "Net-(U9-IN-)") (class "Default")
      (node (ref "R33") (pin "1") (pinfunction "1_1") (pintype "passive"))
      (node (ref "U9") (pin "2") (pinfunction "IN-_2") (pintype "input"))
    )
    (net (code "97") (name "Net-(U9-OUT)") (class "Default")
      (node (ref "R38") (pin "1") (pinfunction "1_1") (pintype "passive"))
      (node (ref "U9") (pin "6") (pinfunction "OUT_6") (pintype "output"))
    )
    (net (code "98") (name "Net-(U9-SHDN)") (class "Default")
      (node (ref "R41") (pin "1") (pinfunction "1_1") (pintype "passive"))
      (node (ref "U9") (pin "8") (pinfunction "SHDN_8") (pintype "passive"))
    )
    (net (code "99") (name "Net-(U10-IN+)") (class "Default")
      (node (ref "R39") (pin "2") (pinfunction "2_2") (pintype "passive"))
      (node (ref "U10") (pin "3") (pinfunction "IN+_3") (pintype "input"))
    )
    (net (code "100") (name "Net-(U10-IN-)") (class "Default")
      (node (ref "R37") (pin "2") (pinfunction "2_2") (pintype "passive"))
      (node (ref "U10") (pin "2") (pinfunction "IN-_2") (pintype "input"))
    )
    (net (code "101") (name "Net-(U10-OUT)") (class "Default")
      (node (ref "R35") (pin "1") (pinfunction "1_1") (pintype "passive"))
      (node (ref "U10") (pin "6") (pinfunction "OUT_6") (pintype "output"))
    )
    (net (code "102") (name "Net-(U11-IN+)") (class "Default")
      (node (ref "R43") (pin "2") (pinfunction "2_2") (pintype "passive"))
      (node (ref "U11") (pin "3") (pinfunction "IN+_3") (pintype "input"))
    )
    (net (code "103") (name "Net-(U11-IN-)") (class "Default")
      (node (ref "R42") (pin "1") (pinfunction "1_1") (pintype "passive"))
      (node (ref "U11") (pin "2") (pinfunction "IN-_2") (pintype "input"))
    )
    (net (code "104") (name "Net-(U11-OUT)") (class "Default")
      (node (ref "R47") (pin "1") (pinfunction "1_1") (pintype "passive"))
      (node (ref "U11") (pin "6") (pinfunction "OUT_6") (pintype "output"))
    )
    (net (code "105") (name "Net-(U11-SHDN)") (class "Default")
      (node (ref "R50") (pin "1") (pinfunction "1_1") (pintype "passive"))
      (node (ref "U11") (pin "8") (pinfunction "SHDN_8") (pintype "passive"))
    )
    (net (code "106") (name "Net-(U12-IN+)") (class "Default")
      (node (ref "R48") (pin "2") (pinfunction "2_2") (pintype "passive"))
      (node (ref "U12") (pin "3") (pinfunction "IN+_3") (pintype "input"))
    )
    (net (code "107") (name "Net-(U12-IN-)") (class "Default")
      (node (ref "R46") (pin "2") (pinfunction "2_2") (pintype "passive"))
      (node (ref "U12") (pin "2") (pinfunction "IN-_2") (pintype "input"))
    )
    (net (code "108") (name "Net-(U12-OUT)") (class "Default")
      (node (ref "R44") (pin "1") (pinfunction "1_1") (pintype "passive"))
      (node (ref "U12") (pin "6") (pinfunction "OUT_6") (pintype "output"))
    )
    (net (code "109") (name "Net-(U13-IN+)") (class "Default")
      (node (ref "R52") (pin "2") (pinfunction "2_2") (pintype "passive"))
      (node (ref "U13") (pin "3") (pinfunction "IN+_3") (pintype "input"))
    )
    (net (code "110") (name "Net-(U13-IN-)") (class "Default")
      (node (ref "R51") (pin "1") (pinfunction "1_1") (pintype "passive"))
      (node (ref "U13") (pin "2") (pinfunction "IN-_2") (pintype "input"))
    )
    (net (code "111") (name "Net-(U13-OUT)") (class "Default")
      (node (ref "R56") (pin "1") (pinfunction "1_1") (pintype "passive"))
      (node (ref "U13") (pin "6") (pinfunction "OUT_6") (pintype "output"))
    )
    (net (code "112") (name "Net-(U13-SHDN)") (class "Default")
      (node (ref "R59") (pin "1") (pinfunction "1_1") (pintype "passive"))
      (node (ref "U13") (pin "8") (pinfunction "SHDN_8") (pintype "passive"))
    )
    (net (code "113") (name "Net-(U14-IN+)") (class "Default")
      (node (ref "R57") (pin "2") (pinfunction "2_2") (pintype "passive"))
      (node (ref "U14") (pin "3") (pinfunction "IN+_3") (pintype "input"))
    )
    (net (code "114") (name "Net-(U14-IN-)") (class "Default")
      (node (ref "R55") (pin "2") (pinfunction "2_2") (pintype "passive"))
      (node (ref "U14") (pin "2") (pinfunction "IN-_2") (pintype "input"))
    )
    (net (code "115") (name "Net-(U14-OUT)") (class "Default")
      (node (ref "R53") (pin "1") (pinfunction "1_1") (pintype "passive"))
      (node (ref "U14") (pin "6") (pinfunction "OUT_6") (pintype "output"))
    )
    (net (code "116") (name "Net-(U15-IN+)") (class "Default")
      (node (ref "R61") (pin "2") (pinfunction "2_2") (pintype "passive"))
      (node (ref "U15") (pin "3") (pinfunction "IN+_3") (pintype "input"))
    )
    (net (code "117") (name "Net-(U15-IN-)") (class "Default")
      (node (ref "R60") (pin "1") (pinfunction "1_1") (pintype "passive"))
      (node (ref "U15") (pin "2") (pinfunction "IN-_2") (pintype "input"))
    )
    (net (code "118") (name "Net-(U15-OUT)") (class "Default")
      (node (ref "R65") (pin "1") (pinfunction "1_1") (pintype "passive"))
      (node (ref "U15") (pin "6") (pinfunction "OUT_6") (pintype "output"))
    )
    (net (code "119") (name "Net-(U15-SHDN)") (class "Default")
      (node (ref "R68") (pin "1") (pinfunction "1_1") (pintype "passive"))
      (node (ref "U15") (pin "8") (pinfunction "SHDN_8") (pintype "passive"))
    )
    (net (code "120") (name "Net-(U16-IN+)") (class "Default")
      (node (ref "R66") (pin "2") (pinfunction "2_2") (pintype "passive"))
      (node (ref "U16") (pin "3") (pinfunction "IN+_3") (pintype "input"))
    )
    (net (code "121") (name "Net-(U16-IN-)") (class "Default")
      (node (ref "R64") (pin "2") (pinfunction "2_2") (pintype "passive"))
      (node (ref "U16") (pin "2") (pinfunction "IN-_2") (pintype "input"))
    )
    (net (code "122") (name "Net-(U16-OUT)") (class "Default")
      (node (ref "R62") (pin "1") (pinfunction "1_1") (pintype "passive"))
      (node (ref "U16") (pin "6") (pinfunction "OUT_6") (pintype "output"))
    )
    (net (code "123") (name "Net-(U17-IN+)") (class "Default")
      (node (ref "R70") (pin "2") (pinfunction "2_2") (pintype "passive"))
      (node (ref "U17") (pin "3") (pinfunction "IN+_3") (pintype "input"))
    )
    (net (code "124") (name "Net-(U17-IN-)") (class "Default")
      (node (ref "R69") (pin "1") (pinfunction "1_1") (pintype "passive"))
      (node (ref "U17") (pin "2") (pinfunction "IN-_2") (pintype "input"))
    )
    (net (code "125") (name "Net-(U17-OUT)") (class "Default")
      (node (ref "R74") (pin "1") (pinfunction "1_1") (pintype "passive"))
      (node (ref "U17") (pin "6") (pinfunction "OUT_6") (pintype "output"))
    )
    (net (code "126") (name "Net-(U17-SHDN)") (class "Default")
      (node (ref "R77") (pin "1") (pinfunction "1_1") (pintype "passive"))
      (node (ref "U17") (pin "8") (pinfunction "SHDN_8") (pintype "passive"))
    )
    (net (code "127") (name "Net-(U18-IN+)") (class "Default")
      (node (ref "R75") (pin "2") (pinfunction "2_2") (pintype "passive"))
      (node (ref "U18") (pin "3") (pinfunction "IN+_3") (pintype "input"))
    )
    (net (code "128") (name "Net-(U18-IN-)") (class "Default")
      (node (ref "R73") (pin "2") (pinfunction "2_2") (pintype "passive"))
      (node (ref "U18") (pin "2") (pinfunction "IN-_2") (pintype "input"))
    )
    (net (code "129") (name "Net-(U18-OUT)") (class "Default")
      (node (ref "R71") (pin "1") (pinfunction "1_1") (pintype "passive"))
      (node (ref "U18") (pin "6") (pinfunction "OUT_6") (pintype "output"))
    )
    (net (code "130") (name "Net-(U19-IN+)") (class "Default")
      (node (ref "R79") (pin "2") (pinfunction "2_2") (pintype "passive"))
      (node (ref "U19") (pin "3") (pinfunction "IN+_3") (pintype "input"))
    )
    (net (code "131") (name "Net-(U19-IN-)") (class "Default")
      (node (ref "R78") (pin "1") (pinfunction "1_1") (pintype "passive"))
      (node (ref "U19") (pin "2") (pinfunction "IN-_2") (pintype "input"))
    )
    (net (code "132") (name "Net-(U19-OUT)") (class "Default")
      (node (ref "R83") (pin "1") (pinfunction "1_1") (pintype "passive"))
      (node (ref "U19") (pin "6") (pinfunction "OUT_6") (pintype "output"))
    )
    (net (code "133") (name "Net-(U19-SHDN)") (class "Default")
      (node (ref "R86") (pin "1") (pinfunction "1_1") (pintype "passive"))
      (node (ref "U19") (pin "8") (pinfunction "SHDN_8") (pintype "passive"))
    )
    (net (code "134") (name "Net-(U20-IN+)") (class "Default")
      (node (ref "R84") (pin "2") (pinfunction "2_2") (pintype "passive"))
      (node (ref "U20") (pin "3") (pinfunction "IN+_3") (pintype "input"))
    )
    (net (code "135") (name "Net-(U20-IN-)") (class "Default")
      (node (ref "R82") (pin "2") (pinfunction "2_2") (pintype "passive"))
      (node (ref "U20") (pin "2") (pinfunction "IN-_2") (pintype "input"))
    )
    (net (code "136") (name "Net-(U20-OUT)") (class "Default")
      (node (ref "R80") (pin "1") (pinfunction "1_1") (pintype "passive"))
      (node (ref "U20") (pin "6") (pinfunction "OUT_6") (pintype "output"))
    )
    (net (code "137") (name "Net-(U21-IN+)") (class "Default")
      (node (ref "R88") (pin "2") (pinfunction "2_2") (pintype "passive"))
      (node (ref "U21") (pin "3") (pinfunction "IN+_3") (pintype "input"))
    )
    (net (code "138") (name "Net-(U21-IN-)") (class "Default")
      (node (ref "R87") (pin "1") (pinfunction "1_1") (pintype "passive"))
      (node (ref "U21") (pin "2") (pinfunction "IN-_2") (pintype "input"))
    )
    (net (code "139") (name "Net-(U21-OUT)") (class "Default")
      (node (ref "R92") (pin "1") (pinfunction "1_1") (pintype "passive"))
      (node (ref "U21") (pin "6") (pinfunction "OUT_6") (pintype "output"))
    )
    (net (code "140") (name "Net-(U21-SHDN)") (class "Default")
      (node (ref "R95") (pin "1") (pinfunction "1_1") (pintype "passive"))
      (node (ref "U21") (pin "8") (pinfunction "SHDN_8") (pintype "passive"))
    )
    (net (code "141") (name "Net-(U22-IN+)") (class "Default")
      (node (ref "R93") (pin "2") (pinfunction "2_2") (pintype "passive"))
      (node (ref "U22") (pin "3") (pinfunction "IN+_3") (pintype "input"))
    )
    (net (code "142") (name "Net-(U22-IN-)") (class "Default")
      (node (ref "R91") (pin "2") (pinfunction "2_2") (pintype "passive"))
      (node (ref "U22") (pin "2") (pinfunction "IN-_2") (pintype "input"))
    )
    (net (code "143") (name "Net-(U22-OUT)") (class "Default")
      (node (ref "R89") (pin "1") (pinfunction "1_1") (pintype "passive"))
      (node (ref "U22") (pin "6") (pinfunction "OUT_6") (pintype "output"))
    )
    (net (code "144") (name "Net-(U25-IN+)") (class "Default")
      (node (ref "R106") (pin "2") (pinfunction "2_2") (pintype "passive"))
      (node (ref "U25") (pin "3") (pinfunction "IN+_3") (pintype "input"))
    )
    (net (code "145") (name "Net-(U25-IN-)") (class "Default")
      (node (ref "R105") (pin "1") (pinfunction "1_1") (pintype "passive"))
      (node (ref "U25") (pin "2") (pinfunction "IN-_2") (pintype "input"))
    )
    (net (code "146") (name "Net-(U25-OUT)") (class "Default")
      (node (ref "R110") (pin "1") (pinfunction "1_1") (pintype "passive"))
      (node (ref "U25") (pin "6") (pinfunction "OUT_6") (pintype "output"))
    )
    (net (code "147") (name "Net-(U25-SHDN)") (class "Default")
      (node (ref "R113") (pin "1") (pinfunction "1_1") (pintype "passive"))
      (node (ref "U25") (pin "8") (pinfunction "SHDN_8") (pintype "passive"))
    )
    (net (code "148") (name "Net-(U26-IN+)") (class "Default")
      (node (ref "R111") (pin "2") (pinfunction "2_2") (pintype "passive"))
      (node (ref "U26") (pin "3") (pinfunction "IN+_3") (pintype "input"))
    )
    (net (code "149") (name "Net-(U26-IN-)") (class "Default")
      (node (ref "R109") (pin "2") (pinfunction "2_2") (pintype "passive"))
      (node (ref "U26") (pin "2") (pinfunction "IN-_2") (pintype "input"))
    )
    (net (code "150") (name "Net-(U26-OUT)") (class "Default")
      (node (ref "R107") (pin "1") (pinfunction "1_1") (pintype "passive"))
      (node (ref "U26") (pin "6") (pinfunction "OUT_6") (pintype "output"))
    )
    (net (code "151") (name "Net-(U27-IN+)") (class "Default")
      (node (ref "R115") (pin "2") (pinfunction "2_2") (pintype "passive"))
      (node (ref "U27") (pin "3") (pinfunction "IN+_3") (pintype "input"))
    )
    (net (code "152") (name "Net-(U27-IN-)") (class "Default")
      (node (ref "R114") (pin "1") (pinfunction "1_1") (pintype "passive"))
      (node (ref "U27") (pin "2") (pinfunction "IN-_2") (pintype "input"))
    )
    (net (code "153") (name "Net-(U27-OUT)") (class "Default")
      (node (ref "R119") (pin "1") (pinfunction "1_1") (pintype "passive"))
      (node (ref "U27") (pin "6") (pinfunction "OUT_6") (pintype "output"))
    )
    (net (code "154") (name "Net-(U27-SHDN)") (class "Default")
      (node (ref "R122") (pin "1") (pinfunction "1_1") (pintype "passive"))
      (node (ref "U27") (pin "8") (pinfunction "SHDN_8") (pintype "passive"))
    )
    (net (code "155") (name "Net-(U28-IN+)") (class "Default")
      (node (ref "R120") (pin "2") (pinfunction "2_2") (pintype "passive"))
      (node (ref "U28") (pin "3") (pinfunction "IN+_3") (pintype "input"))
    )
    (net (code "156") (name "Net-(U28-IN-)") (class "Default")
      (node (ref "R118") (pin "2") (pinfunction "2_2") (pintype "passive"))
      (node (ref "U28") (pin "2") (pinfunction "IN-_2") (pintype "input"))
    )
    (net (code "157") (name "Net-(U28-OUT)") (class "Default")
      (node (ref "R116") (pin "1") (pinfunction "1_1") (pintype "passive"))
      (node (ref "U28") (pin "6") (pinfunction "OUT_6") (pintype "output"))
    )
    (net (code "158") (name "Net-(U29-IN+)") (class "Default")
      (node (ref "R124") (pin "2") (pinfunction "2_2") (pintype "passive"))
      (node (ref "U29") (pin "3") (pinfunction "IN+_3") (pintype "input"))
    )
    (net (code "159") (name "Net-(U29-IN-)") (class "Default")
      (node (ref "R123") (pin "1") (pinfunction "1_1") (pintype "passive"))
      (node (ref "U29") (pin "2") (pinfunction "IN-_2") (pintype "input"))
    )
    (net (code "160") (name "Net-(U29-OUT)") (class "Default")
      (node (ref "R128") (pin "1") (pinfunction "1_1") (pintype "passive"))
      (node (ref "U29") (pin "6") (pinfunction "OUT_6") (pintype "output"))
    )
    (net (code "161") (name "Net-(U29-SHDN)") (class "Default")
      (node (ref "R131") (pin "1") (pinfunction "1_1") (pintype "passive"))
      (node (ref "U29") (pin "8") (pinfunction "SHDN_8") (pintype "passive"))
    )
    (net (code "162") (name "Net-(U30-IN+)") (class "Default")
      (node (ref "R129") (pin "2") (pinfunction "2_2") (pintype "passive"))
      (node (ref "U30") (pin "3") (pinfunction "IN+_3") (pintype "input"))
    )
    (net (code "163") (name "Net-(U30-IN-)") (class "Default")
      (node (ref "R127") (pin "2") (pinfunction "2_2") (pintype "passive"))
      (node (ref "U30") (pin "2") (pinfunction "IN-_2") (pintype "input"))
    )
    (net (code "164") (name "Net-(U30-OUT)") (class "Default")
      (node (ref "R125") (pin "1") (pinfunction "1_1") (pintype "passive"))
      (node (ref "U30") (pin "6") (pinfunction "OUT_6") (pintype "output"))
    )
    (net (code "165") (name "Net-(U33-IN+)") (class "Default")
      (node (ref "R142") (pin "2") (pinfunction "2_2") (pintype "passive"))
      (node (ref "U33") (pin "3") (pinfunction "IN+_3") (pintype "input"))
    )
    (net (code "166") (name "Net-(U33-IN-)") (class "Default")
      (node (ref "R141") (pin "1") (pinfunction "1_1") (pintype "passive"))
      (node (ref "U33") (pin "2") (pinfunction "IN-_2") (pintype "input"))
    )
    (net (code "167") (name "Net-(U33-OUT)") (class "Default")
      (node (ref "R146") (pin "1") (pinfunction "1_1") (pintype "passive"))
      (node (ref "U33") (pin "6") (pinfunction "OUT_6") (pintype "output"))
    )
    (net (code "168") (name "Net-(U33-SHDN)") (class "Default")
      (node (ref "R149") (pin "1") (pinfunction "1_1") (pintype "passive"))
      (node (ref "U33") (pin "8") (pinfunction "SHDN_8") (pintype "passive"))
    )
    (net (code "169") (name "Net-(U34-IN+)") (class "Default")
      (node (ref "R147") (pin "2") (pinfunction "2_2") (pintype "passive"))
      (node (ref "U34") (pin "3") (pinfunction "IN+_3") (pintype "input"))
    )
    (net (code "170") (name "Net-(U34-IN-)") (class "Default")
      (node (ref "R145") (pin "2") (pinfunction "2_2") (pintype "passive"))
      (node (ref "U34") (pin "2") (pinfunction "IN-_2") (pintype "input"))
    )
    (net (code "171") (name "Net-(U34-OUT)") (class "Default")
      (node (ref "R143") (pin "1") (pinfunction "1_1") (pintype "passive"))
      (node (ref "U34") (pin "6") (pinfunction "OUT_6") (pintype "output"))
    )
    (net (code "172") (name "Net-(U35-IN+)") (class "Default")
      (node (ref "R152") (pin "2") (pinfunction "2_2") (pintype "passive"))
      (node (ref "U35") (pin "3") (pinfunction "IN+_3") (pintype "input"))
    )
    (net (code "173") (name "Net-(U35-IN-)") (class "Default")
      (node (ref "R150") (pin "1") (pinfunction "1_1") (pintype "passive"))
      (node (ref "U35") (pin "2") (pinfunction "IN-_2") (pintype "input"))
    )
    (net (code "174") (name "Net-(U35-OUT)") (class "Default")
      (node (ref "R156") (pin "1") (pinfunction "1_1") (pintype "passive"))
      (node (ref "U35") (pin "6") (pinfunction "OUT_6") (pintype "output"))
    )
    (net (code "175") (name "Net-(U35-SHDN)") (class "Default")
      (node (ref "R167") (pin "1") (pinfunction "1_1") (pintype "passive"))
      (node (ref "U35") (pin "8") (pinfunction "SHDN_8") (pintype "passive"))
    )
    (net (code "176") (name "Net-(U36-IN+)") (class "Default")
      (node (ref "R157") (pin "2") (pinfunction "2_2") (pintype "passive"))
      (node (ref "U36") (pin "3") (pinfunction "IN+_3") (pintype "input"))
    )
    (net (code "177") (name "Net-(U36-IN-)") (class "Default")
      (node (ref "R155") (pin "2") (pinfunction "2_2") (pintype "passive"))
      (node (ref "U36") (pin "2") (pinfunction "IN-_2") (pintype "input"))
    )
    (net (code "178") (name "Net-(U36-OUT)") (class "Default")
      (node (ref "R153") (pin "1") (pinfunction "1_1") (pintype "passive"))
      (node (ref "U36") (pin "6") (pinfunction "OUT_6") (pintype "output"))
    )
    (net (code "179") (name "Net-(U37-IN+)") (class "Default")
      (node (ref "R169") (pin "2") (pinfunction "2_2") (pintype "passive"))
      (node (ref "U37") (pin "3") (pinfunction "IN+_3") (pintype "input"))
    )
    (net (code "180") (name "Net-(U37-IN-)") (class "Default")
      (node (ref "R168") (pin "1") (pinfunction "1_1") (pintype "passive"))
      (node (ref "U37") (pin "2") (pinfunction "IN-_2") (pintype "input"))
    )
    (net (code "181") (name "Net-(U37-OUT)") (class "Default")
      (node (ref "R173") (pin "1") (pinfunction "1_1") (pintype "passive"))
      (node (ref "U37") (pin "6") (pinfunction "OUT_6") (pintype "output"))
    )
    (net (code "182") (name "Net-(U37-SHDN)") (class "Default")
      (node (ref "R176") (pin "1") (pinfunction "1_1") (pintype "passive"))
      (node (ref "U37") (pin "8") (pinfunction "SHDN_8") (pintype "passive"))
    )
    (net (code "183") (name "Net-(U38-GATE)") (class "Default")
      (node (ref "R165") (pin "2") (pinfunction "2_2") (pintype "passive"))
      (node (ref "U38") (pin "1") (pinfunction "GATE_1") (pintype "passive"))
    )
    (net (code "184") (name "Net-(U39-IN+)") (class "Default")
      (node (ref "R160") (pin "2") (pinfunction "2_2") (pintype "passive"))
      (node (ref "U39") (pin "3") (pinfunction "IN+_3") (pintype "input"))
    )
    (net (code "185") (name "Net-(U39-IN-)") (class "Default")
      (node (ref "R159") (pin "2") (pinfunction "2_2") (pintype "passive"))
      (node (ref "U39") (pin "2") (pinfunction "IN-_2") (pintype "input"))
    )
    (net (code "186") (name "Net-(U39-OUT)") (class "Default")
      (node (ref "EN_TP1") (pin "1") (pinfunction "1_1") (pintype "passive"))
      (node (ref "R166") (pin "1") (pinfunction "1_1") (pintype "passive"))
      (node (ref "U39") (pin "6") (pinfunction "OUT_6") (pintype "output"))
    )
    (net (code "187") (name "Net-(U40-IN+)") (class "Default")
      (node (ref "R164") (pin "2") (pinfunction "2_2") (pintype "passive"))
      (node (ref "U40") (pin "3") (pinfunction "IN+_3") (pintype "input"))
    )
    (net (code "188") (name "Net-(U40-IN-)") (class "Default")
      (node (ref "R163") (pin "2") (pinfunction "2_2") (pintype "passive"))
      (node (ref "U40") (pin "2") (pinfunction "IN-_2") (pintype "input"))
    )
    (net (code "189") (name "Net-(U41-IN+)") (class "Default")
      (node (ref "R174") (pin "2") (pinfunction "2_2") (pintype "passive"))
      (node (ref "U41") (pin "3") (pinfunction "IN+_3") (pintype "input"))
    )
    (net (code "190") (name "Net-(U41-IN-)") (class "Default")
      (node (ref "R172") (pin "2") (pinfunction "2_2") (pintype "passive"))
      (node (ref "U41") (pin "2") (pinfunction "IN-_2") (pintype "input"))
    )
    (net (code "191") (name "Net-(U41-OUT)") (class "Default")
      (node (ref "R170") (pin "1") (pinfunction "1_1") (pintype "passive"))
      (node (ref "U41") (pin "6") (pinfunction "OUT_6") (pintype "output"))
    )
    (net (code "192") (name "Net-(U44-IN+)") (class "Default")
      (node (ref "R187") (pin "2") (pinfunction "2_2") (pintype "passive"))
      (node (ref "U44") (pin "3") (pinfunction "IN+_3") (pintype "input"))
    )
    (net (code "193") (name "Net-(U44-IN-)") (class "Default")
      (node (ref "R186") (pin "1") (pinfunction "1_1") (pintype "passive"))
      (node (ref "U44") (pin "2") (pinfunction "IN-_2") (pintype "input"))
    )
    (net (code "194") (name "Net-(U44-OUT)") (class "Default")
      (node (ref "R191") (pin "1") (pinfunction "1_1") (pintype "passive"))
      (node (ref "U44") (pin "6") (pinfunction "OUT_6") (pintype "output"))
    )
    (net (code "195") (name "Net-(U44-SHDN)") (class "Default")
      (node (ref "R194") (pin "1") (pinfunction "1_1") (pintype "passive"))
      (node (ref "U44") (pin "8") (pinfunction "SHDN_8") (pintype "passive"))
    )
    (net (code "196") (name "Net-(U45-IN+)") (class "Default")
      (node (ref "R192") (pin "2") (pinfunction "2_2") (pintype "passive"))
      (node (ref "U45") (pin "3") (pinfunction "IN+_3") (pintype "input"))
    )
    (net (code "197") (name "Net-(U45-IN-)") (class "Default")
      (node (ref "R190") (pin "2") (pinfunction "2_2") (pintype "passive"))
      (node (ref "U45") (pin "2") (pinfunction "IN-_2") (pintype "input"))
    )
    (net (code "198") (name "Net-(U45-OUT)") (class "Default")
      (node (ref "R188") (pin "1") (pinfunction "1_1") (pintype "passive"))
      (node (ref "U45") (pin "6") (pinfunction "OUT_6") (pintype "output"))
    )
    (net (code "199") (name "TF1") (class "Default")
      (node (ref "J2") (pin "1") (pinfunction "1_1") (pintype "bidirectional"))
      (node (ref "R17") (pin "2") (pinfunction "2_2") (pintype "passive"))
      (node (ref "R18") (pin "1") (pinfunction "1_1") (pintype "passive"))
      (node (ref "TO_FPGA_2") (pin "1") (pinfunction "1_1") (pintype "passive"))
    )
    (net (code "200") (name "TF2") (class "Default")
      (node (ref "J2") (pin "2") (pinfunction "2_2") (pintype "bidirectional"))
      (node (ref "R35") (pin "2") (pinfunction "2_2") (pintype "passive"))
      (node (ref "R36") (pin "1") (pinfunction "1_1") (pintype "passive"))
      (node (ref "TO_FPGA_4") (pin "1") (pinfunction "1_1") (pintype "passive"))
    )
    (net (code "201") (name "TF3") (class "Default")
      (node (ref "J2") (pin "3") (pinfunction "3_3") (pintype "bidirectional"))
      (node (ref "R26") (pin "2") (pinfunction "2_2") (pintype "passive"))
      (node (ref "R27") (pin "1") (pinfunction "1_1") (pintype "passive"))
      (node (ref "TO_FPGA_3") (pin "1") (pinfunction "1_1") (pintype "passive"))
    )
    (net (code "202") (name "TF4") (class "Default")
      (node (ref "J2") (pin "4") (pinfunction "4_4") (pintype "bidirectional"))
      (node (ref "R53") (pin "2") (pinfunction "2_2") (pintype "passive"))
      (node (ref "R54") (pin "1") (pinfunction "1_1") (pintype "passive"))
      (node (ref "TO_FPGA_6") (pin "1") (pinfunction "1_1") (pintype "passive"))
    )
    (net (code "203") (name "TF5") (class "Default")
      (node (ref "J2") (pin "5") (pinfunction "5_5") (pintype "bidirectional"))
      (node (ref "R71") (pin "2") (pinfunction "2_2") (pintype "passive"))
      (node (ref "R72") (pin "1") (pinfunction "1_1") (pintype "passive"))
      (node (ref "TO_FPGA_8") (pin "1") (pinfunction "1_1") (pintype "passive"))
    )
    (net (code "204") (name "TF6") (class "Default")
      (node (ref "J2") (pin "6") (pinfunction "6_6") (pintype "bidirectional"))
      (node (ref "R89") (pin "2") (pinfunction "2_2") (pintype "passive"))
      (node (ref "R90") (pin "1") (pinfunction "1_1") (pintype "passive"))
      (node (ref "TO_FPGA_10") (pin "1") (pinfunction "1_1") (pintype "passive"))
    )
    (net (code "205") (name "TF7") (class "Default")
      (node (ref "J2") (pin "7") (pinfunction "7_7") (pintype "bidirectional"))
      (node (ref "R107") (pin "2") (pinfunction "2_2") (pintype "passive"))
      (node (ref "R108") (pin "1") (pinfunction "1_1") (pintype "passive"))
      (node (ref "TO_FPGA_12") (pin "1") (pinfunction "1_1") (pintype "passive"))
    )
    (net (code "206") (name "TF8") (class "Default")
      (node (ref "J2") (pin "8") (pinfunction "8_8") (pintype "bidirectional"))
      (node (ref "R125") (pin "2") (pinfunction "2_2") (pintype "passive"))
      (node (ref "R126") (pin "1") (pinfunction "1_1") (pintype "passive"))
      (node (ref "TO_FPGA_14") (pin "1") (pinfunction "1_1") (pintype "passive"))
    )
    (net (code "207") (name "TF9") (class "Default")
      (node (ref "J2") (pin "9") (pinfunction "9_9") (pintype "bidirectional"))
      (node (ref "R143") (pin "2") (pinfunction "2_2") (pintype "passive"))
      (node (ref "R144") (pin "1") (pinfunction "1_1") (pintype "passive"))
      (node (ref "TO_FPGA_16") (pin "1") (pinfunction "1_1") (pintype "passive"))
    )
    (net (code "208") (name "TF10") (class "Default")
      (node (ref "J2") (pin "10") (pinfunction "10_10") (pintype "bidirectional"))
      (node (ref "R170") (pin "2") (pinfunction "2_2") (pintype "passive"))
      (node (ref "R171") (pin "1") (pinfunction "1_1") (pintype "passive"))
      (node (ref "TO_FPGA_18") (pin "1") (pinfunction "1_1") (pintype "passive"))
    )
    (net (code "209") (name "TF11") (class "Default")
      (node (ref "J2") (pin "11") (pinfunction "11_11") (pintype "bidirectional"))
      (node (ref "R44") (pin "2") (pinfunction "2_2") (pintype "passive"))
      (node (ref "R45") (pin "1") (pinfunction "1_1") (pintype "passive"))
      (node (ref "TO_FPGA_5") (pin "1") (pinfunction "1_1") (pintype "passive"))
    )
    (net (code "210") (name "TF12") (class "Default")
      (node (ref "J2") (pin "12") (pinfunction "12_12") (pintype "bidirectional"))
      (node (ref "R80") (pin "2") (pinfunction "2_2") (pintype "passive"))
      (node (ref "R81") (pin "1") (pinfunction "1_1") (pintype "passive"))
      (node (ref "TO_FPGA_9") (pin "1") (pinfunction "1_1") (pintype "passive"))
    )
    (net (code "211") (name "TF13") (class "Default")
      (node (ref "J2") (pin "13") (pinfunction "13_13") (pintype "bidirectional"))
      (node (ref "R62") (pin "2") (pinfunction "2_2") (pintype "passive"))
      (node (ref "R63") (pin "1") (pinfunction "1_1") (pintype "passive"))
      (node (ref "TO_FPGA_7") (pin "1") (pinfunction "1_1") (pintype "passive"))
    )
    (net (code "212") (name "TF14") (class "Default")
      (node (ref "J2") (pin "14") (pinfunction "14_14") (pintype "bidirectional"))
      (node (ref "R116") (pin "2") (pinfunction "2_2") (pintype "passive"))
      (node (ref "R117") (pin "1") (pinfunction "1_1") (pintype "passive"))
      (node (ref "TO_FPGA_13") (pin "1") (pinfunction "1_1") (pintype "passive"))
    )
    (net (code "213") (name "TF15") (class "Default")
      (node (ref "J2") (pin "15") (pinfunction "15_15") (pintype "bidirectional"))
      (node (ref "R153") (pin "2") (pinfunction "2_2") (pintype "passive"))
      (node (ref "R154") (pin "1") (pinfunction "1_1") (pintype "passive"))
      (node (ref "TO_FPGA_17") (pin "1") (pinfunction "1_1") (pintype "passive"))
    )
    (net (code "214") (name "TF16") (class "Default")
      (node (ref "J2") (pin "16") (pinfunction "16_16") (pintype "bidirectional"))
      (node (ref "R188") (pin "2") (pinfunction "2_2") (pintype "passive"))
      (node (ref "R189") (pin "1") (pinfunction "1_1") (pintype "passive"))
      (node (ref "TO_FPGA_20") (pin "1") (pinfunction "1_1") (pintype "passive"))
    )
    (net (code "215") (name "TF17") (class "Default")
      (node (ref "J2") (pin "17") (pinfunction "17_17") (pintype "bidirectional"))
      (node (ref "R161") (pin "2") (pinfunction "2_2") (pintype "passive"))
      (node (ref "R166") (pin "2") (pinfunction "2_2") (pintype "passive"))
      (node (ref "TF17_TP1") (pin "1") (pinfunction "1_1") (pintype "passive"))
    )
    (net (code "216") (name "unconnected-(J1-Pad18)") (class "Default")
      (node (ref "J1") (pin "18") (pinfunction "18_18") (pintype "bidirectional"))
    )
    (net (code "217") (name "unconnected-(J1-Pad19)") (class "Default")
      (node (ref "J1") (pin "19") (pinfunction "19_19") (pintype "bidirectional"))
    )
    (net (code "218") (name "unconnected-(J1-Pad20)") (class "Default")
      (node (ref "J1") (pin "20") (pinfunction "20_20") (pintype "bidirectional"))
    )
    (net (code "219") (name "unconnected-(J1-Pad21)") (class "Default")
      (node (ref "J1") (pin "21") (pinfunction "21_21") (pintype "bidirectional"))
    )
    (net (code "220") (name "unconnected-(J1-Pad22)") (class "Default")
      (node (ref "J1") (pin "22") (pinfunction "22_22") (pintype "bidirectional"))
    )
    (net (code "221") (name "unconnected-(J1-Pad23)") (class "Default")
      (node (ref "J1") (pin "23") (pinfunction "23_23") (pintype "bidirectional"))
    )
    (net (code "222") (name "unconnected-(J1-Pad24)") (class "Default")
      (node (ref "J1") (pin "24") (pinfunction "24_24") (pintype "bidirectional"))
    )
    (net (code "223") (name "unconnected-(J2-Pad18)") (class "Default")
      (node (ref "J2") (pin "18") (pinfunction "18_18") (pintype "bidirectional"))
    )
    (net (code "224") (name "unconnected-(J2-Pad19)") (class "Default")
      (node (ref "J2") (pin "19") (pinfunction "19_19") (pintype "bidirectional"))
    )
    (net (code "225") (name "unconnected-(J2-Pad20)") (class "Default")
      (node (ref "J2") (pin "20") (pinfunction "20_20") (pintype "bidirectional"))
    )
    (net (code "226") (name "unconnected-(J2-Pad21)") (class "Default")
      (node (ref "J2") (pin "21") (pinfunction "21_21") (pintype "bidirectional"))
    )
    (net (code "227") (name "unconnected-(J2-Pad22)") (class "Default")
      (node (ref "J2") (pin "22") (pinfunction "22_22") (pintype "bidirectional"))
    )
    (net (code "228") (name "unconnected-(J2-Pad23)") (class "Default")
      (node (ref "J2") (pin "23") (pinfunction "23_23") (pintype "bidirectional"))
    )
    (net (code "229") (name "unconnected-(J2-Pad24)") (class "Default")
      (node (ref "J2") (pin "24") (pinfunction "24_24") (pintype "bidirectional"))
    )
    (net (code "230") (name "unconnected-(J3-Pad17)") (class "Default")
      (node (ref "J3") (pin "17") (pinfunction "17_17") (pintype "bidirectional"))
    )
    (net (code "231") (name "unconnected-(J3-Pad18)") (class "Default")
      (node (ref "J3") (pin "18") (pinfunction "18_18") (pintype "bidirectional"))
    )
    (net (code "232") (name "unconnected-(J3-Pad19)") (class "Default")
      (node (ref "J3") (pin "19") (pinfunction "19_19") (pintype "bidirectional"))
    )
    (net (code "233") (name "unconnected-(J3-Pad20)") (class "Default")
      (node (ref "J3") (pin "20") (pinfunction "20_20") (pintype "bidirectional"))
    )
    (net (code "234") (name "unconnected-(J3-Pad21)") (class "Default")
      (node (ref "J3") (pin "21") (pinfunction "21_21") (pintype "bidirectional"))
    )
    (net (code "235") (name "unconnected-(J3-Pad22)") (class "Default")
      (node (ref "J3") (pin "22") (pinfunction "22_22") (pintype "bidirectional"))
    )
    (net (code "236") (name "unconnected-(J3-Pad23)") (class "Default")
      (node (ref "J3") (pin "23") (pinfunction "23_23") (pintype "bidirectional"))
    )
    (net (code "237") (name "unconnected-(J3-Pad24)") (class "Default")
      (node (ref "J3") (pin "24") (pinfunction "24_24") (pintype "bidirectional"))
    )
    (net (code "238") (name "unconnected-(U5-NC-Pad5)") (class "Default")
      (node (ref "U5") (pin "5") (pinfunction "NC_5") (pintype "passive"))
    )
    (net (code "239") (name "unconnected-(U5-NC_2-Pad1)") (class "Default")
      (node (ref "U5") (pin "1") (pinfunction "NC_2_1") (pintype "passive"))
    )
    (net (code "240") (name "unconnected-(U6-NC-Pad5)") (class "Default")
      (node (ref "U6") (pin "5") (pinfunction "NC_5") (pintype "passive"))
    )
    (net (code "241") (name "unconnected-(U6-NC_2-Pad1)") (class "Default")
      (node (ref "U6") (pin "1") (pinfunction "NC_2_1") (pintype "passive"))
    )
    (net (code "242") (name "unconnected-(U7-NC-Pad5)") (class "Default")
      (node (ref "U7") (pin "5") (pinfunction "NC_5") (pintype "passive"))
    )
    (net (code "243") (name "unconnected-(U7-NC_2-Pad1)") (class "Default")
      (node (ref "U7") (pin "1") (pinfunction "NC_2_1") (pintype "passive"))
    )
    (net (code "244") (name "unconnected-(U8-NC-Pad5)") (class "Default")
      (node (ref "U8") (pin "5") (pinfunction "NC_5") (pintype "passive"))
    )
    (net (code "245") (name "unconnected-(U8-NC_2-Pad1)") (class "Default")
      (node (ref "U8") (pin "1") (pinfunction "NC_2_1") (pintype "passive"))
    )
    (net (code "246") (name "unconnected-(U9-NC-Pad5)") (class "Default")
      (node (ref "U9") (pin "5") (pinfunction "NC_5") (pintype "passive"))
    )
    (net (code "247") (name "unconnected-(U9-NC_2-Pad1)") (class "Default")
      (node (ref "U9") (pin "1") (pinfunction "NC_2_1") (pintype "passive"))
    )
    (net (code "248") (name "unconnected-(U10-NC-Pad5)") (class "Default")
      (node (ref "U10") (pin "5") (pinfunction "NC_5") (pintype "passive"))
    )
    (net (code "249") (name "unconnected-(U10-NC_2-Pad1)") (class "Default")
      (node (ref "U10") (pin "1") (pinfunction "NC_2_1") (pintype "passive"))
    )
    (net (code "250") (name "unconnected-(U11-NC-Pad5)") (class "Default")
      (node (ref "U11") (pin "5") (pinfunction "NC_5") (pintype "passive"))
    )
    (net (code "251") (name "unconnected-(U11-NC_2-Pad1)") (class "Default")
      (node (ref "U11") (pin "1") (pinfunction "NC_2_1") (pintype "passive"))
    )
    (net (code "252") (name "unconnected-(U12-NC-Pad5)") (class "Default")
      (node (ref "U12") (pin "5") (pinfunction "NC_5") (pintype "passive"))
    )
    (net (code "253") (name "unconnected-(U12-NC_2-Pad1)") (class "Default")
      (node (ref "U12") (pin "1") (pinfunction "NC_2_1") (pintype "passive"))
    )
    (net (code "254") (name "unconnected-(U13-NC-Pad5)") (class "Default")
      (node (ref "U13") (pin "5") (pinfunction "NC_5") (pintype "passive"))
    )
    (net (code "255") (name "unconnected-(U13-NC_2-Pad1)") (class "Default")
      (node (ref "U13") (pin "1") (pinfunction "NC_2_1") (pintype "passive"))
    )
    (net (code "256") (name "unconnected-(U14-NC-Pad5)") (class "Default")
      (node (ref "U14") (pin "5") (pinfunction "NC_5") (pintype "passive"))
    )
    (net (code "257") (name "unconnected-(U14-NC_2-Pad1)") (class "Default")
      (node (ref "U14") (pin "1") (pinfunction "NC_2_1") (pintype "passive"))
    )
    (net (code "258") (name "unconnected-(U15-NC-Pad5)") (class "Default")
      (node (ref "U15") (pin "5") (pinfunction "NC_5") (pintype "passive"))
    )
    (net (code "259") (name "unconnected-(U15-NC_2-Pad1)") (class "Default")
      (node (ref "U15") (pin "1") (pinfunction "NC_2_1") (pintype "passive"))
    )
    (net (code "260") (name "unconnected-(U16-NC-Pad5)") (class "Default")
      (node (ref "U16") (pin "5") (pinfunction "NC_5") (pintype "passive"))
    )
    (net (code "261") (name "unconnected-(U16-NC_2-Pad1)") (class "Default")
      (node (ref "U16") (pin "1") (pinfunction "NC_2_1") (pintype "passive"))
    )
    (net (code "262") (name "unconnected-(U17-NC-Pad5)") (class "Default")
      (node (ref "U17") (pin "5") (pinfunction "NC_5") (pintype "passive"))
    )
    (net (code "263") (name "unconnected-(U17-NC_2-Pad1)") (class "Default")
      (node (ref "U17") (pin "1") (pinfunction "NC_2_1") (pintype "passive"))
    )
    (net (code "264") (name "unconnected-(U18-NC-Pad5)") (class "Default")
      (node (ref "U18") (pin "5") (pinfunction "NC_5") (pintype "passive"))
    )
    (net (code "265") (name "unconnected-(U18-NC_2-Pad1)") (class "Default")
      (node (ref "U18") (pin "1") (pinfunction "NC_2_1") (pintype "passive"))
    )
    (net (code "266") (name "unconnected-(U19-NC-Pad5)") (class "Default")
      (node (ref "U19") (pin "5") (pinfunction "NC_5") (pintype "passive"))
    )
    (net (code "267") (name "unconnected-(U19-NC_2-Pad1)") (class "Default")
      (node (ref "U19") (pin "1") (pinfunction "NC_2_1") (pintype "passive"))
    )
    (net (code "268") (name "unconnected-(U20-NC-Pad5)") (class "Default")
      (node (ref "U20") (pin "5") (pinfunction "NC_5") (pintype "passive"))
    )
    (net (code "269") (name "unconnected-(U20-NC_2-Pad1)") (class "Default")
      (node (ref "U20") (pin "1") (pinfunction "NC_2_1") (pintype "passive"))
    )
    (net (code "270") (name "unconnected-(U21-NC-Pad5)") (class "Default")
      (node (ref "U21") (pin "5") (pinfunction "NC_5") (pintype "passive"))
    )
    (net (code "271") (name "unconnected-(U21-NC_2-Pad1)") (class "Default")
      (node (ref "U21") (pin "1") (pinfunction "NC_2_1") (pintype "passive"))
    )
    (net (code "272") (name "unconnected-(U22-NC-Pad5)") (class "Default")
      (node (ref "U22") (pin "5") (pinfunction "NC_5") (pintype "passive"))
    )
    (net (code "273") (name "unconnected-(U22-NC_2-Pad1)") (class "Default")
      (node (ref "U22") (pin "1") (pinfunction "NC_2_1") (pintype "passive"))
    )
    (net (code "274") (name "unconnected-(U25-NC-Pad5)") (class "Default")
      (node (ref "U25") (pin "5") (pinfunction "NC_5") (pintype "passive"))
    )
    (net (code "275") (name "unconnected-(U25-NC_2-Pad1)") (class "Default")
      (node (ref "U25") (pin "1") (pinfunction "NC_2_1") (pintype "passive"))
    )
    (net (code "276") (name "unconnected-(U26-NC-Pad5)") (class "Default")
      (node (ref "U26") (pin "5") (pinfunction "NC_5") (pintype "passive"))
    )
    (net (code "277") (name "unconnected-(U26-NC_2-Pad1)") (class "Default")
      (node (ref "U26") (pin "1") (pinfunction "NC_2_1") (pintype "passive"))
    )
    (net (code "278") (name "unconnected-(U27-NC-Pad5)") (class "Default")
      (node (ref "U27") (pin "5") (pinfunction "NC_5") (pintype "passive"))
    )
    (net (code "279") (name "unconnected-(U27-NC_2-Pad1)") (class "Default")
      (node (ref "U27") (pin "1") (pinfunction "NC_2_1") (pintype "passive"))
    )
    (net (code "280") (name "unconnected-(U28-NC-Pad5)") (class "Default")
      (node (ref "U28") (pin "5") (pinfunction "NC_5") (pintype "passive"))
    )
    (net (code "281") (name "unconnected-(U28-NC_2-Pad1)") (class "Default")
      (node (ref "U28") (pin "1") (pinfunction "NC_2_1") (pintype "passive"))
    )
    (net (code "282") (name "unconnected-(U29-NC-Pad5)") (class "Default")
      (node (ref "U29") (pin "5") (pinfunction "NC_5") (pintype "passive"))
    )
    (net (code "283") (name "unconnected-(U29-NC_2-Pad1)") (class "Default")
      (node (ref "U29") (pin "1") (pinfunction "NC_2_1") (pintype "passive"))
    )
    (net (code "284") (name "unconnected-(U30-NC-Pad5)") (class "Default")
      (node (ref "U30") (pin "5") (pinfunction "NC_5") (pintype "passive"))
    )
    (net (code "285") (name "unconnected-(U30-NC_2-Pad1)") (class "Default")
      (node (ref "U30") (pin "1") (pinfunction "NC_2_1") (pintype "passive"))
    )
    (net (code "286") (name "unconnected-(U33-NC-Pad5)") (class "Default")
      (node (ref "U33") (pin "5") (pinfunction "NC_5") (pintype "passive"))
    )
    (net (code "287") (name "unconnected-(U33-NC_2-Pad1)") (class "Default")
      (node (ref "U33") (pin "1") (pinfunction "NC_2_1") (pintype "passive"))
    )
    (net (code "288") (name "unconnected-(U34-NC-Pad5)") (class "Default")
      (node (ref "U34") (pin "5") (pinfunction "NC_5") (pintype "passive"))
    )
    (net (code "289") (name "unconnected-(U34-NC_2-Pad1)") (class "Default")
      (node (ref "U34") (pin "1") (pinfunction "NC_2_1") (pintype "passive"))
    )
    (net (code "290") (name "unconnected-(U35-NC-Pad5)") (class "Default")
      (node (ref "U35") (pin "5") (pinfunction "NC_5") (pintype "passive"))
    )
    (net (code "291") (name "unconnected-(U35-NC_2-Pad1)") (class "Default")
      (node (ref "U35") (pin "1") (pinfunction "NC_2_1") (pintype "passive"))
    )
    (net (code "292") (name "unconnected-(U36-NC-Pad5)") (class "Default")
      (node (ref "U36") (pin "5") (pinfunction "NC_5") (pintype "passive"))
    )
    (net (code "293") (name "unconnected-(U36-NC_2-Pad1)") (class "Default")
      (node (ref "U36") (pin "1") (pinfunction "NC_2_1") (pintype "passive"))
    )
    (net (code "294") (name "unconnected-(U37-NC-Pad5)") (class "Default")
      (node (ref "U37") (pin "5") (pinfunction "NC_5") (pintype "passive"))
    )
    (net (code "295") (name "unconnected-(U37-NC_2-Pad1)") (class "Default")
      (node (ref "U37") (pin "1") (pinfunction "NC_2_1") (pintype "passive"))
    )
    (net (code "296") (name "unconnected-(U39-NC-Pad5)") (class "Default")
      (node (ref "U39") (pin "5") (pinfunction "NC_5") (pintype "passive"))
    )
    (net (code "297") (name "unconnected-(U39-NC_2-Pad1)") (class "Default")
      (node (ref "U39") (pin "1") (pinfunction "NC_2_1") (pintype "passive"))
    )
    (net (code "298") (name "unconnected-(U40-NC-Pad5)") (class "Default")
      (node (ref "U40") (pin "5") (pinfunction "NC_5") (pintype "passive"))
    )
    (net (code "299") (name "unconnected-(U40-NC_2-Pad1)") (class "Default")
      (node (ref "U40") (pin "1") (pinfunction "NC_2_1") (pintype "passive"))
    )
    (net (code "300") (name "unconnected-(U41-NC-Pad5)") (class "Default")
      (node (ref "U41") (pin "5") (pinfunction "NC_5") (pintype "passive"))
    )
    (net (code "301") (name "unconnected-(U41-NC_2-Pad1)") (class "Default")
      (node (ref "U41") (pin "1") (pinfunction "NC_2_1") (pintype "passive"))
    )
    (net (code "302") (name "unconnected-(U44-NC-Pad5)") (class "Default")
      (node (ref "U44") (pin "5") (pinfunction "NC_5") (pintype "passive"))
    )
    (net (code "303") (name "unconnected-(U44-NC_2-Pad1)") (class "Default")
      (node (ref "U44") (pin "1") (pinfunction "NC_2_1") (pintype "passive"))
    )
    (net (code "304") (name "unconnected-(U45-NC-Pad5)") (class "Default")
      (node (ref "U45") (pin "5") (pinfunction "NC_5") (pintype "passive"))
    )
    (net (code "305") (name "unconnected-(U45-NC_2-Pad1)") (class "Default")
      (node (ref "U45") (pin "1") (pinfunction "NC_2_1") (pintype "passive"))
    )
  )
)
